# FPGA1.net
KiCad netlist of a schematic drawn in Altium Designer
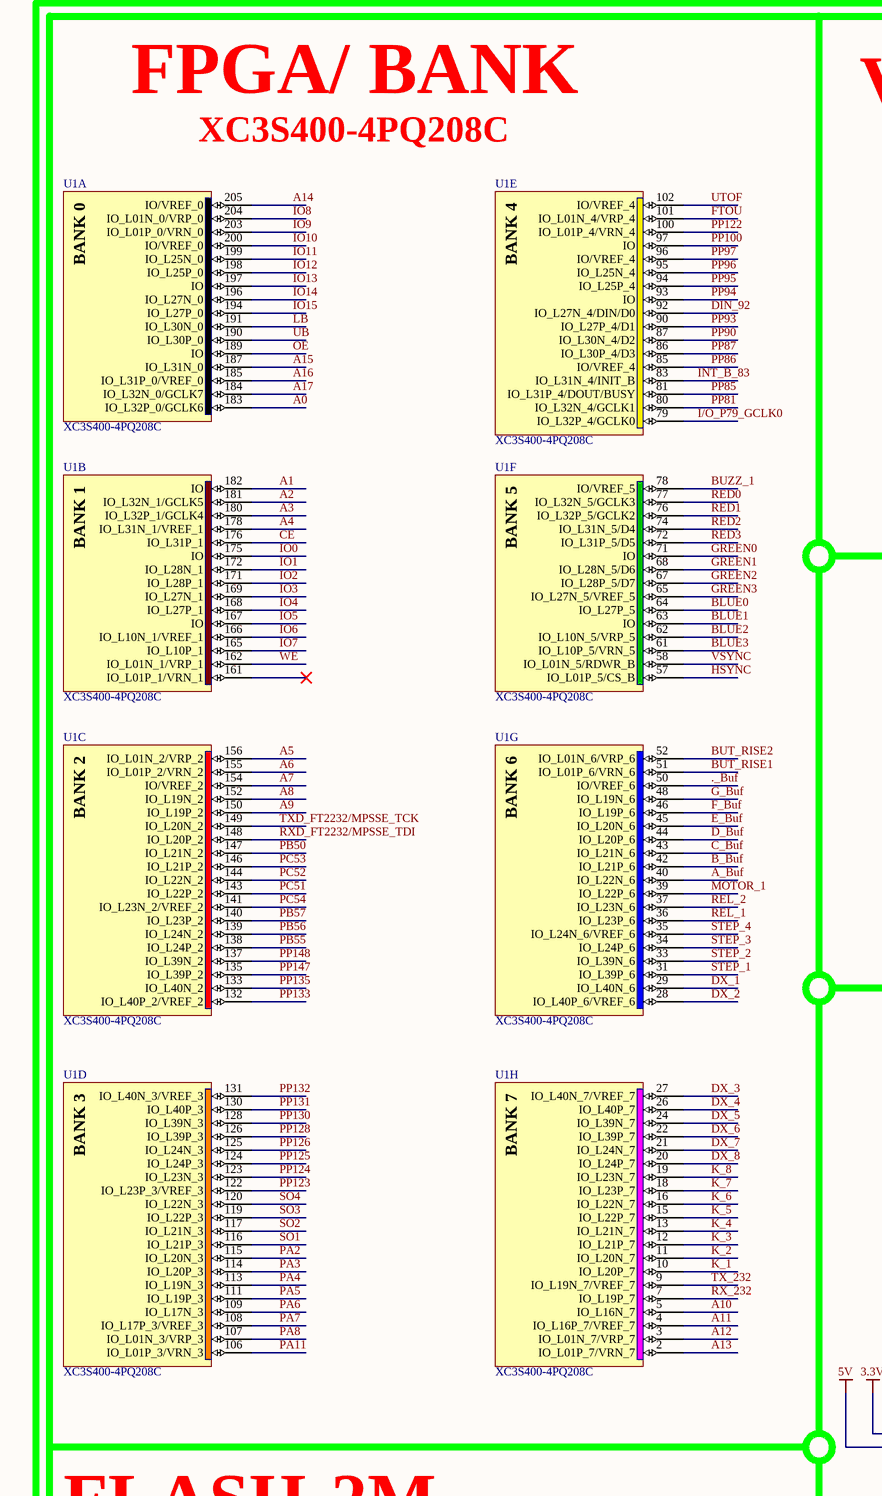
[diagram p0: FPGA1.SchDoc, top left]
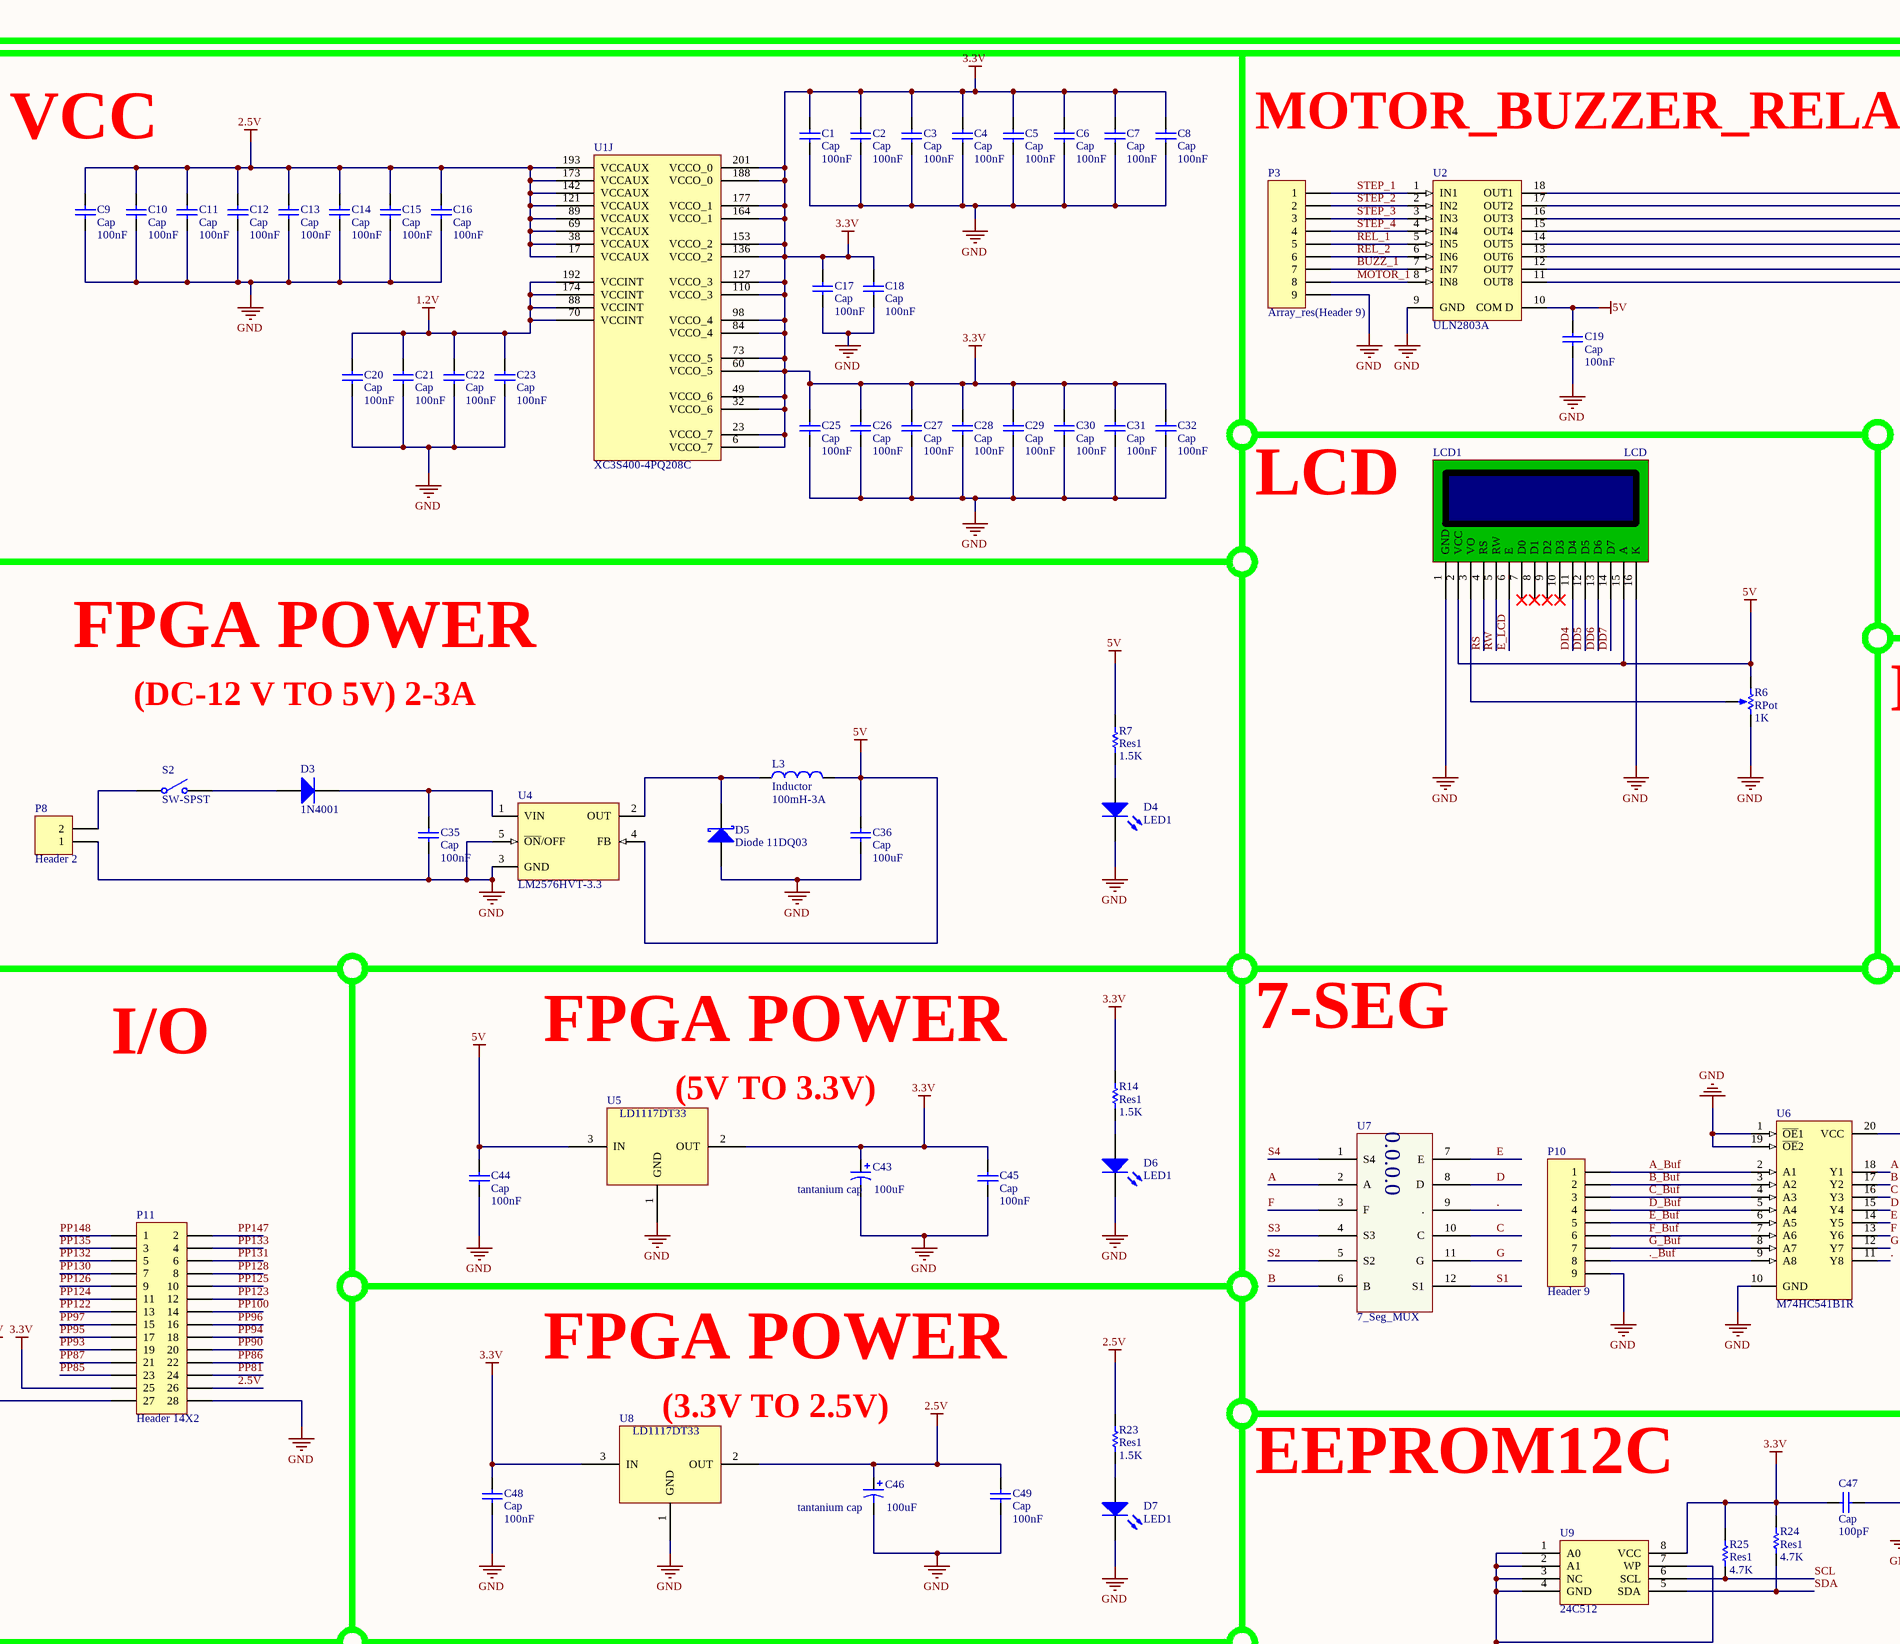
[diagram p1: FPGA1.SchDoc, top middle]
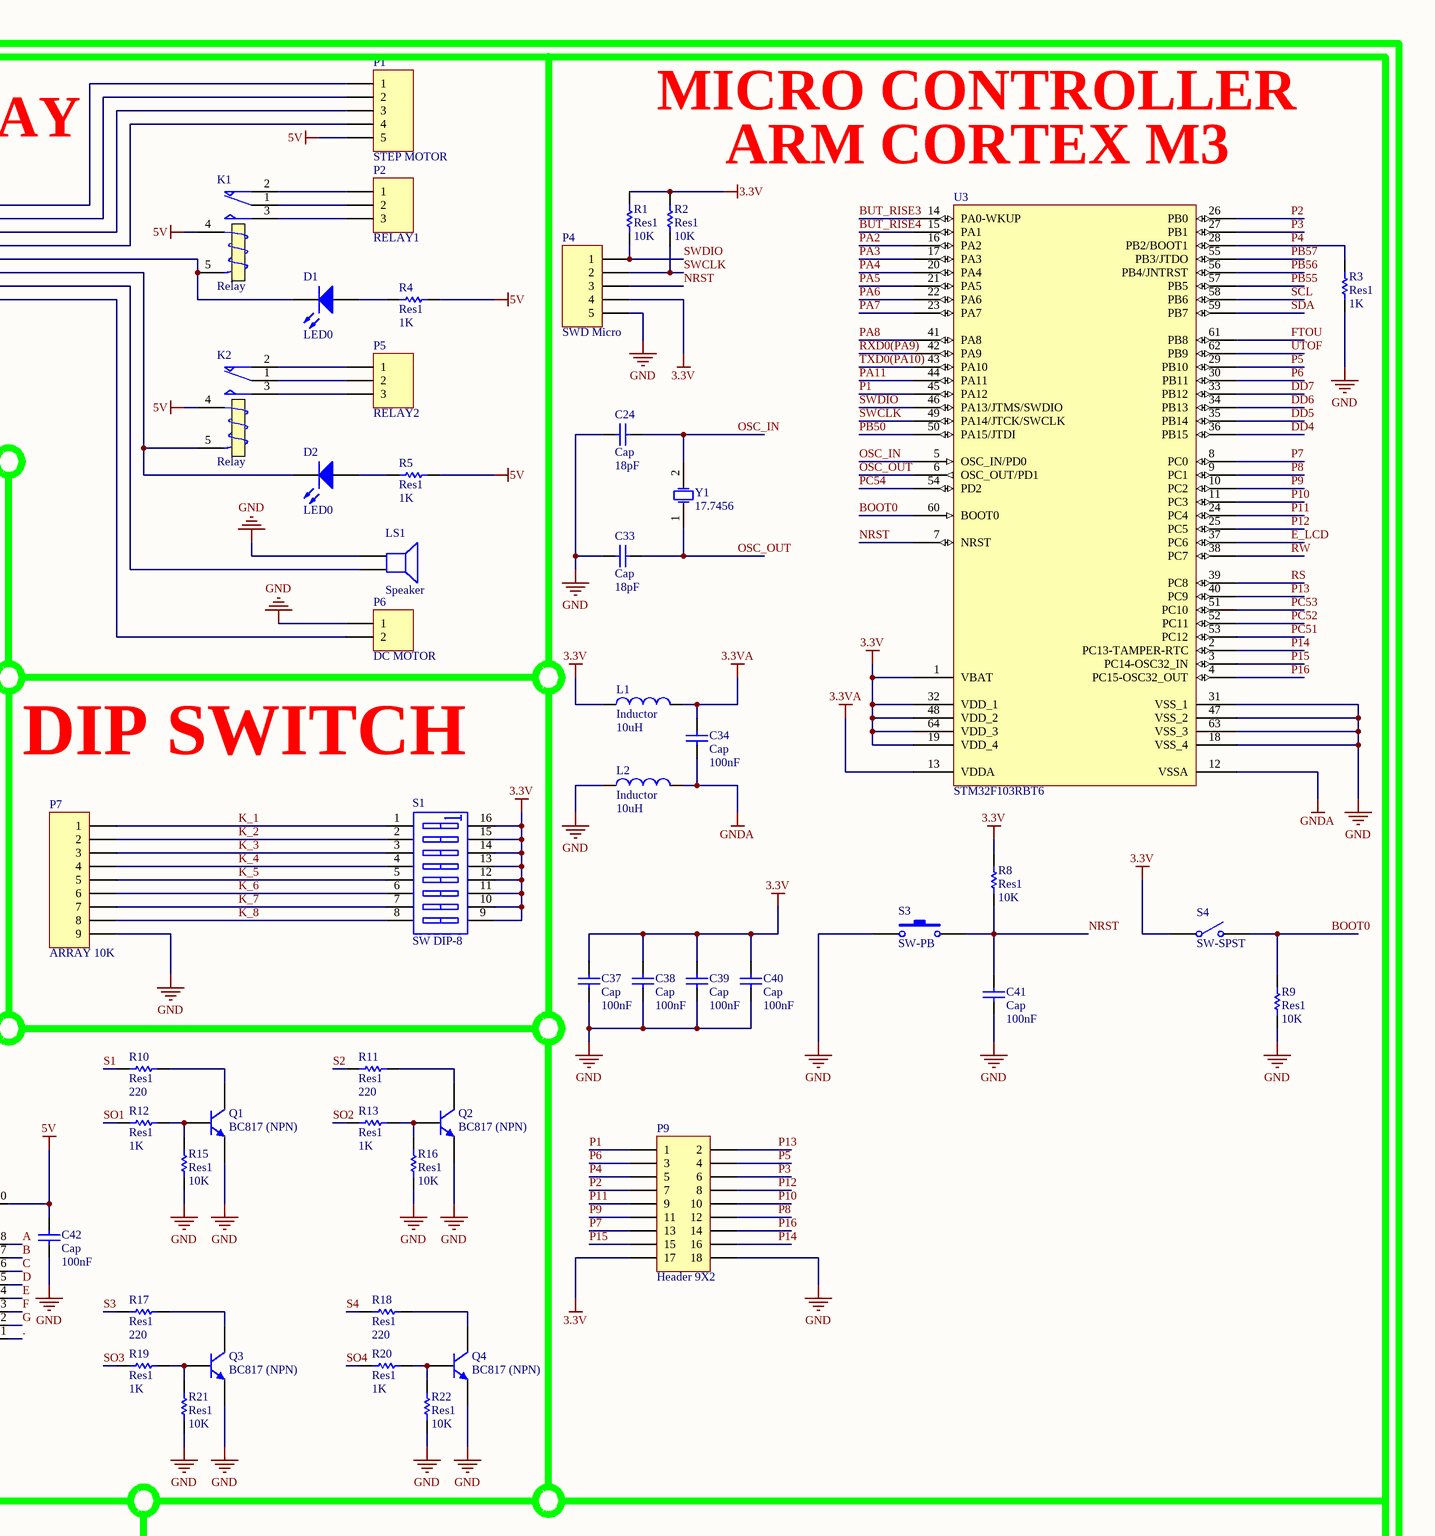
[diagram p2: FPGA1.SchDoc, top right]
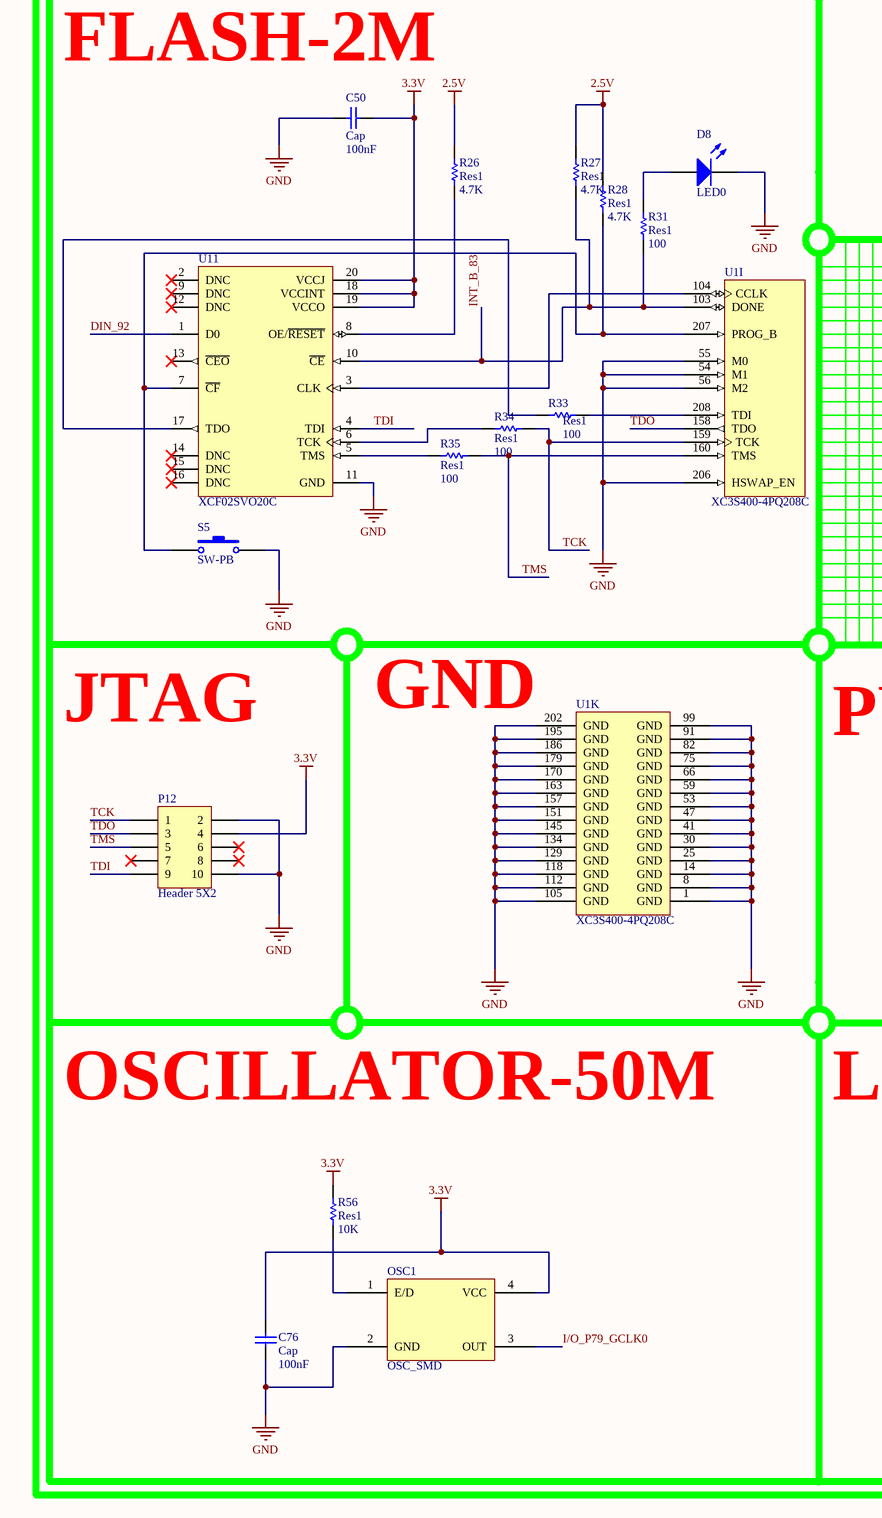
[diagram p3: FPGA1.SchDoc, bottom left]
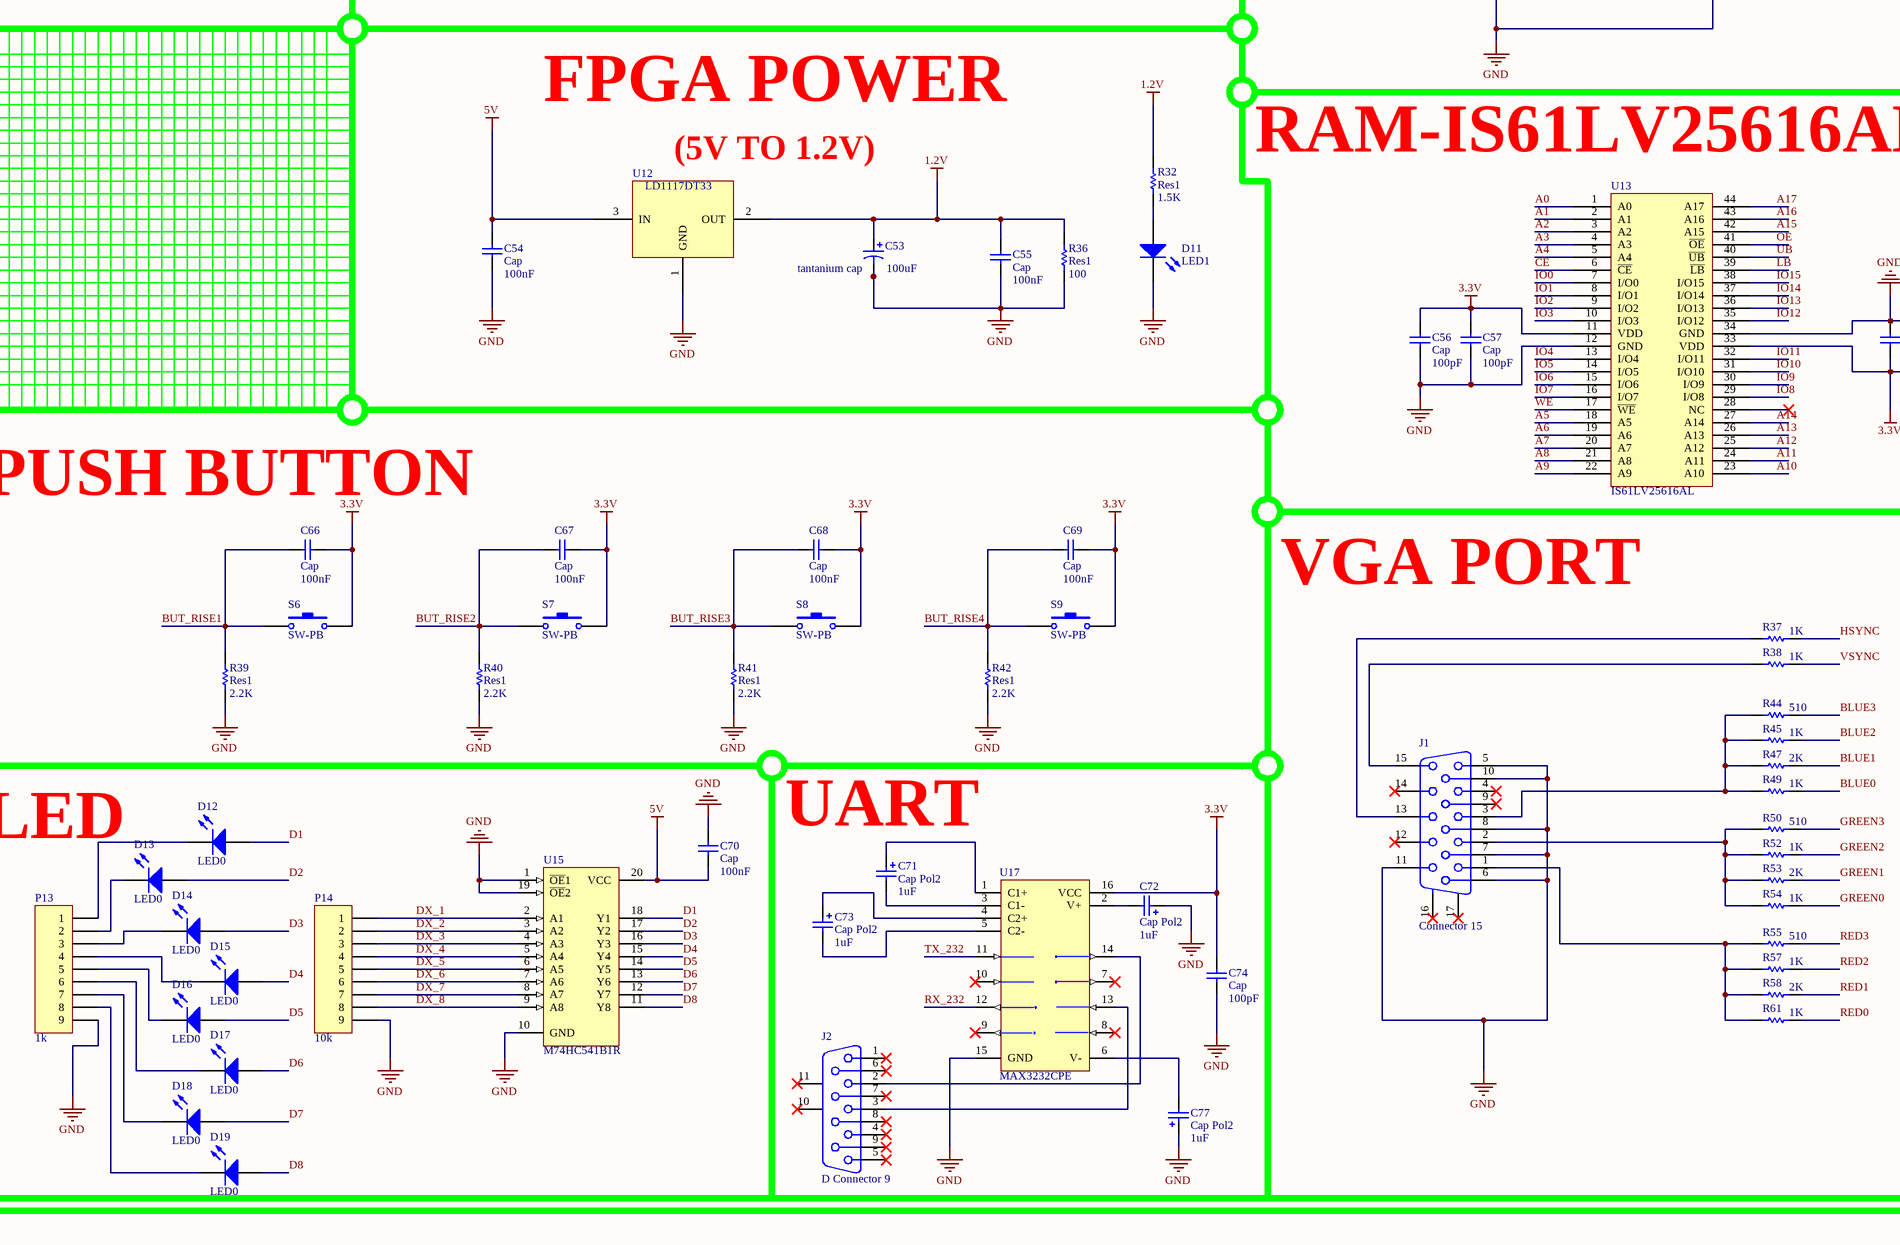
[diagram p4: FPGA1.SchDoc, bottom middle]
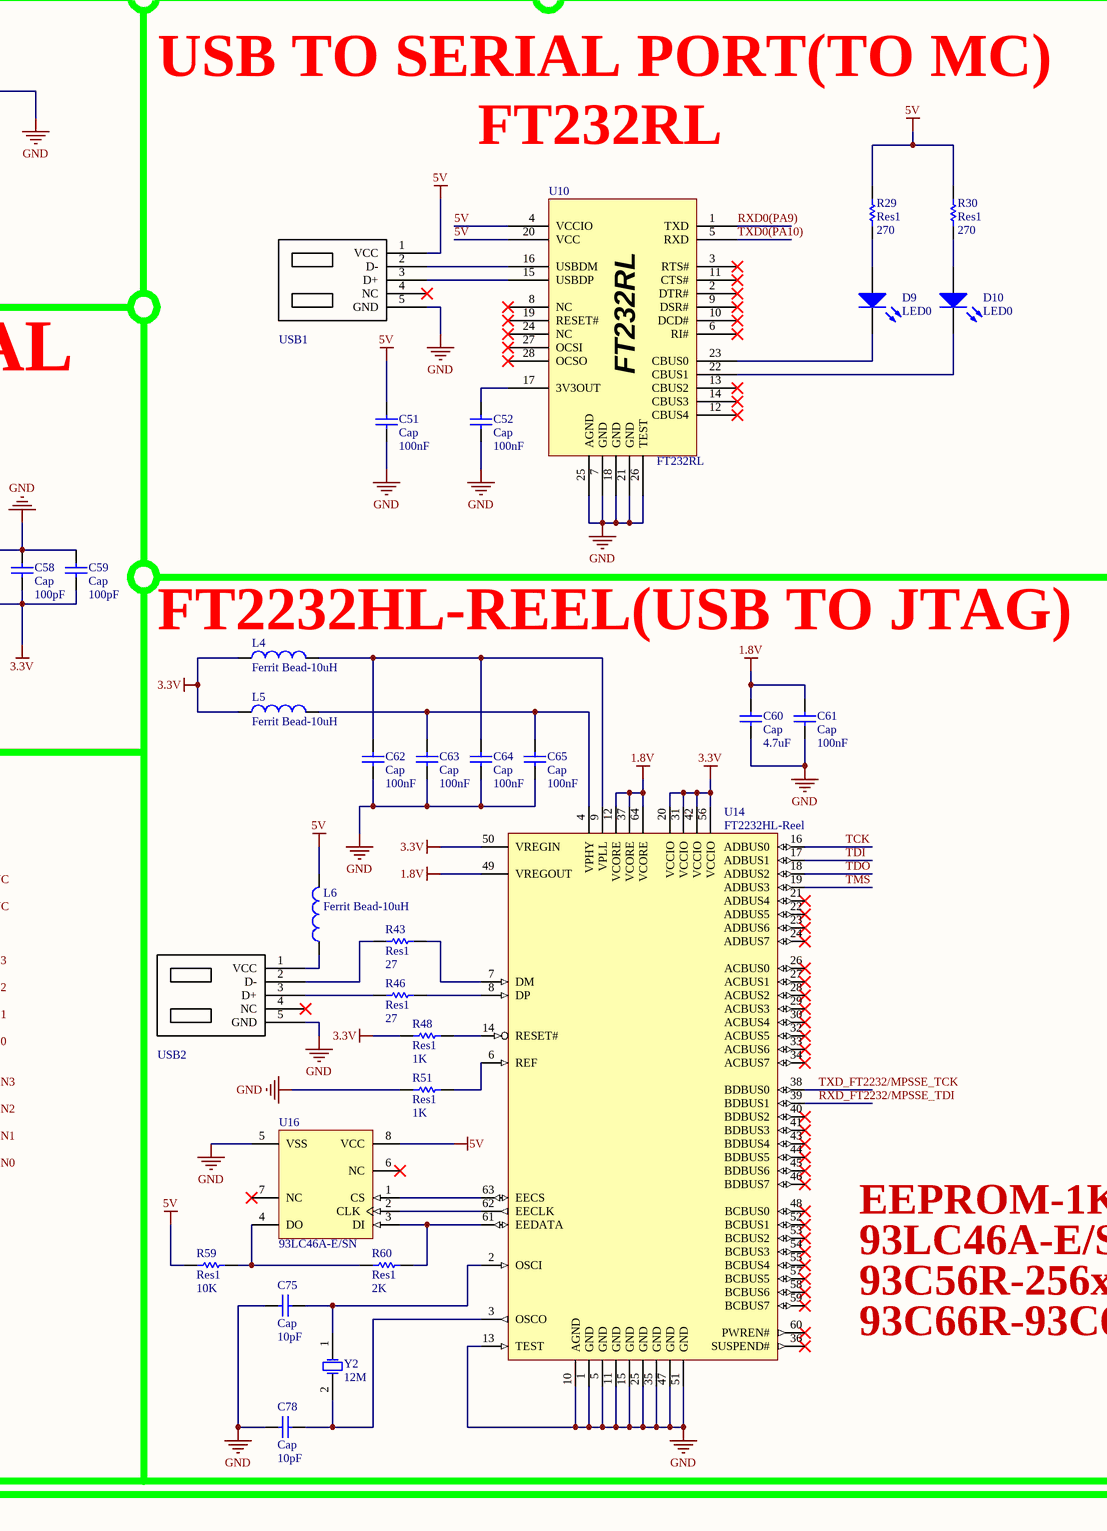
[diagram p5: FPGA1.SchDoc, bottom right]

(export (version "E")
  (design (tool "Eeschema 10.0.6"))
  (components
    (comp (ref "C1")
      (value "Cap")
      (footprint "SMD_805")
      (description "Capacitor")
      (fields (field (name "ALTIUM_VALUE") "100nF") (field (name "PUBLISHER") "Altium Limited"))
      (libsource (lib "Miscellaneous Devices") (part "Cap"))
    )
    (comp (ref "C2")
      (value "Cap")
      (footprint "SMD_805")
      (description "Capacitor")
      (fields (field (name "ALTIUM_VALUE") "100nF") (field (name "PUBLISHER") "Altium Limited"))
      (libsource (lib "Miscellaneous Devices") (part "Cap"))
    )
    (comp (ref "C3")
      (value "Cap")
      (footprint "SMD_805")
      (description "Capacitor")
      (fields (field (name "ALTIUM_VALUE") "100nF") (field (name "PUBLISHER") "Altium Limited"))
      (libsource (lib "Miscellaneous Devices") (part "Cap"))
    )
    (comp (ref "C4")
      (value "Cap")
      (footprint "SMD_805")
      (description "Capacitor")
      (fields (field (name "ALTIUM_VALUE") "100nF") (field (name "PUBLISHER") "Altium Limited"))
      (libsource (lib "Miscellaneous Devices") (part "Cap"))
    )
    (comp (ref "C5")
      (value "Cap")
      (footprint "SMD_805")
      (description "Capacitor")
      (fields (field (name "ALTIUM_VALUE") "100nF") (field (name "PUBLISHER") "Altium Limited"))
      (libsource (lib "Miscellaneous Devices") (part "Cap"))
    )
    (comp (ref "C6")
      (value "Cap")
      (footprint "SMD_805")
      (description "Capacitor")
      (fields (field (name "ALTIUM_VALUE") "100nF") (field (name "PUBLISHER") "Altium Limited"))
      (libsource (lib "Miscellaneous Devices") (part "Cap"))
    )
    (comp (ref "C7")
      (value "Cap")
      (footprint "SMD_805")
      (description "Capacitor")
      (fields (field (name "ALTIUM_VALUE") "100nF") (field (name "PUBLISHER") "Altium Limited"))
      (libsource (lib "Miscellaneous Devices") (part "Cap"))
    )
    (comp (ref "C8")
      (value "Cap")
      (footprint "SMD_805")
      (description "Capacitor")
      (fields (field (name "ALTIUM_VALUE") "100nF") (field (name "PUBLISHER") "Altium Limited"))
      (libsource (lib "Miscellaneous Devices") (part "Cap"))
    )
    (comp (ref "C9")
      (value "Cap")
      (footprint "SMD_805")
      (description "Capacitor")
      (fields (field (name "ALTIUM_VALUE") "100nF") (field (name "PUBLISHER") "Altium Limited"))
      (libsource (lib "Miscellaneous Devices") (part "Cap"))
    )
    (comp (ref "C10")
      (value "Cap")
      (footprint "SMD_805")
      (description "Capacitor")
      (fields (field (name "ALTIUM_VALUE") "100nF") (field (name "PUBLISHER") "Altium Limited"))
      (libsource (lib "Miscellaneous Devices") (part "Cap"))
    )
    (comp (ref "C11")
      (value "Cap")
      (footprint "SMD_805")
      (description "Capacitor")
      (fields (field (name "ALTIUM_VALUE") "100nF") (field (name "PUBLISHER") "Altium Limited"))
      (libsource (lib "Miscellaneous Devices") (part "Cap"))
    )
    (comp (ref "C12")
      (value "Cap")
      (footprint "SMD_805")
      (description "Capacitor")
      (fields (field (name "ALTIUM_VALUE") "100nF") (field (name "PUBLISHER") "Altium Limited"))
      (libsource (lib "Miscellaneous Devices") (part "Cap"))
    )
    (comp (ref "C13")
      (value "Cap")
      (footprint "SMD_805")
      (description "Capacitor")
      (fields (field (name "ALTIUM_VALUE") "100nF") (field (name "PUBLISHER") "Altium Limited"))
      (libsource (lib "Miscellaneous Devices") (part "Cap"))
    )
    (comp (ref "C14")
      (value "Cap")
      (footprint "SMD_805")
      (description "Capacitor")
      (fields (field (name "ALTIUM_VALUE") "100nF") (field (name "PUBLISHER") "Altium Limited"))
      (libsource (lib "Miscellaneous Devices") (part "Cap"))
    )
    (comp (ref "C15")
      (value "Cap")
      (footprint "SMD_805")
      (description "Capacitor")
      (fields (field (name "ALTIUM_VALUE") "100nF") (field (name "PUBLISHER") "Altium Limited"))
      (libsource (lib "Miscellaneous Devices") (part "Cap"))
    )
    (comp (ref "C16")
      (value "Cap")
      (footprint "SMD_805")
      (description "Capacitor")
      (fields (field (name "ALTIUM_VALUE") "100nF") (field (name "PUBLISHER") "Altium Limited"))
      (libsource (lib "Miscellaneous Devices") (part "Cap"))
    )
    (comp (ref "C17")
      (value "Cap")
      (footprint "SMD_805")
      (description "Capacitor")
      (fields (field (name "ALTIUM_VALUE") "100nF") (field (name "PUBLISHER") "Altium Limited"))
      (libsource (lib "Miscellaneous Devices") (part "Cap"))
    )
    (comp (ref "C18")
      (value "Cap")
      (footprint "SMD_805")
      (description "Capacitor")
      (fields (field (name "ALTIUM_VALUE") "100nF") (field (name "PUBLISHER") "Altium Limited"))
      (libsource (lib "Miscellaneous Devices") (part "Cap"))
    )
    (comp (ref "C19")
      (value "Cap")
      (footprint "SMD_805")
      (description "Capacitor")
      (fields (field (name "ALTIUM_VALUE") "100nF") (field (name "PUBLISHER") "Altium Limited"))
      (libsource (lib "Miscellaneous Devices") (part "Cap"))
    )
    (comp (ref "C20")
      (value "Cap")
      (footprint "SMD_805")
      (description "Capacitor")
      (fields (field (name "ALTIUM_VALUE") "100nF") (field (name "PUBLISHER") "Altium Limited"))
      (libsource (lib "Miscellaneous Devices") (part "Cap"))
    )
    (comp (ref "C21")
      (value "Cap")
      (footprint "SMD_805")
      (description "Capacitor")
      (fields (field (name "ALTIUM_VALUE") "100nF") (field (name "PUBLISHER") "Altium Limited"))
      (libsource (lib "Miscellaneous Devices") (part "Cap"))
    )
    (comp (ref "C22")
      (value "Cap")
      (footprint "SMD_805")
      (description "Capacitor")
      (fields (field (name "ALTIUM_VALUE") "100nF") (field (name "PUBLISHER") "Altium Limited"))
      (libsource (lib "Miscellaneous Devices") (part "Cap"))
    )
    (comp (ref "C23")
      (value "Cap")
      (footprint "SMD_805")
      (description "Capacitor")
      (fields (field (name "ALTIUM_VALUE") "100nF") (field (name "PUBLISHER") "Altium Limited"))
      (libsource (lib "Miscellaneous Devices") (part "Cap"))
    )
    (comp (ref "C24")
      (value "Cap")
      (footprint "SMD_805")
      (description "Capacitor")
      (fields (field (name "ALTIUM_VALUE") "18pF") (field (name "PUBLISHER") "Altium Limited"))
      (libsource (lib "Miscellaneous Devices") (part "Cap"))
    )
    (comp (ref "C25")
      (value "Cap")
      (footprint "SMD_805")
      (description "Capacitor")
      (fields (field (name "ALTIUM_VALUE") "100nF") (field (name "PUBLISHER") "Altium Limited"))
      (libsource (lib "Miscellaneous Devices") (part "Cap"))
    )
    (comp (ref "C26")
      (value "Cap")
      (footprint "SMD_805")
      (description "Capacitor")
      (fields (field (name "ALTIUM_VALUE") "100nF") (field (name "PUBLISHER") "Altium Limited"))
      (libsource (lib "Miscellaneous Devices") (part "Cap"))
    )
    (comp (ref "C27")
      (value "Cap")
      (footprint "SMD_805")
      (description "Capacitor")
      (fields (field (name "ALTIUM_VALUE") "100nF") (field (name "PUBLISHER") "Altium Limited"))
      (libsource (lib "Miscellaneous Devices") (part "Cap"))
    )
    (comp (ref "C28")
      (value "Cap")
      (footprint "SMD_805")
      (description "Capacitor")
      (fields (field (name "ALTIUM_VALUE") "100nF") (field (name "PUBLISHER") "Altium Limited"))
      (libsource (lib "Miscellaneous Devices") (part "Cap"))
    )
    (comp (ref "C29")
      (value "Cap")
      (footprint "SMD_805")
      (description "Capacitor")
      (fields (field (name "ALTIUM_VALUE") "100nF") (field (name "PUBLISHER") "Altium Limited"))
      (libsource (lib "Miscellaneous Devices") (part "Cap"))
    )
    (comp (ref "C30")
      (value "Cap")
      (footprint "SMD_805")
      (description "Capacitor")
      (fields (field (name "ALTIUM_VALUE") "100nF") (field (name "PUBLISHER") "Altium Limited"))
      (libsource (lib "Miscellaneous Devices") (part "Cap"))
    )
    (comp (ref "C31")
      (value "Cap")
      (footprint "SMD_805")
      (description "Capacitor")
      (fields (field (name "ALTIUM_VALUE") "100nF") (field (name "PUBLISHER") "Altium Limited"))
      (libsource (lib "Miscellaneous Devices") (part "Cap"))
    )
    (comp (ref "C32")
      (value "Cap")
      (footprint "SMD_805")
      (description "Capacitor")
      (fields (field (name "ALTIUM_VALUE") "100nF") (field (name "PUBLISHER") "Altium Limited"))
      (libsource (lib "Miscellaneous Devices") (part "Cap"))
    )
    (comp (ref "C33")
      (value "Cap")
      (footprint "SMD_805")
      (description "Capacitor")
      (fields (field (name "ALTIUM_VALUE") "18pF") (field (name "PUBLISHER") "Altium Limited"))
      (libsource (lib "Miscellaneous Devices") (part "Cap"))
    )
    (comp (ref "C34")
      (value "Cap")
      (footprint "SMD_805")
      (description "Capacitor")
      (fields (field (name "ALTIUM_VALUE") "100nF") (field (name "PUBLISHER") "Altium Limited"))
      (libsource (lib "Miscellaneous Devices") (part "Cap"))
    )
    (comp (ref "C35")
      (value "Cap")
      (footprint "C_CYL_SMD2")
      (description "Capacitor")
      (fields (field (name "ALTIUM_VALUE") "100nF") (field (name "PUBLISHER") "Altium Limited"))
      (libsource (lib "Miscellaneous Devices") (part "Cap"))
    )
    (comp (ref "C36")
      (value "Cap")
      (footprint "C_CYL_SMD")
      (description "Capacitor")
      (fields (field (name "ALTIUM_VALUE") "100uF") (field (name "PUBLISHER") "Altium Limited"))
      (libsource (lib "Miscellaneous Devices") (part "Cap"))
    )
    (comp (ref "C37")
      (value "Cap")
      (footprint "SMD_805")
      (description "Capacitor")
      (fields (field (name "ALTIUM_VALUE") "100nF") (field (name "PUBLISHER") "Altium Limited"))
      (libsource (lib "Miscellaneous Devices") (part "Cap"))
    )
    (comp (ref "C38")
      (value "Cap")
      (footprint "SMD_805")
      (description "Capacitor")
      (fields (field (name "ALTIUM_VALUE") "100nF") (field (name "PUBLISHER") "Altium Limited"))
      (libsource (lib "Miscellaneous Devices") (part "Cap"))
    )
    (comp (ref "C39")
      (value "Cap")
      (footprint "SMD_805")
      (description "Capacitor")
      (fields (field (name "ALTIUM_VALUE") "100nF") (field (name "PUBLISHER") "Altium Limited"))
      (libsource (lib "Miscellaneous Devices") (part "Cap"))
    )
    (comp (ref "C40")
      (value "Cap")
      (footprint "SMD_805")
      (description "Capacitor")
      (fields (field (name "ALTIUM_VALUE") "100nF") (field (name "PUBLISHER") "Altium Limited"))
      (libsource (lib "Miscellaneous Devices") (part "Cap"))
    )
    (comp (ref "C41")
      (value "Cap")
      (footprint "SMD_805")
      (description "Capacitor")
      (fields (field (name "ALTIUM_VALUE") "100nF") (field (name "PUBLISHER") "Altium Limited"))
      (libsource (lib "Miscellaneous Devices") (part "Cap"))
    )
    (comp (ref "C42")
      (value "Cap")
      (footprint "SMD_805")
      (description "Capacitor")
      (fields (field (name "ALTIUM_VALUE") "100nF") (field (name "PUBLISHER") "Altium Limited"))
      (libsource (lib "Miscellaneous Devices") (part "Cap"))
    )
    (comp (ref "C43")
      (value "tantanium cap")
      (footprint "C_B")
      (description "Polarized Capacitor (Surface Mount)")
      (fields (field (name "ALTIUM_VALUE") "100uF") (field (name "PUBLISHER") "Altium Limited"))
      (libsource (lib "Miscellaneous Devices") (part "Cap Pol3"))
    )
    (comp (ref "C44")
      (value "Cap")
      (footprint "SMD_805")
      (description "Capacitor")
      (fields (field (name "ALTIUM_VALUE") "100nF") (field (name "PUBLISHER") "Altium Limited"))
      (libsource (lib "Miscellaneous Devices") (part "Cap"))
    )
    (comp (ref "C45")
      (value "Cap")
      (footprint "SMD_805")
      (description "Capacitor")
      (fields (field (name "ALTIUM_VALUE") "100nF") (field (name "PUBLISHER") "Altium Limited"))
      (libsource (lib "Miscellaneous Devices") (part "Cap"))
    )
    (comp (ref "C46")
      (value "tantanium cap")
      (footprint "C_B")
      (description "Polarized Capacitor (Surface Mount)")
      (fields (field (name "ALTIUM_VALUE") "100uF") (field (name "PUBLISHER") "Altium Limited"))
      (libsource (lib "Miscellaneous Devices") (part "Cap Pol3"))
    )
    (comp (ref "C47")
      (value "Cap")
      (footprint "SMD_805")
      (description "Capacitor")
      (fields (field (name "ALTIUM_VALUE") "100pF") (field (name "PUBLISHER") "Altium Limited"))
      (libsource (lib "Miscellaneous Devices") (part "Cap"))
    )
    (comp (ref "C48")
      (value "Cap")
      (footprint "SMD_805")
      (description "Capacitor")
      (fields (field (name "ALTIUM_VALUE") "100nF") (field (name "PUBLISHER") "Altium Limited"))
      (libsource (lib "Miscellaneous Devices") (part "Cap"))
    )
    (comp (ref "C49")
      (value "Cap")
      (footprint "SMD_805")
      (description "Capacitor")
      (fields (field (name "ALTIUM_VALUE") "100nF") (field (name "PUBLISHER") "Altium Limited"))
      (libsource (lib "Miscellaneous Devices") (part "Cap"))
    )
    (comp (ref "C50")
      (value "Cap")
      (footprint "SMD_805")
      (description "Capacitor")
      (fields (field (name "ALTIUM_VALUE") "100nF") (field (name "PUBLISHER") "Altium Limited"))
      (libsource (lib "Miscellaneous Devices") (part "Cap"))
    )
    (comp (ref "C51")
      (value "Cap")
      (footprint "SMD_805")
      (description "Capacitor")
      (fields (field (name "ALTIUM_VALUE") "100nF") (field (name "PUBLISHER") "Altium Limited"))
      (libsource (lib "Miscellaneous Devices") (part "Cap"))
    )
    (comp (ref "C52")
      (value "Cap")
      (footprint "SMD_805")
      (description "Capacitor")
      (fields (field (name "ALTIUM_VALUE") "100nF") (field (name "PUBLISHER") "Altium Limited"))
      (libsource (lib "Miscellaneous Devices") (part "Cap"))
    )
    (comp (ref "C53")
      (value "tantanium cap")
      (footprint "C_B")
      (description "Polarized Capacitor (Surface Mount)")
      (fields (field (name "ALTIUM_VALUE") "100uF") (field (name "PUBLISHER") "Altium Limited"))
      (libsource (lib "Miscellaneous Devices") (part "Cap Pol3"))
    )
    (comp (ref "C54")
      (value "Cap")
      (footprint "SMD_805")
      (description "Capacitor")
      (fields (field (name "ALTIUM_VALUE") "100nF") (field (name "PUBLISHER") "Altium Limited"))
      (libsource (lib "Miscellaneous Devices") (part "Cap"))
    )
    (comp (ref "C55")
      (value "Cap")
      (footprint "SMD_805")
      (description "Capacitor")
      (fields (field (name "ALTIUM_VALUE") "100nF") (field (name "PUBLISHER") "Altium Limited"))
      (libsource (lib "Miscellaneous Devices") (part "Cap"))
    )
    (comp (ref "C56")
      (value "Cap")
      (footprint "SMD_805")
      (description "Capacitor")
      (fields (field (name "ALTIUM_VALUE") "100pF") (field (name "PUBLISHER") "Altium Limited"))
      (libsource (lib "Miscellaneous Devices") (part "Cap"))
    )
    (comp (ref "C57")
      (value "Cap")
      (footprint "SMD_805")
      (description "Capacitor")
      (fields (field (name "ALTIUM_VALUE") "100pF") (field (name "PUBLISHER") "Altium Limited"))
      (libsource (lib "Miscellaneous Devices") (part "Cap"))
    )
    (comp (ref "C58")
      (value "Cap")
      (footprint "SMD_805")
      (description "Capacitor")
      (fields (field (name "ALTIUM_VALUE") "100pF") (field (name "PUBLISHER") "Altium Limited"))
      (libsource (lib "Miscellaneous Devices") (part "Cap"))
    )
    (comp (ref "C59")
      (value "Cap")
      (footprint "SMD_805")
      (description "Capacitor")
      (fields (field (name "ALTIUM_VALUE") "100pF") (field (name "PUBLISHER") "Altium Limited"))
      (libsource (lib "Miscellaneous Devices") (part "Cap"))
    )
    (comp (ref "C60")
      (value "Cap")
      (footprint "SMD_805")
      (description "Capacitor")
      (fields (field (name "ALTIUM_VALUE") "4.7uF") (field (name "PUBLISHER") "Altium Limited"))
      (libsource (lib "Miscellaneous Devices") (part "Cap"))
    )
    (comp (ref "C61")
      (value "Cap")
      (footprint "SMD_805")
      (description "Capacitor")
      (fields (field (name "ALTIUM_VALUE") "100nF") (field (name "PUBLISHER") "Altium Limited"))
      (libsource (lib "Miscellaneous Devices") (part "Cap"))
    )
    (comp (ref "C62")
      (value "Cap")
      (footprint "SMD_805")
      (description "Capacitor")
      (fields (field (name "ALTIUM_VALUE") "100nF") (field (name "PUBLISHER") "Altium Limited"))
      (libsource (lib "Miscellaneous Devices") (part "Cap"))
    )
    (comp (ref "C63")
      (value "Cap")
      (footprint "SMD_805")
      (description "Capacitor")
      (fields (field (name "ALTIUM_VALUE") "100nF") (field (name "PUBLISHER") "Altium Limited"))
      (libsource (lib "Miscellaneous Devices") (part "Cap"))
    )
    (comp (ref "C64")
      (value "Cap")
      (footprint "SMD_805")
      (description "Capacitor")
      (fields (field (name "ALTIUM_VALUE") "100nF") (field (name "PUBLISHER") "Altium Limited"))
      (libsource (lib "Miscellaneous Devices") (part "Cap"))
    )
    (comp (ref "C65")
      (value "Cap")
      (footprint "SMD_805")
      (description "Capacitor")
      (fields (field (name "ALTIUM_VALUE") "100nF") (field (name "PUBLISHER") "Altium Limited"))
      (libsource (lib "Miscellaneous Devices") (part "Cap"))
    )
    (comp (ref "C66")
      (value "Cap")
      (footprint "SMD_805")
      (description "Capacitor")
      (fields (field (name "ALTIUM_VALUE") "100nF") (field (name "PUBLISHER") "Altium Limited"))
      (libsource (lib "Miscellaneous Devices") (part "Cap"))
    )
    (comp (ref "C67")
      (value "Cap")
      (footprint "SMD_805")
      (description "Capacitor")
      (fields (field (name "ALTIUM_VALUE") "100nF") (field (name "PUBLISHER") "Altium Limited"))
      (libsource (lib "Miscellaneous Devices") (part "Cap"))
    )
    (comp (ref "C68")
      (value "Cap")
      (footprint "SMD_805")
      (description "Capacitor")
      (fields (field (name "ALTIUM_VALUE") "100nF") (field (name "PUBLISHER") "Altium Limited"))
      (libsource (lib "Miscellaneous Devices") (part "Cap"))
    )
    (comp (ref "C69")
      (value "Cap")
      (footprint "SMD_805")
      (description "Capacitor")
      (fields (field (name "ALTIUM_VALUE") "100nF") (field (name "PUBLISHER") "Altium Limited"))
      (libsource (lib "Miscellaneous Devices") (part "Cap"))
    )
    (comp (ref "C70")
      (value "Cap")
      (footprint "SMD_805")
      (description "Capacitor")
      (fields (field (name "ALTIUM_VALUE") "100nF") (field (name "PUBLISHER") "Altium Limited"))
      (libsource (lib "Miscellaneous Devices") (part "Cap"))
    )
    (comp (ref "C71")
      (value "Cap Pol2")
      (footprint "C_B")
      (description "Polarized Capacitor (Axial)")
      (fields (field (name "ALTIUM_VALUE") "1uF") (field (name "PUBLISHER") "Altium Limited"))
      (libsource (lib "Miscellaneous Devices") (part "Cap Pol2"))
    )
    (comp (ref "C72")
      (value "Cap Pol2")
      (footprint "C_B")
      (description "Polarized Capacitor (Axial)")
      (fields (field (name "ALTIUM_VALUE") "1uF") (field (name "PUBLISHER") "Altium Limited"))
      (libsource (lib "Miscellaneous Devices") (part "Cap Pol2"))
    )
    (comp (ref "C73")
      (value "Cap Pol2")
      (footprint "C_B")
      (description "Polarized Capacitor (Axial)")
      (fields (field (name "ALTIUM_VALUE") "1uF") (field (name "PUBLISHER") "Altium Limited"))
      (libsource (lib "Miscellaneous Devices") (part "Cap Pol2"))
    )
    (comp (ref "C74")
      (value "Cap")
      (footprint "SMD_805")
      (description "Capacitor")
      (fields (field (name "ALTIUM_VALUE") "100pF") (field (name "PUBLISHER") "Altium Limited"))
      (libsource (lib "Miscellaneous Devices") (part "Cap"))
    )
    (comp (ref "C75")
      (value "Cap")
      (footprint "SMD_805")
      (description "Capacitor")
      (fields (field (name "ALTIUM_VALUE") "10pF") (field (name "PUBLISHER") "Altium Limited"))
      (libsource (lib "Miscellaneous Devices") (part "Cap"))
    )
    (comp (ref "C76")
      (value "Cap")
      (footprint "SMD_805")
      (description "Capacitor")
      (fields (field (name "ALTIUM_VALUE") "100nF") (field (name "PUBLISHER") "Altium Limited"))
      (libsource (lib "Miscellaneous Devices") (part "Cap"))
    )
    (comp (ref "C77")
      (value "Cap Pol2")
      (footprint "C_B")
      (description "Polarized Capacitor (Axial)")
      (fields (field (name "ALTIUM_VALUE") "1uF") (field (name "PUBLISHER") "Altium Limited"))
      (libsource (lib "Miscellaneous Devices") (part "Cap Pol2"))
    )
    (comp (ref "C78")
      (value "Cap")
      (footprint "SMD_805")
      (description "Capacitor")
      (fields (field (name "ALTIUM_VALUE") "10pF") (field (name "PUBLISHER") "Altium Limited"))
      (libsource (lib "Miscellaneous Devices") (part "Cap"))
    )
    (comp (ref "D1")
      (value "LED0")
      (footprint "LED1206GRN")
      (description "Typical INFRARED GaAs LED")
      (fields (field (name "PUBLISHER") "Altium Limited"))
      (libsource (lib "Miscellaneous Devices") (part "LED0"))
    )
    (comp (ref "D2")
      (value "LED0")
      (footprint "LED1206GRN")
      (description "Typical INFRARED GaAs LED")
      (fields (field (name "PUBLISHER") "Altium Limited"))
      (libsource (lib "Miscellaneous Devices") (part "LED0"))
    )
    (comp (ref "D3")
      (value "1N4001")
      (footprint "TVS")
      (description "1 Amp General Purpose Rectifier")
      (fields (field (name "PUBLISHER") "Altium Limited"))
      (libsource (lib "Miscellaneous Devices") (part "Diode 1N4001"))
    )
    (comp (ref "D4")
      (value "LED1")
      (footprint "Led0805")
      (description "Typical INFRARED GaAs LED")
      (fields (field (name "PUBLISHER") "Altium Limited"))
      (libsource (lib "Miscellaneous Devices") (part "LED0"))
    )
    (comp (ref "D5")
      (value "Diode 11DQ03")
      (footprint "1N5822")
      (description "Schottky Rectifier")
      (fields (field (name "PUBLISHER") "Altium Limited"))
      (libsource (lib "Miscellaneous Devices") (part "Diode 11DQ03"))
    )
    (comp (ref "D6")
      (value "LED1")
      (footprint "Led0805")
      (description "Typical INFRARED GaAs LED")
      (fields (field (name "PUBLISHER") "Altium Limited"))
      (libsource (lib "Miscellaneous Devices") (part "LED0"))
    )
    (comp (ref "D7")
      (value "LED1")
      (footprint "Led0805")
      (description "Typical INFRARED GaAs LED")
      (fields (field (name "PUBLISHER") "Altium Limited"))
      (libsource (lib "Miscellaneous Devices") (part "LED0"))
    )
    (comp (ref "D8")
      (value "LED0")
      (footprint "LED0805GRN")
      (description "Typical INFRARED GaAs LED")
      (fields (field (name "PUBLISHER") "Altium Limited"))
      (libsource (lib "Miscellaneous Devices") (part "LED0"))
    )
    (comp (ref "D9")
      (value "LED0")
      (footprint "LED0805GRN")
      (description "Typical INFRARED GaAs LED")
      (fields (field (name "PUBLISHER") "Altium Limited"))
      (libsource (lib "Miscellaneous Devices") (part "LED0"))
    )
    (comp (ref "D10")
      (value "LED0")
      (footprint "LED0805GRN")
      (description "Typical INFRARED GaAs LED")
      (fields (field (name "PUBLISHER") "Altium Limited"))
      (libsource (lib "Miscellaneous Devices") (part "LED0"))
    )
    (comp (ref "D11")
      (value "LED1")
      (footprint "Led0805")
      (description "Typical INFRARED GaAs LED")
      (fields (field (name "PUBLISHER") "Altium Limited"))
      (libsource (lib "Miscellaneous Devices") (part "LED0"))
    )
    (comp (ref "D12")
      (value "LED0")
      (footprint "LED1206RED")
      (description "Typical INFRARED GaAs LED")
      (fields (field (name "PUBLISHER") "Altium Limited"))
      (libsource (lib "Miscellaneous Devices") (part "LED0"))
    )
    (comp (ref "D13")
      (value "LED0")
      (footprint "LED1206RED")
      (description "Typical INFRARED GaAs LED")
      (fields (field (name "PUBLISHER") "Altium Limited"))
      (libsource (lib "Miscellaneous Devices") (part "LED0"))
    )
    (comp (ref "D14")
      (value "LED0")
      (footprint "LED1206RED")
      (description "Typical INFRARED GaAs LED")
      (fields (field (name "PUBLISHER") "Altium Limited"))
      (libsource (lib "Miscellaneous Devices") (part "LED0"))
    )
    (comp (ref "D15")
      (value "LED0")
      (footprint "LED1206RED")
      (description "Typical INFRARED GaAs LED")
      (fields (field (name "PUBLISHER") "Altium Limited"))
      (libsource (lib "Miscellaneous Devices") (part "LED0"))
    )
    (comp (ref "D16")
      (value "LED0")
      (footprint "LED1206RED")
      (description "Typical INFRARED GaAs LED")
      (fields (field (name "PUBLISHER") "Altium Limited"))
      (libsource (lib "Miscellaneous Devices") (part "LED0"))
    )
    (comp (ref "D17")
      (value "LED0")
      (footprint "LED1206RED")
      (description "Typical INFRARED GaAs LED")
      (fields (field (name "PUBLISHER") "Altium Limited"))
      (libsource (lib "Miscellaneous Devices") (part "LED0"))
    )
    (comp (ref "D18")
      (value "LED0")
      (footprint "LED1206RED")
      (description "Typical INFRARED GaAs LED")
      (fields (field (name "PUBLISHER") "Altium Limited"))
      (libsource (lib "Miscellaneous Devices") (part "LED0"))
    )
    (comp (ref "D19")
      (value "LED0")
      (footprint "LED1206RED")
      (description "Typical INFRARED GaAs LED")
      (fields (field (name "PUBLISHER") "Altium Limited"))
      (libsource (lib "Miscellaneous Devices") (part "LED0"))
    )
    (comp (ref "J1")
      (value "Connector 15")
      (footprint "DSUB_15RF")
      (description "Receptacle Assembly, 15-Pin, Sim Line Connector")
      (fields (field (name "PUBLISHER") "Altium Limited"))
      (libsource (lib "Miscellaneous Connectors") (part "Connector 15"))
    )
    (comp (ref "J2")
      (value "D Connector 9")
      (footprint "COM_3d")
      (description "Receptacle Assembly, 9 Position, Right Angle")
      (fields (field (name "PUBLISHER") "Altium Limited"))
      (libsource (lib "Miscellaneous Connectors") (part "D Connector 9"))
    )
    (comp (ref "K1")
      (value "Relay")
      (footprint "REL_SPDT_5_1512")
      (description "SPDT Relay")
      (fields (field (name "PUBLISHER") "Altium Limited"))
      (libsource (lib "Miscellaneous Devices") (part "Relay"))
    )
    (comp (ref "K2")
      (value "Relay")
      (footprint "REL_SPDT_5_1512")
      (description "SPDT Relay")
      (fields (field (name "PUBLISHER") "Altium Limited"))
      (libsource (lib "Miscellaneous Devices") (part "Relay"))
    )
    (comp (ref "L1")
      (value "Inductor")
      (footprint "smd_805")
      (fields (field (name "ALTIUM_VALUE") "10uH") (field (name "PUBLISHER") "Altium Limited"))
      (libsource (lib "Miscellaneous Devices") (part "Inductor"))
    )
    (comp (ref "L2")
      (value "Inductor")
      (footprint "smd_805")
      (fields (field (name "ALTIUM_VALUE") "10uH") (field (name "PUBLISHER") "Altium Limited"))
      (libsource (lib "Miscellaneous Devices") (part "Inductor"))
    )
    (comp (ref "L3")
      (value "Inductor")
      (footprint "INDUC_SMD")
      (fields (field (name "ALTIUM_VALUE") "100mH-3A") (field (name "PUBLISHER") "Altium Limited"))
      (libsource (lib "Miscellaneous Devices") (part "Inductor"))
    )
    (comp (ref "L4")
      (value "Ferrit Bead-10uH")
      (footprint "smd_805")
      (description "Inductor")
      (fields (field (name "PUBLISHER") "Altium Limited"))
      (libsource (lib "Miscellaneous Devices") (part "Inductor"))
    )
    (comp (ref "L5")
      (value "Ferrit Bead-10uH")
      (footprint "smd_805")
      (description "Inductor")
      (fields (field (name "PUBLISHER") "Altium Limited"))
      (libsource (lib "Miscellaneous Devices") (part "Inductor"))
    )
    (comp (ref "L6")
      (value "Ferrit Bead-10uH")
      (footprint "smd_805")
      (description "Inductor")
      (fields (field (name "PUBLISHER") "Altium Limited"))
      (libsource (lib "Miscellaneous Devices") (part "Inductor"))
    )
    (comp (ref "LCD1") (value "LCD") (footprint "LCD2x16_3d") (libsource (lib "LCD") (part "LCD")))
    (comp (ref "LS1")
      (value "Speaker")
      (footprint "BZ_C9")
      (description "Loudspeaker")
      (fields (field (name "PUBLISHER") "Altium Limited"))
      (libsource (lib "Miscellaneous Devices") (part "Speaker"))
    )
    (comp (ref "OSC1")
      (value "OSC_SMD")
      (footprint "OSC_SMD")
      (fields (field (name "DESIGNER:") "Mohammad Ansari"))
      (libsource (lib "OSC_SMD") (part "Component_1"))
    )
    (comp (ref "P1")
      (value "STEP MOTOR")
      (footprint "HDR_M_1X5")
      (description "Header, 5-Pin")
      (fields (field (name "PUBLISHER") "Altium Limited"))
      (libsource (lib "") (part "Header 5_1"))
    )
    (comp (ref "P2")
      (value "RELAY1")
      (footprint "HDR_M_1X3")
      (description "Header, 3-Pin")
      (fields (field (name "PUBLISHER") "Altium Limited"))
      (libsource (lib "Miscellaneous Connectors") (part "Header 3"))
    )
    (comp (ref "P3")
      (value "Array_res(Header 9)")
      (footprint "Aray 9")
      (description "Header, 9-Pin")
      (fields (field (name "PUBLISHER") "Altium Limited"))
      (libsource (lib "Miscellaneous Connectors") (part "Header 9"))
    )
    (comp (ref "P4")
      (value "SWD Micro")
      (footprint "HDR_M_1X5")
      (description "Header, 5-Pin")
      (fields (field (name "PUBLISHER") "Altium Limited"))
      (libsource (lib "Miscellaneous Connectors") (part "Header 5"))
    )
    (comp (ref "P5")
      (value "RELAY2")
      (footprint "HDR_M_1X3")
      (description "Header, 3-Pin")
      (fields (field (name "PUBLISHER") "Altium Limited"))
      (libsource (lib "Miscellaneous Connectors") (part "Header 3"))
    )
    (comp (ref "P6")
      (value "DC MOTOR")
      (footprint "HDR_F_1X2")
      (description "Header, 2-Pin")
      (fields (field (name "PUBLISHER") "Altium Limited"))
      (libsource (lib "Miscellaneous Connectors") (part "Header 2"))
    )
    (comp (ref "P7")
      (value "ARRAY 10K")
      (footprint "Aray 9")
      (description "Header, 9-Pin")
      (fields (field (name "PUBLISHER") "Altium Limited"))
      (libsource (lib "Miscellaneous Connectors") (part "Header 9"))
    )
    (comp (ref "P8")
      (value "Header 2")
      (footprint "ADAP_JACK")
      (description "Header, 2-Pin")
      (fields (field (name "PUBLISHER") "Altium Limited"))
      (libsource (lib "") (part "Header 2_1"))
    )
    (comp (ref "P9")
      (value "Header 9X2")
      (footprint "HDR_M_2X9")
      (description "Header, 9-Pin, Dual row")
      (fields (field (name "PUBLISHER") "Altium Limited"))
      (libsource (lib "Miscellaneous Connectors") (part "Header 9X2"))
    )
    (comp (ref "P10")
      (value "Header 9")
      (footprint "Aray 9")
      (description "Header, 9-Pin")
      (fields (field (name "PUBLISHER") "Altium Limited"))
      (libsource (lib "Miscellaneous Connectors") (part "Header 9"))
    )
    (comp (ref "P11")
      (value "Header 14X2")
      (footprint "HDR_M_2X14")
      (description "Header, 14-Pin, Dual row")
      (fields (field (name "PUBLISHER") "Altium Limited"))
      (libsource (lib "Miscellaneous Connectors") (part "Header 14X2"))
    )
    (comp (ref "P12")
      (value "Header 5X2")
      (footprint "BOX2x5")
      (description "Header, 5-Pin, Dual row")
      (fields (field (name "PUBLISHER") "Altium Limited"))
      (libsource (lib "Miscellaneous Connectors") (part "Header 5X2"))
    )
    (comp (ref "P13")
      (value "1k")
      (footprint "Aray 9")
      (description "Header, 9-Pin")
      (fields (field (name "PUBLISHER") "Altium Limited"))
      (libsource (lib "Miscellaneous Connectors") (part "Header 9"))
    )
    (comp (ref "P14")
      (value "10k")
      (footprint "Aray 9")
      (description "Header, 9-Pin")
      (fields (field (name "PUBLISHER") "Altium Limited"))
      (libsource (lib "Miscellaneous Connectors") (part "Header 9"))
    )
    (comp (ref "Q1")
      (value "BC817 (NPN)")
      (footprint "SOT-23")
      (description "NPN General Purpose Amplifier")
      (fields (field (name "PUBLISHER") "Altium Limited"))
      (libsource (lib "Miscellaneous Devices") (part "2N3904"))
    )
    (comp (ref "Q2")
      (value "BC817 (NPN)")
      (footprint "SOT-23")
      (description "NPN General Purpose Amplifier")
      (fields (field (name "PUBLISHER") "Altium Limited"))
      (libsource (lib "Miscellaneous Devices") (part "2N3904"))
    )
    (comp (ref "Q3")
      (value "BC817 (NPN)")
      (footprint "SOT-23")
      (description "NPN General Purpose Amplifier")
      (fields (field (name "PUBLISHER") "Altium Limited"))
      (libsource (lib "Miscellaneous Devices") (part "2N3904"))
    )
    (comp (ref "Q4")
      (value "BC817 (NPN)")
      (footprint "SOT-23")
      (description "NPN General Purpose Amplifier")
      (fields (field (name "PUBLISHER") "Altium Limited"))
      (libsource (lib "Miscellaneous Devices") (part "2N3904"))
    )
    (comp (ref "R1")
      (value "Res1")
      (footprint "SMD_805")
      (description "Resistor")
      (fields (field (name "ALTIUM_VALUE") "10K") (field (name "PUBLISHER") "Altium Limited"))
      (libsource (lib "Miscellaneous Devices") (part "Res1"))
    )
    (comp (ref "R2")
      (value "Res1")
      (footprint "SMD_805")
      (description "Resistor")
      (fields (field (name "ALTIUM_VALUE") "10K") (field (name "PUBLISHER") "Altium Limited"))
      (libsource (lib "Miscellaneous Devices") (part "Res1"))
    )
    (comp (ref "R3")
      (value "Res1")
      (footprint "SMD_805")
      (description "Resistor")
      (fields (field (name "ALTIUM_VALUE") "1K") (field (name "PUBLISHER") "Altium Limited"))
      (libsource (lib "Miscellaneous Devices") (part "Res1"))
    )
    (comp (ref "R4")
      (value "Res1")
      (footprint "SMD_805")
      (description "Resistor")
      (fields (field (name "ALTIUM_VALUE") "1K") (field (name "PUBLISHER") "Altium Limited"))
      (libsource (lib "Miscellaneous Devices") (part "Res1"))
    )
    (comp (ref "R5")
      (value "Res1")
      (footprint "SMD_805")
      (description "Resistor")
      (fields (field (name "ALTIUM_VALUE") "1K") (field (name "PUBLISHER") "Altium Limited"))
      (libsource (lib "Miscellaneous Devices") (part "Res1"))
    )
    (comp (ref "R6")
      (value "RPot")
      (footprint "POT_3296Y")
      (description "Potentiometer")
      (fields (field (name "ALTIUM_VALUE") "1K") (field (name "PUBLISHER") "Altium Limited"))
      (libsource (lib "Miscellaneous Devices") (part "RPot"))
    )
    (comp (ref "R7")
      (value "Res1")
      (footprint "SMD_805")
      (description "Resistor")
      (fields (field (name "ALTIUM_VALUE") "1.5K") (field (name "PUBLISHER") "Altium Limited"))
      (libsource (lib "Miscellaneous Devices") (part "Res1"))
    )
    (comp (ref "R8")
      (value "Res1")
      (footprint "SMD_805")
      (description "Resistor")
      (fields (field (name "ALTIUM_VALUE") "10K") (field (name "PUBLISHER") "Altium Limited"))
      (libsource (lib "Miscellaneous Devices") (part "Res1"))
    )
    (comp (ref "R9")
      (value "Res1")
      (footprint "SMD_805")
      (description "Resistor")
      (fields (field (name "ALTIUM_VALUE") "10K") (field (name "PUBLISHER") "Altium Limited"))
      (libsource (lib "Miscellaneous Devices") (part "Res1"))
    )
    (comp (ref "R10")
      (value "Res1")
      (footprint "SMD_805")
      (description "Resistor")
      (fields (field (name "ALTIUM_VALUE") "220") (field (name "PUBLISHER") "Altium Limited"))
      (libsource (lib "Miscellaneous Devices") (part "Res1"))
    )
    (comp (ref "R11")
      (value "Res1")
      (footprint "SMD_805")
      (description "Resistor")
      (fields (field (name "ALTIUM_VALUE") "220") (field (name "PUBLISHER") "Altium Limited"))
      (libsource (lib "Miscellaneous Devices") (part "Res1"))
    )
    (comp (ref "R12")
      (value "Res1")
      (footprint "SMD_805")
      (description "Resistor")
      (fields (field (name "ALTIUM_VALUE") "1K") (field (name "PUBLISHER") "Altium Limited"))
      (libsource (lib "Miscellaneous Devices") (part "Res1"))
    )
    (comp (ref "R13")
      (value "Res1")
      (footprint "SMD_805")
      (description "Resistor")
      (fields (field (name "ALTIUM_VALUE") "1K") (field (name "PUBLISHER") "Altium Limited"))
      (libsource (lib "Miscellaneous Devices") (part "Res1"))
    )
    (comp (ref "R14")
      (value "Res1")
      (footprint "SMD_805")
      (description "Resistor")
      (fields (field (name "ALTIUM_VALUE") "1.5K") (field (name "PUBLISHER") "Altium Limited"))
      (libsource (lib "Miscellaneous Devices") (part "Res1"))
    )
    (comp (ref "R15")
      (value "Res1")
      (footprint "SMD_805")
      (description "Resistor")
      (fields (field (name "ALTIUM_VALUE") "10K") (field (name "PUBLISHER") "Altium Limited"))
      (libsource (lib "Miscellaneous Devices") (part "Res1"))
    )
    (comp (ref "R16")
      (value "Res1")
      (footprint "SMD_805")
      (description "Resistor")
      (fields (field (name "ALTIUM_VALUE") "10K") (field (name "PUBLISHER") "Altium Limited"))
      (libsource (lib "Miscellaneous Devices") (part "Res1"))
    )
    (comp (ref "R17")
      (value "Res1")
      (footprint "SMD_805")
      (description "Resistor")
      (fields (field (name "ALTIUM_VALUE") "220") (field (name "PUBLISHER") "Altium Limited"))
      (libsource (lib "Miscellaneous Devices") (part "Res1"))
    )
    (comp (ref "R18")
      (value "Res1")
      (footprint "SMD_805")
      (description "Resistor")
      (fields (field (name "ALTIUM_VALUE") "220") (field (name "PUBLISHER") "Altium Limited"))
      (libsource (lib "Miscellaneous Devices") (part "Res1"))
    )
    (comp (ref "R19")
      (value "Res1")
      (footprint "SMD_805")
      (description "Resistor")
      (fields (field (name "ALTIUM_VALUE") "1K") (field (name "PUBLISHER") "Altium Limited"))
      (libsource (lib "Miscellaneous Devices") (part "Res1"))
    )
    (comp (ref "R20")
      (value "Res1")
      (footprint "SMD_805")
      (description "Resistor")
      (fields (field (name "ALTIUM_VALUE") "1K") (field (name "PUBLISHER") "Altium Limited"))
      (libsource (lib "Miscellaneous Devices") (part "Res1"))
    )
    (comp (ref "R21")
      (value "Res1")
      (footprint "SMD_805")
      (description "Resistor")
      (fields (field (name "ALTIUM_VALUE") "10K") (field (name "PUBLISHER") "Altium Limited"))
      (libsource (lib "Miscellaneous Devices") (part "Res1"))
    )
    (comp (ref "R22")
      (value "Res1")
      (footprint "SMD_805")
      (description "Resistor")
      (fields (field (name "ALTIUM_VALUE") "10K") (field (name "PUBLISHER") "Altium Limited"))
      (libsource (lib "Miscellaneous Devices") (part "Res1"))
    )
    (comp (ref "R23")
      (value "Res1")
      (footprint "SMD_805")
      (description "Resistor")
      (fields (field (name "ALTIUM_VALUE") "1.5K") (field (name "PUBLISHER") "Altium Limited"))
      (libsource (lib "Miscellaneous Devices") (part "Res1"))
    )
    (comp (ref "R24")
      (value "Res1")
      (footprint "SMD_805")
      (description "Resistor")
      (fields (field (name "ALTIUM_VALUE") "4.7K") (field (name "PUBLISHER") "Altium Limited"))
      (libsource (lib "Miscellaneous Devices") (part "Res1"))
    )
    (comp (ref "R25")
      (value "Res1")
      (footprint "SMD_805")
      (description "Resistor")
      (fields (field (name "ALTIUM_VALUE") "4.7K") (field (name "PUBLISHER") "Altium Limited"))
      (libsource (lib "Miscellaneous Devices") (part "Res1"))
    )
    (comp (ref "R26")
      (value "Res1")
      (footprint "SMD_805")
      (description "Resistor")
      (fields (field (name "ALTIUM_VALUE") "4.7K") (field (name "PUBLISHER") "Altium Limited"))
      (libsource (lib "Miscellaneous Devices") (part "Res1"))
    )
    (comp (ref "R27")
      (value "Res1")
      (footprint "SMD_805")
      (description "Resistor")
      (fields (field (name "ALTIUM_VALUE") "4.7K") (field (name "PUBLISHER") "Altium Limited"))
      (libsource (lib "Miscellaneous Devices") (part "Res1"))
    )
    (comp (ref "R28")
      (value "Res1")
      (footprint "SMD_805")
      (description "Resistor")
      (fields (field (name "ALTIUM_VALUE") "4.7K") (field (name "PUBLISHER") "Altium Limited"))
      (libsource (lib "Miscellaneous Devices") (part "Res1"))
    )
    (comp (ref "R29")
      (value "Res1")
      (footprint "SMD_805")
      (description "Resistor")
      (fields (field (name "ALTIUM_VALUE") "270") (field (name "PUBLISHER") "Altium Limited"))
      (libsource (lib "Miscellaneous Devices") (part "Res1"))
    )
    (comp (ref "R30")
      (value "Res1")
      (footprint "SMD_805")
      (description "Resistor")
      (fields (field (name "ALTIUM_VALUE") "270") (field (name "PUBLISHER") "Altium Limited"))
      (libsource (lib "Miscellaneous Devices") (part "Res1"))
    )
    (comp (ref "R31")
      (value "Res1")
      (footprint "SMD_805")
      (description "Resistor")
      (fields (field (name "ALTIUM_VALUE") "100") (field (name "PUBLISHER") "Altium Limited"))
      (libsource (lib "Miscellaneous Devices") (part "Res1"))
    )
    (comp (ref "R32")
      (value "Res1")
      (footprint "SMD_805")
      (description "Resistor")
      (fields (field (name "ALTIUM_VALUE") "1.5K") (field (name "PUBLISHER") "Altium Limited"))
      (libsource (lib "Miscellaneous Devices") (part "Res1"))
    )
    (comp (ref "R33")
      (value "Res1")
      (footprint "SMD_805")
      (description "Resistor")
      (fields (field (name "ALTIUM_VALUE") "100") (field (name "PUBLISHER") "Altium Limited"))
      (libsource (lib "Miscellaneous Devices") (part "Res1"))
    )
    (comp (ref "R34")
      (value "Res1")
      (footprint "SMD_805")
      (description "Resistor")
      (fields (field (name "ALTIUM_VALUE") "100") (field (name "PUBLISHER") "Altium Limited"))
      (libsource (lib "Miscellaneous Devices") (part "Res1"))
    )
    (comp (ref "R35")
      (value "Res1")
      (footprint "SMD_805")
      (description "Resistor")
      (fields (field (name "ALTIUM_VALUE") "100") (field (name "PUBLISHER") "Altium Limited"))
      (libsource (lib "Miscellaneous Devices") (part "Res1"))
    )
    (comp (ref "R36")
      (value "Res1")
      (footprint "SMD_805")
      (description "Resistor")
      (fields (field (name "ALTIUM_VALUE") "100") (field (name "PUBLISHER") "Altium Limited"))
      (libsource (lib "Miscellaneous Devices") (part "Res1"))
    )
    (comp (ref "R37")
      (value "1K")
      (footprint "SMD_805")
      (description "Resistor")
      (fields (field (name "PUBLISHER") "Altium Limited"))
      (libsource (lib "Miscellaneous Devices") (part "Res1"))
    )
    (comp (ref "R38")
      (value "1K")
      (footprint "SMD_805")
      (description "Resistor")
      (fields (field (name "PUBLISHER") "Altium Limited"))
      (libsource (lib "Miscellaneous Devices") (part "Res1"))
    )
    (comp (ref "R39")
      (value "Res1")
      (footprint "SMD_805")
      (description "Resistor")
      (fields (field (name "ALTIUM_VALUE") "2.2K") (field (name "PUBLISHER") "Altium Limited"))
      (libsource (lib "Miscellaneous Devices") (part "Res1"))
    )
    (comp (ref "R40")
      (value "Res1")
      (footprint "SMD_805")
      (description "Resistor")
      (fields (field (name "ALTIUM_VALUE") "2.2K") (field (name "PUBLISHER") "Altium Limited"))
      (libsource (lib "Miscellaneous Devices") (part "Res1"))
    )
    (comp (ref "R41")
      (value "Res1")
      (footprint "SMD_805")
      (description "Resistor")
      (fields (field (name "ALTIUM_VALUE") "2.2K") (field (name "PUBLISHER") "Altium Limited"))
      (libsource (lib "Miscellaneous Devices") (part "Res1"))
    )
    (comp (ref "R42")
      (value "Res1")
      (footprint "SMD_805")
      (description "Resistor")
      (fields (field (name "ALTIUM_VALUE") "2.2K") (field (name "PUBLISHER") "Altium Limited"))
      (libsource (lib "Miscellaneous Devices") (part "Res1"))
    )
    (comp (ref "R43")
      (value "Res1")
      (footprint "SMD_805")
      (description "Resistor")
      (fields (field (name "ALTIUM_VALUE") "27") (field (name "PUBLISHER") "Altium Limited"))
      (libsource (lib "Miscellaneous Devices") (part "Res1"))
    )
    (comp (ref "R44")
      (value "510")
      (footprint "SMD_805")
      (description "Resistor")
      (fields (field (name "PUBLISHER") "Altium Limited"))
      (libsource (lib "Miscellaneous Devices") (part "Res1"))
    )
    (comp (ref "R45")
      (value "1K")
      (footprint "SMD_805")
      (description "Resistor")
      (fields (field (name "PUBLISHER") "Altium Limited"))
      (libsource (lib "Miscellaneous Devices") (part "Res1"))
    )
    (comp (ref "R46")
      (value "Res1")
      (footprint "SMD_805")
      (description "Resistor")
      (fields (field (name "ALTIUM_VALUE") "27") (field (name "PUBLISHER") "Altium Limited"))
      (libsource (lib "Miscellaneous Devices") (part "Res1"))
    )
    (comp (ref "R47")
      (value "2K")
      (footprint "SMD_805")
      (description "Resistor")
      (fields (field (name "PUBLISHER") "Altium Limited"))
      (libsource (lib "Miscellaneous Devices") (part "Res1"))
    )
    (comp (ref "R48")
      (value "Res1")
      (footprint "SMD_805")
      (description "Resistor")
      (fields (field (name "ALTIUM_VALUE") "1K") (field (name "PUBLISHER") "Altium Limited"))
      (libsource (lib "Miscellaneous Devices") (part "Res1"))
    )
    (comp (ref "R49")
      (value "1K")
      (footprint "SMD_805")
      (description "Resistor")
      (fields (field (name "PUBLISHER") "Altium Limited"))
      (libsource (lib "Miscellaneous Devices") (part "Res1"))
    )
    (comp (ref "R50")
      (value "510")
      (footprint "SMD_805")
      (description "Resistor")
      (fields (field (name "PUBLISHER") "Altium Limited"))
      (libsource (lib "Miscellaneous Devices") (part "Res1"))
    )
    (comp (ref "R51")
      (value "Res1")
      (footprint "SMD_805")
      (description "Resistor")
      (fields (field (name "ALTIUM_VALUE") "1K") (field (name "PUBLISHER") "Altium Limited"))
      (libsource (lib "Miscellaneous Devices") (part "Res1"))
    )
    (comp (ref "R52")
      (value "1K")
      (footprint "SMD_805")
      (description "Resistor")
      (fields (field (name "PUBLISHER") "Altium Limited"))
      (libsource (lib "Miscellaneous Devices") (part "Res1"))
    )
    (comp (ref "R53")
      (value "2K")
      (footprint "SMD_805")
      (description "Resistor")
      (fields (field (name "PUBLISHER") "Altium Limited"))
      (libsource (lib "Miscellaneous Devices") (part "Res1"))
    )
    (comp (ref "R54")
      (value "1K")
      (footprint "SMD_805")
      (description "Resistor")
      (fields (field (name "PUBLISHER") "Altium Limited"))
      (libsource (lib "Miscellaneous Devices") (part "Res1"))
    )
    (comp (ref "R55")
      (value "510")
      (footprint "SMD_805")
      (description "Resistor")
      (fields (field (name "PUBLISHER") "Altium Limited"))
      (libsource (lib "Miscellaneous Devices") (part "Res1"))
    )
    (comp (ref "R56")
      (value "Res1")
      (footprint "SMD_805")
      (description "Resistor")
      (fields (field (name "ALTIUM_VALUE") "10K") (field (name "PUBLISHER") "Altium Limited"))
      (libsource (lib "Miscellaneous Devices") (part "Res1"))
    )
    (comp (ref "R57")
      (value "1K")
      (footprint "SMD_805")
      (description "Resistor")
      (fields (field (name "PUBLISHER") "Altium Limited"))
      (libsource (lib "Miscellaneous Devices") (part "Res1"))
    )
    (comp (ref "R58")
      (value "2K")
      (footprint "SMD_805")
      (description "Resistor")
      (fields (field (name "PUBLISHER") "Altium Limited"))
      (libsource (lib "Miscellaneous Devices") (part "Res1"))
    )
    (comp (ref "R59")
      (value "Res1")
      (footprint "SMD_805")
      (description "Resistor")
      (fields (field (name "ALTIUM_VALUE") "10K") (field (name "PUBLISHER") "Altium Limited"))
      (libsource (lib "Miscellaneous Devices") (part "Res1"))
    )
    (comp (ref "R60")
      (value "Res1")
      (footprint "SMD_805")
      (description "Resistor")
      (fields (field (name "ALTIUM_VALUE") "2K") (field (name "PUBLISHER") "Altium Limited"))
      (libsource (lib "Miscellaneous Devices") (part "Res1"))
    )
    (comp (ref "R61")
      (value "1K")
      (footprint "SMD_805")
      (description "Resistor")
      (fields (field (name "PUBLISHER") "Altium Limited"))
      (libsource (lib "Miscellaneous Devices") (part "Res1"))
    )
    (comp (ref "S1")
      (value "SW DIP-8")
      (footprint "DIPSW254_8")
      (description "DIP Switch, 8 Position, SPST")
      (fields (field (name "PUBLISHER") "Altium Limited"))
      (libsource (lib "Miscellaneous Devices") (part "SW DIP-8"))
    )
    (comp (ref "S2")
      (value "SW-SPST")
      (footprint "SWTOG_SPDT_R_7101MD9")
      (description "Single-Pole, Single-Throw Switch")
      (fields (field (name "PUBLISHER") "Altium Limited"))
      (libsource (lib "Miscellaneous Devices") (part "SW-SPST"))
    )
    (comp (ref "S3")
      (value "SW-PB")
      (footprint "SWPBS_SPST_6X3X2")
      (description "Switch")
      (fields (field (name "PUBLISHER") "Altium Limited"))
      (libsource (lib "Miscellaneous Devices") (part "SW-PB"))
    )
    (comp (ref "S4")
      (value "SW-SPST")
      (footprint "KEY1")
      (description "Single-Pole, Single-Throw Switch")
      (fields (field (name "PUBLISHER") "Altium Limited"))
      (libsource (lib "Miscellaneous Devices") (part "SW-SPST"))
    )
    (comp (ref "S5")
      (value "SW-PB")
      (footprint "SWPBS_SPST_6X3X2")
      (description "Switch")
      (fields (field (name "PUBLISHER") "Altium Limited"))
      (libsource (lib "Miscellaneous Devices") (part "SW-PB"))
    )
    (comp (ref "S6")
      (value "SW-PB")
      (footprint "SWPBT_SPST_6X6X5")
      (description "Switch")
      (fields (field (name "PUBLISHER") "Altium Limited"))
      (libsource (lib "Miscellaneous Devices") (part "SW-PB"))
    )
    (comp (ref "S7")
      (value "SW-PB")
      (footprint "SWPBT_SPST_6X6X5")
      (description "Switch")
      (fields (field (name "PUBLISHER") "Altium Limited"))
      (libsource (lib "Miscellaneous Devices") (part "SW-PB"))
    )
    (comp (ref "S8")
      (value "SW-PB")
      (footprint "SWPBT_SPST_6X6X5")
      (description "Switch")
      (fields (field (name "PUBLISHER") "Altium Limited"))
      (libsource (lib "Miscellaneous Devices") (part "SW-PB"))
    )
    (comp (ref "S9")
      (value "SW-PB")
      (footprint "SWPBT_SPST_6X6X5")
      (description "Switch")
      (fields (field (name "PUBLISHER") "Altium Limited"))
      (libsource (lib "Miscellaneous Devices") (part "SW-PB"))
    )
    (comp (ref "U1")
      (value "XC3S400-4PQ208C")
      (footprint "XC3S400_PQ208")
      (description "Spartan-3 1.2V FPGA, 141 User I/Os, 208-Pin PQFP, Standard Performance, Commercial Grade")
      (fields (field (name "PUBLISHER") "Altium Limited"))
      (libsource (lib "Xilinx Spartan-3") (part "XC3S400-4PQ208C"))
    )
    (comp (ref "U2")
      (value "ULN2803A")
      (footprint "SOL18")
      (description "High-Voltage, High-Current Darlington Array")
      (fields (field (name "PUBLISHER") "Altium Limited"))
      (libsource (lib "Allegro Interface Darlington Driver") (part "ULN2803A"))
    )
    (comp (ref "U3")
      (value "STM32F103RBT6")
      (footprint "LQFP64_L")
      (description "STM32 ARM-based 32-bit MCU with 128 Kbytes Flash, 64-pin LQFP, Industrial Temperature")
      (fields (field (name "PUBLISHER") "Altium Limited"))
      (libsource (lib "ST Microcontroller 32-Bit STM32") (part "STM32F103RBT6"))
    )
    (comp (ref "U4")
      (value "LM2576HVT-3.3")
      (footprint "LM2576_SMD")
      (description "SIMPLE SWITCHER; 3A Step-Down Voltage Regulator")
      (fields
        (field (name "MANUFACTURER") "National Semiconductor")
        (field (name "DIGIKEYPARTNUMBER") "LM2576HVT-3.3-ND")
        (field (name "PUBLISHER") "Altium Limited")
      )
      (libsource (lib "NSC Switcher") (part "LM2576HVT-3.3"))
    )
    (comp (ref "U5")
      (value "LD1117DT33")
      (footprint "SOT223")
      (libsource (lib "LD1117DT33") (part "Component_1"))
    )
    (comp (ref "U6")
      (value "M74HC541B1R")
      (footprint "SO_20_W")
      (description "Octal Bus Buffer with 3 State Outputs (Non Inverted)")
      (fields (field (name "PUBLISHER") "Altium Limited"))
      (libsource (lib "ST Logic Buffer Line Driver") (part "M74HC541B1R"))
    )
    (comp (ref "U7")
      (value "7_Seg_MUX")
      (footprint "S7_MUX")
      (libsource (lib "7_Seg_MUX") (part "Component_1"))
    )
    (comp (ref "U8")
      (value "LD1117DT33")
      (footprint "SOT223")
      (libsource (lib "LD1117DT33") (part "Component_1"))
    )
    (comp (ref "U9") (value "24C512") (footprint "SO_8") (libsource (lib "EE_24C512") (part "24C512")))
    (comp (ref "U10") (value "FT232RL") (footprint "SO_28_W") (libsource (lib "FT232RL") (part "FT232RL")))
    (comp (ref "U11")
      (value "XCF02SVO20C")
      (footprint "XCF02S")
      (fields (field (name "PUBLISHER") "Altium Limited"))
      (libsource (lib "Xilinx XCF") (part "XCF02SVO20C"))
    )
    (comp (ref "U12")
      (value "LD1117DT33")
      (footprint "SOT223")
      (libsource (lib "LD1117DT33") (part "Component_1"))
    )
    (comp (ref "U13")
      (value "IS61LV25616AL")
      (footprint "SOG80_44")
      (libsource (lib "IS61LV25616AL") (part "IS61LV25616AL"))
    )
    (comp (ref "U14")
      (value "FT2232HL-Reel")
      (footprint "LQFP-64_N")
      (description "Dual High Speed USB To Multipurpose UART/FIFO IC, LQFP-64, Tape and Reel")
      (fields (field (name "PUBLISHER") "Altium Limited"))
      (libsource (lib "FTDI Communication UART") (part "FT2232HL-Reel"))
    )
    (comp (ref "U15")
      (value "M74HC541B1R")
      (footprint "DIP_20")
      (description "Octal Bus Buffer with 3 State Outputs (Non Inverted)")
      (fields (field (name "PUBLISHER") "Altium Limited"))
      (libsource (lib "ST Logic Buffer Line Driver") (part "M74HC541B1R"))
    )
    (comp (ref "U16")
      (value "93LC46A-E/SN")
      (footprint "SO_8")
      (description "1K, 128x8-bit, 2.5V Microwire Serial EEPROM, 8-Pin SOIC 150mil, Extended Temperature")
      (fields (field (name "PUBLISHER") "Altium Limited"))
      (libsource (lib "Microchip Memory Microwire Serial EEPROM") (part "93LC46A-E/SN"))
    )
    (comp (ref "U17")
      (value "MAX3232CPE")
      (footprint "SO_16")
      (description "3.0V TO 5.5V, Low-Power, up to 1Mbps, True RS-232 Transceiver Using Four 0.1µF External Capacitor")
      (fields (field (name "PUBLISHER") "Altium Limited"))
      (libsource (lib "Maxim Communication Transceiver") (part "MAX3232CPE"))
    )
    (comp (ref "USB1")
      (value "MICRO_USB")
      (footprint "MINI_USB_NEW")
      (libsource (lib "MICRO_USB") (part "MICRO_USB"))
    )
    (comp (ref "USB2")
      (value "MICRO_USB")
      (footprint "MINI_USB_NEW")
      (libsource (lib "MICRO_USB") (part "MICRO_USB"))
    )
    (comp (ref "Y1")
      (value "17.7456")
      (footprint "XTLT_RTC_ST")
      (description "Crystal Oscillator")
      (fields (field (name "PUBLISHER") "Altium Limited"))
      (libsource (lib "Miscellaneous Devices") (part "XTAL"))
    )
    (comp (ref "Y2")
      (value "12M")
      (footprint "XTAL_SMD")
      (description "Crystal Oscillator")
      (fields (field (name "PUBLISHER") "Altium Limited"))
      (libsource (lib "Miscellaneous Devices") (part "XTAL"))
    )
  )
  (nets
    (net (code "1") (name "/.") (class "Default")
      (node (ref "U6") (pin "11") (pinfunction "Y8_11") (pintype "tri_state"))
      (node (ref "U7") (pin "9") (pinfunction "._9") (pintype "passive"))
    )
    (net (code "2") (name "/._Buf") (class "Default")
      (node (ref "P10") (pin "8") (pinfunction "8_8") (pintype "passive"))
      (node (ref "U1") (pin "50") (pinfunction "IO/VREF_6_50") (pintype "bidirectional"))
      (node (ref "U6") (pin "9") (pinfunction "A8_9") (pintype "input"))
    )
    (net (code "3") (name "/A") (class "Default")
      (node (ref "U6") (pin "18") (pinfunction "Y1_18") (pintype "tri_state"))
      (node (ref "U7") (pin "2") (pinfunction "A_2") (pintype "passive"))
    )
    (net (code "4") (name "/A0") (class "Default")
      (node (ref "U1") (pin "183") (pinfunction "IO_L32P_0/GCLK6_183") (pintype "bidirectional"))
      (node (ref "U13") (pin "1") (pinfunction "A0_1") (pintype "passive"))
    )
    (net (code "5") (name "/A1") (class "Default")
      (node (ref "U1") (pin "182") (pinfunction "IO_182") (pintype "bidirectional"))
      (node (ref "U13") (pin "2") (pinfunction "A1_2") (pintype "passive"))
    )
    (net (code "6") (name "/A2") (class "Default")
      (node (ref "U1") (pin "181") (pinfunction "IO_L32N_1/GCLK5_181") (pintype "bidirectional"))
      (node (ref "U13") (pin "3") (pinfunction "A2_3") (pintype "passive"))
    )
    (net (code "7") (name "/A3") (class "Default")
      (node (ref "U1") (pin "180") (pinfunction "IO_L32P_1/GCLK4_180") (pintype "bidirectional"))
      (node (ref "U13") (pin "4") (pinfunction "A3_4") (pintype "passive"))
    )
    (net (code "8") (name "/A4") (class "Default")
      (node (ref "U1") (pin "178") (pinfunction "IO_L31N_1/VREF_1_178") (pintype "bidirectional"))
      (node (ref "U13") (pin "5") (pinfunction "A4_5") (pintype "passive"))
    )
    (net (code "9") (name "/A5") (class "Default")
      (node (ref "U1") (pin "156") (pinfunction "IO_L01N_2/VRP_2_156") (pintype "bidirectional"))
      (node (ref "U13") (pin "18") (pinfunction "A5_18") (pintype "passive"))
    )
    (net (code "10") (name "/A6") (class "Default")
      (node (ref "U1") (pin "155") (pinfunction "IO_L01P_2/VRN_2_155") (pintype "bidirectional"))
      (node (ref "U13") (pin "19") (pinfunction "A6_19") (pintype "passive"))
    )
    (net (code "11") (name "/A7") (class "Default")
      (node (ref "U1") (pin "154") (pinfunction "IO/VREF_2_154") (pintype "bidirectional"))
      (node (ref "U13") (pin "20") (pinfunction "A7_20") (pintype "passive"))
    )
    (net (code "12") (name "/A8") (class "Default")
      (node (ref "U1") (pin "152") (pinfunction "IO_L19N_2_152") (pintype "bidirectional"))
      (node (ref "U13") (pin "21") (pinfunction "A8_21") (pintype "passive"))
    )
    (net (code "13") (name "/A9") (class "Default")
      (node (ref "U1") (pin "150") (pinfunction "IO_L19P_2_150") (pintype "bidirectional"))
      (node (ref "U13") (pin "22") (pinfunction "A9_22") (pintype "passive"))
    )
    (net (code "14") (name "/A10") (class "Default")
      (node (ref "U1") (pin "5") (pinfunction "IO_L16N_7_5") (pintype "bidirectional"))
      (node (ref "U13") (pin "23") (pinfunction "A10_23") (pintype "passive"))
    )
    (net (code "15") (name "/A11") (class "Default")
      (node (ref "U1") (pin "4") (pinfunction "IO_L16P_7/VREF_7_4") (pintype "bidirectional"))
      (node (ref "U13") (pin "24") (pinfunction "A11_24") (pintype "passive"))
    )
    (net (code "16") (name "/A12") (class "Default")
      (node (ref "U1") (pin "3") (pinfunction "IO_L01N_7/VRP_7_3") (pintype "bidirectional"))
      (node (ref "U13") (pin "25") (pinfunction "A12_25") (pintype "passive"))
    )
    (net (code "17") (name "/A13") (class "Default")
      (node (ref "U1") (pin "2") (pinfunction "IO_L01P_7/VRN_7_2") (pintype "bidirectional"))
      (node (ref "U13") (pin "26") (pinfunction "A13_26") (pintype "passive"))
    )
    (net (code "18") (name "/A14") (class "Default")
      (node (ref "U1") (pin "205") (pinfunction "IO/VREF_0_205") (pintype "bidirectional"))
      (node (ref "U13") (pin "27") (pinfunction "A14_27") (pintype "passive"))
    )
    (net (code "19") (name "/A15") (class "Default")
      (node (ref "U1") (pin "187") (pinfunction "IO_L31N_0_187") (pintype "bidirectional"))
      (node (ref "U13") (pin "42") (pinfunction "A15_42") (pintype "passive"))
    )
    (net (code "20") (name "/A16") (class "Default")
      (node (ref "U1") (pin "185") (pinfunction "IO_L31P_0/VREF_0_185") (pintype "bidirectional"))
      (node (ref "U13") (pin "43") (pinfunction "A16_43") (pintype "passive"))
    )
    (net (code "21") (name "/A17") (class "Default")
      (node (ref "U1") (pin "184") (pinfunction "IO_L32N_0/GCLK7_184") (pintype "bidirectional"))
      (node (ref "U13") (pin "44") (pinfunction "A17_44") (pintype "passive"))
    )
    (net (code "22") (name "/A_Buf") (class "Default")
      (node (ref "P10") (pin "1") (pinfunction "1_1") (pintype "passive"))
      (node (ref "U1") (pin "40") (pinfunction "IO_L22N_6_40") (pintype "bidirectional"))
      (node (ref "U6") (pin "2") (pinfunction "A1_2") (pintype "input"))
    )
    (net (code "23") (name "/B") (class "Default")
      (node (ref "U6") (pin "17") (pinfunction "Y2_17") (pintype "tri_state"))
      (node (ref "U7") (pin "6") (pinfunction "B_6") (pintype "passive"))
    )
    (net (code "24") (name "/BLUE0") (class "Default")
      (node (ref "R49") (pin "2") (pinfunction "2_2") (pintype "passive"))
      (node (ref "U1") (pin "64") (pinfunction "IO_L27P_5_64") (pintype "bidirectional"))
    )
    (net (code "25") (name "/BLUE1") (class "Default")
      (node (ref "R47") (pin "2") (pinfunction "2_2") (pintype "passive"))
      (node (ref "U1") (pin "63") (pinfunction "IO_63") (pintype "bidirectional"))
    )
    (net (code "26") (name "/BLUE2") (class "Default")
      (node (ref "R45") (pin "2") (pinfunction "2_2") (pintype "passive"))
      (node (ref "U1") (pin "62") (pinfunction "IO_L10N_5/VRP_5_62") (pintype "bidirectional"))
    )
    (net (code "27") (name "/BLUE3") (class "Default")
      (node (ref "R44") (pin "2") (pinfunction "2_2") (pintype "passive"))
      (node (ref "U1") (pin "61") (pinfunction "IO_L10P_5/VRN_5_61") (pintype "bidirectional"))
    )
    (net (code "28") (name "/BOOT0") (class "Default")
      (node (ref "R9") (pin "2") (pinfunction "2_2") (pintype "passive"))
      (node (ref "S4") (pin "2") (pinfunction "NO_2") (pintype "passive"))
      (node (ref "U3") (pin "60") (pinfunction "BOOT0_60") (pintype "input"))
    )
    (net (code "29") (name "/BUT_RISE1") (class "Default")
      (node (ref "C66") (pin "2") (pinfunction "2_2") (pintype "passive"))
      (node (ref "R39") (pin "2") (pinfunction "2_2") (pintype "passive"))
      (node (ref "S6") (pin "1") (pinfunction "1_1") (pintype "passive"))
      (node (ref "U1") (pin "51") (pinfunction "IO_L01P_6/VRN_6_51") (pintype "bidirectional"))
    )
    (net (code "30") (name "/BUT_RISE2") (class "Default")
      (node (ref "C67") (pin "2") (pinfunction "2_2") (pintype "passive"))
      (node (ref "R40") (pin "2") (pinfunction "2_2") (pintype "passive"))
      (node (ref "S7") (pin "1") (pinfunction "1_1") (pintype "passive"))
      (node (ref "U1") (pin "52") (pinfunction "IO_L01N_6/VRP_6_52") (pintype "bidirectional"))
    )
    (net (code "31") (name "/BUT_RISE3") (class "Default")
      (node (ref "C68") (pin "2") (pinfunction "2_2") (pintype "passive"))
      (node (ref "R41") (pin "2") (pinfunction "2_2") (pintype "passive"))
      (node (ref "S8") (pin "1") (pinfunction "1_1") (pintype "passive"))
      (node (ref "U3") (pin "14") (pinfunction "PA0-WKUP_14") (pintype "bidirectional"))
    )
    (net (code "32") (name "/BUT_RISE4") (class "Default")
      (node (ref "C69") (pin "2") (pinfunction "2_2") (pintype "passive"))
      (node (ref "R42") (pin "2") (pinfunction "2_2") (pintype "passive"))
      (node (ref "S9") (pin "1") (pinfunction "1_1") (pintype "passive"))
      (node (ref "U3") (pin "15") (pinfunction "PA1_15") (pintype "bidirectional"))
    )
    (net (code "33") (name "/BUZZ_1") (class "Default")
      (node (ref "P3") (pin "7") (pinfunction "7_7") (pintype "passive"))
      (node (ref "U1") (pin "78") (pinfunction "IO/VREF_5_78") (pintype "bidirectional"))
      (node (ref "U2") (pin "7") (pinfunction "IN7_7") (pintype "input"))
    )
    (net (code "34") (name "/B_Buf") (class "Default")
      (node (ref "P10") (pin "2") (pinfunction "2_2") (pintype "passive"))
      (node (ref "U1") (pin "42") (pinfunction "IO_L21P_6_42") (pintype "bidirectional"))
      (node (ref "U6") (pin "3") (pinfunction "A2_3") (pintype "input"))
    )
    (net (code "35") (name "/C") (class "Default")
      (node (ref "U6") (pin "16") (pinfunction "Y3_16") (pintype "tri_state"))
      (node (ref "U7") (pin "10") (pinfunction "C_10") (pintype "passive"))
    )
    (net (code "36") (name "/CE") (class "Default")
      (node (ref "U1") (pin "176") (pinfunction "IO_L31P_1_176") (pintype "bidirectional"))
      (node (ref "U13") (pin "6") (pinfunction "~{CE}_6") (pintype "passive"))
    )
    (net (code "37") (name "/C_Buf") (class "Default")
      (node (ref "P10") (pin "3") (pinfunction "3_3") (pintype "passive"))
      (node (ref "U1") (pin "43") (pinfunction "IO_L21N_6_43") (pintype "bidirectional"))
      (node (ref "U6") (pin "4") (pinfunction "A3_4") (pintype "input"))
    )
    (net (code "38") (name "/D") (class "Default")
      (node (ref "U6") (pin "15") (pinfunction "Y4_15") (pintype "tri_state"))
      (node (ref "U7") (pin "8") (pinfunction "D_8") (pintype "passive"))
    )
    (net (code "39") (name "/D1") (class "Default")
      (node (ref "D12") (pin "1") (pinfunction "A_1") (pintype "passive"))
      (node (ref "U15") (pin "18") (pinfunction "Y1_18") (pintype "tri_state"))
    )
    (net (code "40") (name "/D2") (class "Default")
      (node (ref "D13") (pin "1") (pinfunction "A_1") (pintype "passive"))
      (node (ref "U15") (pin "17") (pinfunction "Y2_17") (pintype "tri_state"))
    )
    (net (code "41") (name "/D3") (class "Default")
      (node (ref "D14") (pin "1") (pinfunction "A_1") (pintype "passive"))
      (node (ref "U15") (pin "16") (pinfunction "Y3_16") (pintype "tri_state"))
    )
    (net (code "42") (name "/D4") (class "Default")
      (node (ref "D15") (pin "1") (pinfunction "A_1") (pintype "passive"))
      (node (ref "U15") (pin "15") (pinfunction "Y4_15") (pintype "tri_state"))
    )
    (net (code "43") (name "/D5") (class "Default")
      (node (ref "D16") (pin "1") (pinfunction "A_1") (pintype "passive"))
      (node (ref "U15") (pin "14") (pinfunction "Y5_14") (pintype "tri_state"))
    )
    (net (code "44") (name "/D6") (class "Default")
      (node (ref "D17") (pin "1") (pinfunction "A_1") (pintype "passive"))
      (node (ref "U15") (pin "13") (pinfunction "Y6_13") (pintype "tri_state"))
    )
    (net (code "45") (name "/D7") (class "Default")
      (node (ref "D18") (pin "1") (pinfunction "A_1") (pintype "passive"))
      (node (ref "U15") (pin "12") (pinfunction "Y7_12") (pintype "tri_state"))
    )
    (net (code "46") (name "/D8") (class "Default")
      (node (ref "D19") (pin "1") (pinfunction "A_1") (pintype "passive"))
      (node (ref "U15") (pin "11") (pinfunction "Y8_11") (pintype "tri_state"))
    )
    (net (code "47") (name "/DD4") (class "Default")
      (node (ref "LCD1") (pin "11") (pinfunction "D4_11") (pintype "passive"))
      (node (ref "U3") (pin "36") (pinfunction "PB15_36") (pintype "bidirectional"))
    )
    (net (code "48") (name "/DD5") (class "Default")
      (node (ref "LCD1") (pin "12") (pinfunction "D5_12") (pintype "passive"))
      (node (ref "U3") (pin "35") (pinfunction "PB14_35") (pintype "bidirectional"))
    )
    (net (code "49") (name "/DD6") (class "Default")
      (node (ref "LCD1") (pin "13") (pinfunction "D6_13") (pintype "passive"))
      (node (ref "U3") (pin "34") (pinfunction "PB13_34") (pintype "bidirectional"))
    )
    (net (code "50") (name "/DD7") (class "Default")
      (node (ref "LCD1") (pin "14") (pinfunction "D7_14") (pintype "passive"))
      (node (ref "U3") (pin "33") (pinfunction "PB12_33") (pintype "bidirectional"))
    )
    (net (code "51") (name "/DIN_92") (class "Default")
      (node (ref "U1") (pin "92") (pinfunction "IO_L27N_4/DIN/D0_92") (pintype "bidirectional"))
      (node (ref "U11") (pin "1") (pinfunction "D0_1") (pintype "tri_state"))
    )
    (net (code "52") (name "/DX_1") (class "Default")
      (node (ref "P14") (pin "1") (pinfunction "1_1") (pintype "passive"))
      (node (ref "U1") (pin "29") (pinfunction "IO_L40N_6_29") (pintype "bidirectional"))
      (node (ref "U15") (pin "2") (pinfunction "A1_2") (pintype "input"))
    )
    (net (code "53") (name "/DX_2") (class "Default")
      (node (ref "P14") (pin "2") (pinfunction "2_2") (pintype "passive"))
      (node (ref "U1") (pin "28") (pinfunction "IO_L40P_6/VREF_6_28") (pintype "bidirectional"))
      (node (ref "U15") (pin "3") (pinfunction "A2_3") (pintype "input"))
    )
    (net (code "54") (name "/DX_3") (class "Default")
      (node (ref "P14") (pin "3") (pinfunction "3_3") (pintype "passive"))
      (node (ref "U1") (pin "27") (pinfunction "IO_L40N_7/VREF_7_27") (pintype "bidirectional"))
      (node (ref "U15") (pin "4") (pinfunction "A3_4") (pintype "input"))
    )
    (net (code "55") (name "/DX_4") (class "Default")
      (node (ref "P14") (pin "4") (pinfunction "4_4") (pintype "passive"))
      (node (ref "U1") (pin "26") (pinfunction "IO_L40P_7_26") (pintype "bidirectional"))
      (node (ref "U15") (pin "5") (pinfunction "A4_5") (pintype "input"))
    )
    (net (code "56") (name "/DX_5") (class "Default")
      (node (ref "P14") (pin "5") (pinfunction "5_5") (pintype "passive"))
      (node (ref "U1") (pin "24") (pinfunction "IO_L39N_7_24") (pintype "bidirectional"))
      (node (ref "U15") (pin "6") (pinfunction "A5_6") (pintype "input"))
    )
    (net (code "57") (name "/DX_6") (class "Default")
      (node (ref "P14") (pin "6") (pinfunction "6_6") (pintype "passive"))
      (node (ref "U1") (pin "22") (pinfunction "IO_L39P_7_22") (pintype "bidirectional"))
      (node (ref "U15") (pin "7") (pinfunction "A6_7") (pintype "input"))
    )
    (net (code "58") (name "/DX_7") (class "Default")
      (node (ref "P14") (pin "7") (pinfunction "7_7") (pintype "passive"))
      (node (ref "U1") (pin "21") (pinfunction "IO_L24N_7_21") (pintype "bidirectional"))
      (node (ref "U15") (pin "8") (pinfunction "A7_8") (pintype "input"))
    )
    (net (code "59") (name "/DX_8") (class "Default")
      (node (ref "P14") (pin "8") (pinfunction "8_8") (pintype "passive"))
      (node (ref "U1") (pin "20") (pinfunction "IO_L24P_7_20") (pintype "bidirectional"))
      (node (ref "U15") (pin "9") (pinfunction "A8_9") (pintype "input"))
    )
    (net (code "60") (name "/D_Buf") (class "Default")
      (node (ref "P10") (pin "4") (pinfunction "4_4") (pintype "passive"))
      (node (ref "U1") (pin "44") (pinfunction "IO_L20P_6_44") (pintype "bidirectional"))
      (node (ref "U6") (pin "5") (pinfunction "A4_5") (pintype "input"))
    )
    (net (code "61") (name "/E") (class "Default")
      (node (ref "U6") (pin "14") (pinfunction "Y5_14") (pintype "tri_state"))
      (node (ref "U7") (pin "7") (pinfunction "E_7") (pintype "passive"))
    )
    (net (code "62") (name "/E_Buf") (class "Default")
      (node (ref "P10") (pin "5") (pinfunction "5_5") (pintype "passive"))
      (node (ref "U1") (pin "45") (pinfunction "IO_L20N_6_45") (pintype "bidirectional"))
      (node (ref "U6") (pin "6") (pinfunction "A5_6") (pintype "input"))
    )
    (net (code "63") (name "/E_LCD") (class "Default")
      (node (ref "LCD1") (pin "6") (pinfunction "E_6") (pintype "passive"))
      (node (ref "U3") (pin "37") (pinfunction "PC6_37") (pintype "bidirectional"))
    )
    (net (code "64") (name "/F") (class "Default")
      (node (ref "U6") (pin "13") (pinfunction "Y6_13") (pintype "tri_state"))
      (node (ref "U7") (pin "3") (pinfunction "F_3") (pintype "passive"))
    )
    (net (code "65") (name "/FTOU") (class "Default")
      (node (ref "U1") (pin "101") (pinfunction "IO_L01N_4/VRP_4_101") (pintype "bidirectional"))
      (node (ref "U3") (pin "61") (pinfunction "PB8_61") (pintype "bidirectional"))
    )
    (net (code "66") (name "/F_Buf") (class "Default")
      (node (ref "P10") (pin "6") (pinfunction "6_6") (pintype "passive"))
      (node (ref "U1") (pin "46") (pinfunction "IO_L19P_6_46") (pintype "bidirectional"))
      (node (ref "U6") (pin "7") (pinfunction "A6_7") (pintype "input"))
    )
    (net (code "67") (name "/G") (class "Default")
      (node (ref "U6") (pin "12") (pinfunction "Y7_12") (pintype "tri_state"))
      (node (ref "U7") (pin "11") (pinfunction "G_11") (pintype "passive"))
    )
    (net (code "68") (name "/GREEN0") (class "Default")
      (node (ref "R54") (pin "2") (pinfunction "2_2") (pintype "passive"))
      (node (ref "U1") (pin "71") (pinfunction "IO_71") (pintype "bidirectional"))
    )
    (net (code "69") (name "/GREEN1") (class "Default")
      (node (ref "R53") (pin "2") (pinfunction "2_2") (pintype "passive"))
      (node (ref "U1") (pin "68") (pinfunction "IO_L28N_5/D6_68") (pintype "bidirectional"))
    )
    (net (code "70") (name "/GREEN2") (class "Default")
      (node (ref "R52") (pin "2") (pinfunction "2_2") (pintype "passive"))
      (node (ref "U1") (pin "67") (pinfunction "IO_L28P_5/D7_67") (pintype "bidirectional"))
    )
    (net (code "71") (name "/GREEN3") (class "Default")
      (node (ref "R50") (pin "2") (pinfunction "2_2") (pintype "passive"))
      (node (ref "U1") (pin "65") (pinfunction "IO_L27N_5/VREF_5_65") (pintype "bidirectional"))
    )
    (net (code "72") (name "/G_Buf") (class "Default")
      (node (ref "P10") (pin "7") (pinfunction "7_7") (pintype "passive"))
      (node (ref "U1") (pin "48") (pinfunction "IO_L19N_6_48") (pintype "bidirectional"))
      (node (ref "U6") (pin "8") (pinfunction "A7_8") (pintype "input"))
    )
    (net (code "73") (name "/HSYNC") (class "Default")
      (node (ref "R37") (pin "2") (pinfunction "2_2") (pintype "passive"))
      (node (ref "U1") (pin "57") (pinfunction "IO_L01P_5/CS_B_57") (pintype "bidirectional"))
    )
    (net (code "74") (name "/INT_B_83") (class "Default")
      (node (ref "R27") (pin "1") (pinfunction "1_1") (pintype "passive"))
      (node (ref "R31") (pin "1") (pinfunction "1_1") (pintype "passive"))
      (node (ref "U1") (pin "103") (pinfunction "DONE_103") (pintype "bidirectional"))
      (node (ref "U1") (pin "83") (pinfunction "IO_L31N_4/INIT_B_83") (pintype "bidirectional"))
      (node (ref "U11") (pin "10") (pinfunction "~{CE}_10") (pintype "input"))
    )
    (net (code "75") (name "/IO0") (class "Default")
      (node (ref "U1") (pin "175") (pinfunction "IO_175") (pintype "bidirectional"))
      (node (ref "U13") (pin "7") (pinfunction "I/O0_7") (pintype "passive"))
    )
    (net (code "76") (name "/IO1") (class "Default")
      (node (ref "U1") (pin "172") (pinfunction "IO_L28N_1_172") (pintype "bidirectional"))
      (node (ref "U13") (pin "8") (pinfunction "I/O1_8") (pintype "passive"))
    )
    (net (code "77") (name "/IO2") (class "Default")
      (node (ref "U1") (pin "171") (pinfunction "IO_L28P_1_171") (pintype "bidirectional"))
      (node (ref "U13") (pin "9") (pinfunction "I/O2_9") (pintype "passive"))
    )
    (net (code "78") (name "/IO3") (class "Default")
      (node (ref "U1") (pin "169") (pinfunction "IO_L27N_1_169") (pintype "bidirectional"))
      (node (ref "U13") (pin "10") (pinfunction "I/O3_10") (pintype "passive"))
    )
    (net (code "79") (name "/IO4") (class "Default")
      (node (ref "U1") (pin "168") (pinfunction "IO_L27P_1_168") (pintype "bidirectional"))
      (node (ref "U13") (pin "13") (pinfunction "I/O4_13") (pintype "passive"))
    )
    (net (code "80") (name "/IO5") (class "Default")
      (node (ref "U1") (pin "167") (pinfunction "IO_167") (pintype "bidirectional"))
      (node (ref "U13") (pin "14") (pinfunction "I/O5_14") (pintype "passive"))
    )
    (net (code "81") (name "/IO6") (class "Default")
      (node (ref "U1") (pin "166") (pinfunction "IO_L10N_1/VREF_1_166") (pintype "bidirectional"))
      (node (ref "U13") (pin "15") (pinfunction "I/O6_15") (pintype "passive"))
    )
    (net (code "82") (name "/IO7") (class "Default")
      (node (ref "U1") (pin "165") (pinfunction "IO_L10P_1_165") (pintype "bidirectional"))
      (node (ref "U13") (pin "16") (pinfunction "I/O7_16") (pintype "passive"))
    )
    (net (code "83") (name "/IO8") (class "Default")
      (node (ref "U1") (pin "204") (pinfunction "IO_L01N_0/VRP_0_204") (pintype "bidirectional"))
      (node (ref "U13") (pin "29") (pinfunction "I/O8_29") (pintype "passive"))
    )
    (net (code "84") (name "/IO9") (class "Default")
      (node (ref "U1") (pin "203") (pinfunction "IO_L01P_0/VRN_0_203") (pintype "bidirectional"))
      (node (ref "U13") (pin "30") (pinfunction "I/O9_30") (pintype "passive"))
    )
    (net (code "85") (name "/IO10") (class "Default")
      (node (ref "U1") (pin "200") (pinfunction "IO/VREF_0_200") (pintype "bidirectional"))
      (node (ref "U13") (pin "31") (pinfunction "I/O10_31") (pintype "passive"))
    )
    (net (code "86") (name "/IO11") (class "Default")
      (node (ref "U1") (pin "199") (pinfunction "IO_L25N_0_199") (pintype "bidirectional"))
      (node (ref "U13") (pin "32") (pinfunction "I/O11_32") (pintype "passive"))
    )
    (net (code "87") (name "/IO12") (class "Default")
      (node (ref "U1") (pin "198") (pinfunction "IO_L25P_0_198") (pintype "bidirectional"))
      (node (ref "U13") (pin "35") (pinfunction "I/O12_35") (pintype "passive"))
    )
    (net (code "88") (name "/IO13") (class "Default")
      (node (ref "U1") (pin "197") (pinfunction "IO_197") (pintype "bidirectional"))
      (node (ref "U13") (pin "36") (pinfunction "I/O13_36") (pintype "passive"))
    )
    (net (code "89") (name "/IO14") (class "Default")
      (node (ref "U1") (pin "196") (pinfunction "IO_L27N_0_196") (pintype "bidirectional"))
      (node (ref "U13") (pin "37") (pinfunction "I/O14_37") (pintype "passive"))
    )
    (net (code "90") (name "/IO15") (class "Default")
      (node (ref "U1") (pin "194") (pinfunction "IO_L27P_0_194") (pintype "bidirectional"))
      (node (ref "U13") (pin "38") (pinfunction "I/O15_38") (pintype "passive"))
    )
    (net (code "91") (name "/I{slash}O_P79_GCLK0") (class "Default")
      (node (ref "OSC1") (pin "3") (pinfunction "OUT_3") (pintype "passive"))
      (node (ref "U1") (pin "79") (pinfunction "IO_L32P_4/GCLK0_79") (pintype "bidirectional"))
    )
    (net (code "92") (name "/K_1") (class "Default")
      (node (ref "P7") (pin "1") (pinfunction "1_1") (pintype "passive"))
      (node (ref "S1") (pin "1") (pinfunction "A1_1") (pintype "passive"))
      (node (ref "U1") (pin "10") (pinfunction "IO_L20P_7_10") (pintype "bidirectional"))
    )
    (net (code "93") (name "/K_2") (class "Default")
      (node (ref "P7") (pin "2") (pinfunction "2_2") (pintype "passive"))
      (node (ref "S1") (pin "2") (pinfunction "A2_2") (pintype "passive"))
      (node (ref "U1") (pin "11") (pinfunction "IO_L20N_7_11") (pintype "bidirectional"))
    )
    (net (code "94") (name "/K_3") (class "Default")
      (node (ref "P7") (pin "3") (pinfunction "3_3") (pintype "passive"))
      (node (ref "S1") (pin "3") (pinfunction "A3_3") (pintype "passive"))
      (node (ref "U1") (pin "12") (pinfunction "IO_L21P_7_12") (pintype "bidirectional"))
    )
    (net (code "95") (name "/K_4") (class "Default")
      (node (ref "P7") (pin "4") (pinfunction "4_4") (pintype "passive"))
      (node (ref "S1") (pin "4") (pinfunction "A4_4") (pintype "passive"))
      (node (ref "U1") (pin "13") (pinfunction "IO_L21N_7_13") (pintype "bidirectional"))
    )
    (net (code "96") (name "/K_5") (class "Default")
      (node (ref "P7") (pin "5") (pinfunction "5_5") (pintype "passive"))
      (node (ref "S1") (pin "5") (pinfunction "A5_5") (pintype "passive"))
      (node (ref "U1") (pin "15") (pinfunction "IO_L22P_7_15") (pintype "bidirectional"))
    )
    (net (code "97") (name "/K_6") (class "Default")
      (node (ref "P7") (pin "6") (pinfunction "6_6") (pintype "passive"))
      (node (ref "S1") (pin "6") (pinfunction "A6_6") (pintype "passive"))
      (node (ref "U1") (pin "16") (pinfunction "IO_L22N_7_16") (pintype "bidirectional"))
    )
    (net (code "98") (name "/K_7") (class "Default")
      (node (ref "P7") (pin "7") (pinfunction "7_7") (pintype "passive"))
      (node (ref "S1") (pin "7") (pinfunction "A7_7") (pintype "passive"))
      (node (ref "U1") (pin "18") (pinfunction "IO_L23P_7_18") (pintype "bidirectional"))
    )
    (net (code "99") (name "/K_8") (class "Default")
      (node (ref "P7") (pin "8") (pinfunction "8_8") (pintype "passive"))
      (node (ref "S1") (pin "8") (pinfunction "A8_8") (pintype "passive"))
      (node (ref "U1") (pin "19") (pinfunction "IO_L23N_7_19") (pintype "bidirectional"))
    )
    (net (code "100") (name "/LB") (class "Default")
      (node (ref "U1") (pin "191") (pinfunction "IO_L30N_0_191") (pintype "bidirectional"))
      (node (ref "U13") (pin "39") (pinfunction "~{LB}_39") (pintype "passive"))
    )
    (net (code "101") (name "/MOTOR_1") (class "Default")
      (node (ref "P3") (pin "8") (pinfunction "8_8") (pintype "passive"))
      (node (ref "U1") (pin "39") (pinfunction "IO_L22P_6_39") (pintype "bidirectional"))
      (node (ref "U2") (pin "8") (pinfunction "IN8_8") (pintype "input"))
    )
    (net (code "102") (name "/NRST") (class "Default")
      (node (ref "C41") (pin "2") (pinfunction "2_2") (pintype "passive"))
      (node (ref "P4") (pin "3") (pinfunction "3_3") (pintype "passive"))
      (node (ref "R8") (pin "1") (pinfunction "1_1") (pintype "passive"))
      (node (ref "S3") (pin "2") (pinfunction "2_2") (pintype "passive"))
      (node (ref "U3") (pin "7") (pinfunction "NRST_7") (pintype "bidirectional"))
    )
    (net (code "103") (name "/OE") (class "Default")
      (node (ref "U1") (pin "189") (pinfunction "IO_189") (pintype "bidirectional"))
      (node (ref "U13") (pin "41") (pinfunction "~{OE}_41") (pintype "passive"))
    )
    (net (code "104") (name "/OSC_IN") (class "Default")
      (node (ref "C24") (pin "2") (pinfunction "2_2") (pintype "passive"))
      (node (ref "U3") (pin "5") (pinfunction "OSC_IN/PD0_5") (pintype "input"))
      (node (ref "Y1") (pin "2") (pinfunction "OSC2_2") (pintype "passive"))
    )
    (net (code "105") (name "/OSC_OUT") (class "Default")
      (node (ref "C33") (pin "2") (pinfunction "2_2") (pintype "passive"))
      (node (ref "U3") (pin "6") (pinfunction "OSC_OUT/PD1_6") (pintype "output"))
      (node (ref "Y1") (pin "1") (pinfunction "OSC1_1") (pintype "passive"))
    )
    (net (code "106") (name "/P1") (class "Default")
      (node (ref "P9") (pin "1") (pinfunction "1_1") (pintype "passive"))
      (node (ref "U3") (pin "45") (pinfunction "PA12_45") (pintype "bidirectional"))
    )
    (net (code "107") (name "/P2") (class "Default")
      (node (ref "P9") (pin "7") (pinfunction "7_7") (pintype "passive"))
      (node (ref "U3") (pin "26") (pinfunction "PB0_26") (pintype "bidirectional"))
    )
    (net (code "108") (name "/P3") (class "Default")
      (node (ref "P9") (pin "6") (pinfunction "6_6") (pintype "passive"))
      (node (ref "U3") (pin "27") (pinfunction "PB1_27") (pintype "bidirectional"))
    )
    (net (code "109") (name "/P4") (class "Default")
      (node (ref "P9") (pin "5") (pinfunction "5_5") (pintype "passive"))
      (node (ref "R3") (pin "2") (pinfunction "2_2") (pintype "passive"))
      (node (ref "U3") (pin "28") (pinfunction "PB2/BOOT1_28") (pintype "bidirectional"))
    )
    (net (code "110") (name "/P5") (class "Default")
      (node (ref "P9") (pin "4") (pinfunction "4_4") (pintype "passive"))
      (node (ref "U3") (pin "29") (pinfunction "PB10_29") (pintype "bidirectional"))
    )
    (net (code "111") (name "/P6") (class "Default")
      (node (ref "P9") (pin "3") (pinfunction "3_3") (pintype "passive"))
      (node (ref "U3") (pin "30") (pinfunction "PB11_30") (pintype "bidirectional"))
    )
    (net (code "112") (name "/P7") (class "Default")
      (node (ref "P9") (pin "13") (pinfunction "13_13") (pintype "passive"))
      (node (ref "U3") (pin "8") (pinfunction "PC0_8") (pintype "bidirectional"))
    )
    (net (code "113") (name "/P8") (class "Default")
      (node (ref "P9") (pin "12") (pinfunction "12_12") (pintype "passive"))
      (node (ref "U3") (pin "9") (pinfunction "PC1_9") (pintype "bidirectional"))
    )
    (net (code "114") (name "/P9") (class "Default")
      (node (ref "P9") (pin "11") (pinfunction "11_11") (pintype "passive"))
      (node (ref "U3") (pin "10") (pinfunction "PC2_10") (pintype "bidirectional"))
    )
    (net (code "115") (name "/P10") (class "Default")
      (node (ref "P9") (pin "10") (pinfunction "10_10") (pintype "passive"))
      (node (ref "U3") (pin "11") (pinfunction "PC3_11") (pintype "bidirectional"))
    )
    (net (code "116") (name "/P11") (class "Default")
      (node (ref "P9") (pin "9") (pinfunction "9_9") (pintype "passive"))
      (node (ref "U3") (pin "24") (pinfunction "PC4_24") (pintype "bidirectional"))
    )
    (net (code "117") (name "/P12") (class "Default")
      (node (ref "P9") (pin "8") (pinfunction "8_8") (pintype "passive"))
      (node (ref "U3") (pin "25") (pinfunction "PC5_25") (pintype "bidirectional"))
    )
    (net (code "118") (name "/P13") (class "Default")
      (node (ref "P9") (pin "2") (pinfunction "2_2") (pintype "passive"))
      (node (ref "U3") (pin "40") (pinfunction "PC9_40") (pintype "bidirectional"))
    )
    (net (code "119") (name "/P14") (class "Default")
      (node (ref "P9") (pin "16") (pinfunction "16_16") (pintype "passive"))
      (node (ref "U3") (pin "2") (pinfunction "PC13-TAMPER-RTC_2") (pintype "bidirectional"))
    )
    (net (code "120") (name "/P15") (class "Default")
      (node (ref "P9") (pin "15") (pinfunction "15_15") (pintype "passive"))
      (node (ref "U3") (pin "3") (pinfunction "PC14-OSC32_IN_3") (pintype "bidirectional"))
    )
    (net (code "121") (name "/P16") (class "Default")
      (node (ref "P9") (pin "14") (pinfunction "14_14") (pintype "passive"))
      (node (ref "U3") (pin "4") (pinfunction "PC15-OSC32_OUT_4") (pintype "bidirectional"))
    )
    (net (code "122") (name "/PA2") (class "Default")
      (node (ref "U1") (pin "115") (pinfunction "IO_L20N_3_115") (pintype "bidirectional"))
      (node (ref "U3") (pin "16") (pinfunction "PA2_16") (pintype "bidirectional"))
    )
    (net (code "123") (name "/PA3") (class "Default")
      (node (ref "U1") (pin "114") (pinfunction "IO_L20P_3_114") (pintype "bidirectional"))
      (node (ref "U3") (pin "17") (pinfunction "PA3_17") (pintype "bidirectional"))
    )
    (net (code "124") (name "/PA4") (class "Default")
      (node (ref "U1") (pin "113") (pinfunction "IO_L19N_3_113") (pintype "bidirectional"))
      (node (ref "U3") (pin "20") (pinfunction "PA4_20") (pintype "bidirectional"))
    )
    (net (code "125") (name "/PA5") (class "Default")
      (node (ref "U1") (pin "111") (pinfunction "IO_L19P_3_111") (pintype "bidirectional"))
      (node (ref "U3") (pin "21") (pinfunction "PA5_21") (pintype "bidirectional"))
    )
    (net (code "126") (name "/PA6") (class "Default")
      (node (ref "U1") (pin "109") (pinfunction "IO_L17N_3_109") (pintype "bidirectional"))
      (node (ref "U3") (pin "22") (pinfunction "PA6_22") (pintype "bidirectional"))
    )
    (net (code "127") (name "/PA7") (class "Default")
      (node (ref "U1") (pin "108") (pinfunction "IO_L17P_3/VREF_3_108") (pintype "bidirectional"))
      (node (ref "U3") (pin "23") (pinfunction "PA7_23") (pintype "bidirectional"))
    )
    (net (code "128") (name "/PA8") (class "Default")
      (node (ref "U1") (pin "107") (pinfunction "IO_L01N_3/VRP_3_107") (pintype "bidirectional"))
      (node (ref "U3") (pin "41") (pinfunction "PA8_41") (pintype "bidirectional"))
    )
    (net (code "129") (name "/PA11") (class "Default")
      (node (ref "U1") (pin "106") (pinfunction "IO_L01P_3/VRN_3_106") (pintype "bidirectional"))
      (node (ref "U3") (pin "44") (pinfunction "PA11_44") (pintype "bidirectional"))
    )
    (net (code "130") (name "/PB50") (class "Default")
      (node (ref "U1") (pin "147") (pinfunction "IO_L21N_2_147") (pintype "bidirectional"))
      (node (ref "U3") (pin "50") (pinfunction "PA15/JTDI_50") (pintype "bidirectional"))
    )
    (net (code "131") (name "/PB55") (class "Default")
      (node (ref "U1") (pin "138") (pinfunction "IO_L24P_2_138") (pintype "bidirectional"))
      (node (ref "U3") (pin "57") (pinfunction "PB5_57") (pintype "bidirectional"))
    )
    (net (code "132") (name "/PB56") (class "Default")
      (node (ref "U1") (pin "139") (pinfunction "IO_L24N_2_139") (pintype "bidirectional"))
      (node (ref "U3") (pin "56") (pinfunction "PB4/JNTRST_56") (pintype "bidirectional"))
    )
    (net (code "133") (name "/PB57") (class "Default")
      (node (ref "U1") (pin "140") (pinfunction "IO_L23P_2_140") (pintype "bidirectional"))
      (node (ref "U3") (pin "55") (pinfunction "PB3/JTDO_55") (pintype "bidirectional"))
    )
    (net (code "134") (name "/PC51") (class "Default")
      (node (ref "U1") (pin "143") (pinfunction "IO_L22P_2_143") (pintype "bidirectional"))
      (node (ref "U3") (pin "53") (pinfunction "PC12_53") (pintype "bidirectional"))
    )
    (net (code "135") (name "/PC52") (class "Default")
      (node (ref "U1") (pin "144") (pinfunction "IO_L22N_2_144") (pintype "bidirectional"))
      (node (ref "U3") (pin "52") (pinfunction "PC11_52") (pintype "bidirectional"))
    )
    (net (code "136") (name "/PC53") (class "Default")
      (node (ref "U1") (pin "146") (pinfunction "IO_L21P_2_146") (pintype "bidirectional"))
      (node (ref "U3") (pin "51") (pinfunction "PC10_51") (pintype "bidirectional"))
    )
    (net (code "137") (name "/PC54") (class "Default")
      (node (ref "U1") (pin "141") (pinfunction "IO_L23N_2/VREF_2_141") (pintype "bidirectional"))
      (node (ref "U3") (pin "54") (pinfunction "PD2_54") (pintype "bidirectional"))
    )
    (net (code "138") (name "/PP81") (class "Default")
      (node (ref "P11") (pin "24") (pinfunction "24_24") (pintype "passive"))
      (node (ref "U1") (pin "80") (pinfunction "IO_L32N_4/GCLK1_80") (pintype "bidirectional"))
    )
    (net (code "139") (name "/PP85") (class "Default")
      (node (ref "P11") (pin "23") (pinfunction "23_23") (pintype "passive"))
      (node (ref "U1") (pin "81") (pinfunction "IO_L31P_4/DOUT/BUSY_81") (pintype "bidirectional"))
    )
    (net (code "140") (name "/PP86") (class "Default")
      (node (ref "P11") (pin "22") (pinfunction "22_22") (pintype "passive"))
      (node (ref "U1") (pin "85") (pinfunction "IO/VREF_4_85") (pintype "bidirectional"))
    )
    (net (code "141") (name "/PP87") (class "Default")
      (node (ref "P11") (pin "21") (pinfunction "21_21") (pintype "passive"))
      (node (ref "U1") (pin "86") (pinfunction "IO_L30P_4/D3_86") (pintype "bidirectional"))
    )
    (net (code "142") (name "/PP90") (class "Default")
      (node (ref "P11") (pin "20") (pinfunction "20_20") (pintype "passive"))
      (node (ref "U1") (pin "87") (pinfunction "IO_L30N_4/D2_87") (pintype "bidirectional"))
    )
    (net (code "143") (name "/PP93") (class "Default")
      (node (ref "P11") (pin "19") (pinfunction "19_19") (pintype "passive"))
      (node (ref "U1") (pin "90") (pinfunction "IO_L27P_4/D1_90") (pintype "bidirectional"))
    )
    (net (code "144") (name "/PP94") (class "Default")
      (node (ref "P11") (pin "18") (pinfunction "18_18") (pintype "passive"))
      (node (ref "U1") (pin "93") (pinfunction "IO_93") (pintype "bidirectional"))
    )
    (net (code "145") (name "/PP95") (class "Default")
      (node (ref "P11") (pin "17") (pinfunction "17_17") (pintype "passive"))
      (node (ref "U1") (pin "94") (pinfunction "IO_L25P_4_94") (pintype "bidirectional"))
    )
    (net (code "146") (name "/PP96") (class "Default")
      (node (ref "P11") (pin "16") (pinfunction "16_16") (pintype "passive"))
      (node (ref "U1") (pin "95") (pinfunction "IO_L25N_4_95") (pintype "bidirectional"))
    )
    (net (code "147") (name "/PP97") (class "Default")
      (node (ref "P11") (pin "15") (pinfunction "15_15") (pintype "passive"))
      (node (ref "U1") (pin "96") (pinfunction "IO/VREF_4_96") (pintype "bidirectional"))
    )
    (net (code "148") (name "/PP100") (class "Default")
      (node (ref "P11") (pin "14") (pinfunction "14_14") (pintype "passive"))
      (node (ref "U1") (pin "97") (pinfunction "IO_97") (pintype "bidirectional"))
    )
    (net (code "149") (name "/PP122") (class "Default")
      (node (ref "P11") (pin "13") (pinfunction "13_13") (pintype "passive"))
      (node (ref "U1") (pin "100") (pinfunction "IO_L01P_4/VRN_4_100") (pintype "bidirectional"))
    )
    (net (code "150") (name "/PP123") (class "Default")
      (node (ref "P11") (pin "12") (pinfunction "12_12") (pintype "passive"))
      (node (ref "U1") (pin "122") (pinfunction "IO_L23P_3/VREF_3_122") (pintype "bidirectional"))
    )
    (net (code "151") (name "/PP124") (class "Default")
      (node (ref "P11") (pin "11") (pinfunction "11_11") (pintype "passive"))
      (node (ref "U1") (pin "123") (pinfunction "IO_L23N_3_123") (pintype "bidirectional"))
    )
    (net (code "152") (name "/PP125") (class "Default")
      (node (ref "P11") (pin "10") (pinfunction "10_10") (pintype "passive"))
      (node (ref "U1") (pin "124") (pinfunction "IO_L24P_3_124") (pintype "bidirectional"))
    )
    (net (code "153") (name "/PP126") (class "Default")
      (node (ref "P11") (pin "9") (pinfunction "9_9") (pintype "passive"))
      (node (ref "U1") (pin "125") (pinfunction "IO_L24N_3_125") (pintype "bidirectional"))
    )
    (net (code "154") (name "/PP128") (class "Default")
      (node (ref "P11") (pin "8") (pinfunction "8_8") (pintype "passive"))
      (node (ref "U1") (pin "126") (pinfunction "IO_L39P_3_126") (pintype "bidirectional"))
    )
    (net (code "155") (name "/PP130") (class "Default")
      (node (ref "P11") (pin "7") (pinfunction "7_7") (pintype "passive"))
      (node (ref "U1") (pin "128") (pinfunction "IO_L39N_3_128") (pintype "bidirectional"))
    )
    (net (code "156") (name "/PP131") (class "Default")
      (node (ref "P11") (pin "6") (pinfunction "6_6") (pintype "passive"))
      (node (ref "U1") (pin "130") (pinfunction "IO_L40P_3_130") (pintype "bidirectional"))
    )
    (net (code "157") (name "/PP132") (class "Default")
      (node (ref "P11") (pin "5") (pinfunction "5_5") (pintype "passive"))
      (node (ref "U1") (pin "131") (pinfunction "IO_L40N_3/VREF_3_131") (pintype "bidirectional"))
    )
    (net (code "158") (name "/PP133") (class "Default")
      (node (ref "P11") (pin "4") (pinfunction "4_4") (pintype "passive"))
      (node (ref "U1") (pin "132") (pinfunction "IO_L40P_2/VREF_2_132") (pintype "bidirectional"))
    )
    (net (code "159") (name "/PP135") (class "Default")
      (node (ref "P11") (pin "3") (pinfunction "3_3") (pintype "passive"))
      (node (ref "U1") (pin "133") (pinfunction "IO_L40N_2_133") (pintype "bidirectional"))
    )
    (net (code "160") (name "/PP147") (class "Default")
      (node (ref "P11") (pin "2") (pinfunction "2_2") (pintype "passive"))
      (node (ref "U1") (pin "135") (pinfunction "IO_L39P_2_135") (pintype "bidirectional"))
    )
    (net (code "161") (name "/PP148") (class "Default")
      (node (ref "P11") (pin "1") (pinfunction "1_1") (pintype "passive"))
      (node (ref "U1") (pin "137") (pinfunction "IO_L39N_2_137") (pintype "bidirectional"))
    )
    (net (code "162") (name "/RED0") (class "Default")
      (node (ref "R61") (pin "2") (pinfunction "2_2") (pintype "passive"))
      (node (ref "U1") (pin "77") (pinfunction "IO_L32N_5/GCLK3_77") (pintype "bidirectional"))
    )
    (net (code "163") (name "/RED1") (class "Default")
      (node (ref "R58") (pin "2") (pinfunction "2_2") (pintype "passive"))
      (node (ref "U1") (pin "76") (pinfunction "IO_L32P_5/GCLK2_76") (pintype "bidirectional"))
    )
    (net (code "164") (name "/RED2") (class "Default")
      (node (ref "R57") (pin "2") (pinfunction "2_2") (pintype "passive"))
      (node (ref "U1") (pin "74") (pinfunction "IO_L31N_5/D4_74") (pintype "bidirectional"))
    )
    (net (code "165") (name "/RED3") (class "Default")
      (node (ref "R55") (pin "2") (pinfunction "2_2") (pintype "passive"))
      (node (ref "U1") (pin "72") (pinfunction "IO_L31P_5/D5_72") (pintype "bidirectional"))
    )
    (net (code "166") (name "/REL_1") (class "Default")
      (node (ref "P3") (pin "5") (pinfunction "5_5") (pintype "passive"))
      (node (ref "U1") (pin "36") (pinfunction "IO_L23P_6_36") (pintype "bidirectional"))
      (node (ref "U2") (pin "5") (pinfunction "IN5_5") (pintype "input"))
    )
    (net (code "167") (name "/REL_2") (class "Default")
      (node (ref "P3") (pin "6") (pinfunction "6_6") (pintype "passive"))
      (node (ref "U1") (pin "37") (pinfunction "IO_L23N_6_37") (pintype "bidirectional"))
      (node (ref "U2") (pin "6") (pinfunction "IN6_6") (pintype "input"))
    )
    (net (code "168") (name "/RS") (class "Default")
      (node (ref "LCD1") (pin "4") (pinfunction "RS_4") (pintype "passive"))
      (node (ref "U3") (pin "39") (pinfunction "PC8_39") (pintype "bidirectional"))
    )
    (net (code "169") (name "/RW") (class "Default")
      (node (ref "LCD1") (pin "5") (pinfunction "RW_5") (pintype "passive"))
      (node (ref "U3") (pin "38") (pinfunction "PC7_38") (pintype "bidirectional"))
    )
    (net (code "170") (name "/RXD0(PA9)") (class "Default")
      (node (ref "U10") (pin "1") (pinfunction "TXD_1") (pintype "passive"))
      (node (ref "U3") (pin "42") (pinfunction "PA9_42") (pintype "bidirectional"))
    )
    (net (code "171") (name "/RXD_FT2232{slash}MPSSE_TDI") (class "Default")
      (node (ref "U1") (pin "148") (pinfunction "IO_L20P_2_148") (pintype "bidirectional"))
      (node (ref "U14") (pin "39") (pinfunction "BDBUS1_39") (pintype "bidirectional"))
    )
    (net (code "172") (name "/RX_232") (class "Default")
      (node (ref "U1") (pin "7") (pinfunction "IO_L19P_7_7") (pintype "bidirectional"))
      (node (ref "U17") (pin "12") (pinfunction "R1OUT_12") (pintype "output"))
    )
    (net (code "173") (name "/S1") (class "Default")
      (node (ref "R10") (pin "1") (pinfunction "1_1") (pintype "passive"))
      (node (ref "U7") (pin "12") (pinfunction "S1_12") (pintype "passive"))
    )
    (net (code "174") (name "/S2") (class "Default")
      (node (ref "R11") (pin "1") (pinfunction "1_1") (pintype "passive"))
      (node (ref "U7") (pin "5") (pinfunction "S2_5") (pintype "passive"))
    )
    (net (code "175") (name "/S3") (class "Default")
      (node (ref "R17") (pin "1") (pinfunction "1_1") (pintype "passive"))
      (node (ref "U7") (pin "4") (pinfunction "S3_4") (pintype "passive"))
    )
    (net (code "176") (name "/S4") (class "Default")
      (node (ref "R18") (pin "1") (pinfunction "1_1") (pintype "passive"))
      (node (ref "U7") (pin "1") (pinfunction "S4_1") (pintype "passive"))
    )
    (net (code "177") (name "/SCL") (class "Default")
      (node (ref "R25") (pin "2") (pinfunction "2_2") (pintype "passive"))
      (node (ref "U3") (pin "58") (pinfunction "PB6_58") (pintype "bidirectional"))
      (node (ref "U9") (pin "6") (pinfunction "SCL_6") (pintype "passive"))
    )
    (net (code "178") (name "/SDA") (class "Default")
      (node (ref "R24") (pin "2") (pinfunction "2_2") (pintype "passive"))
      (node (ref "U3") (pin "59") (pinfunction "PB7_59") (pintype "bidirectional"))
      (node (ref "U9") (pin "5") (pinfunction "SDA_5") (pintype "passive"))
    )
    (net (code "179") (name "/SO1") (class "Default")
      (node (ref "R12") (pin "1") (pinfunction "1_1") (pintype "passive"))
      (node (ref "U1") (pin "116") (pinfunction "IO_L21P_3_116") (pintype "bidirectional"))
    )
    (net (code "180") (name "/SO2") (class "Default")
      (node (ref "R13") (pin "1") (pinfunction "1_1") (pintype "passive"))
      (node (ref "U1") (pin "117") (pinfunction "IO_L21N_3_117") (pintype "bidirectional"))
    )
    (net (code "181") (name "/SO3") (class "Default")
      (node (ref "R19") (pin "1") (pinfunction "1_1") (pintype "passive"))
      (node (ref "U1") (pin "119") (pinfunction "IO_L22P_3_119") (pintype "bidirectional"))
    )
    (net (code "182") (name "/SO4") (class "Default")
      (node (ref "R20") (pin "1") (pinfunction "1_1") (pintype "passive"))
      (node (ref "U1") (pin "120") (pinfunction "IO_L22N_3_120") (pintype "bidirectional"))
    )
    (net (code "183") (name "/STEP_1") (class "Default")
      (node (ref "P3") (pin "1") (pinfunction "1_1") (pintype "passive"))
      (node (ref "U1") (pin "31") (pinfunction "IO_L39P_6_31") (pintype "bidirectional"))
      (node (ref "U2") (pin "1") (pinfunction "IN1_1") (pintype "input"))
    )
    (net (code "184") (name "/STEP_2") (class "Default")
      (node (ref "P3") (pin "2") (pinfunction "2_2") (pintype "passive"))
      (node (ref "U1") (pin "33") (pinfunction "IO_L39N_6_33") (pintype "bidirectional"))
      (node (ref "U2") (pin "2") (pinfunction "IN2_2") (pintype "input"))
    )
    (net (code "185") (name "/STEP_3") (class "Default")
      (node (ref "P3") (pin "3") (pinfunction "3_3") (pintype "passive"))
      (node (ref "U1") (pin "34") (pinfunction "IO_L24P_6_34") (pintype "bidirectional"))
      (node (ref "U2") (pin "3") (pinfunction "IN3_3") (pintype "input"))
    )
    (net (code "186") (name "/STEP_4") (class "Default")
      (node (ref "P3") (pin "4") (pinfunction "4_4") (pintype "passive"))
      (node (ref "U1") (pin "35") (pinfunction "IO_L24N_6/VREF_6_35") (pintype "bidirectional"))
      (node (ref "U2") (pin "4") (pinfunction "IN4_4") (pintype "input"))
    )
    (net (code "187") (name "/SWCLK") (class "Default")
      (node (ref "P4") (pin "2") (pinfunction "2_2") (pintype "passive"))
      (node (ref "R2") (pin "1") (pinfunction "1_1") (pintype "passive"))
      (node (ref "U3") (pin "49") (pinfunction "PA14/JTCK/SWCLK_49") (pintype "bidirectional"))
    )
    (net (code "188") (name "/SWDIO") (class "Default")
      (node (ref "P4") (pin "1") (pinfunction "1_1") (pintype "passive"))
      (node (ref "R1") (pin "1") (pinfunction "1_1") (pintype "passive"))
      (node (ref "U3") (pin "46") (pinfunction "PA13/JTMS/SWDIO_46") (pintype "bidirectional"))
    )
    (net (code "189") (name "/TCK") (class "Default")
      (node (ref "P12") (pin "1") (pinfunction "1_1") (pintype "passive"))
      (node (ref "R34") (pin "2") (pinfunction "2_2") (pintype "passive"))
      (node (ref "U1") (pin "159") (pinfunction "TCK_159") (pintype "input"))
      (node (ref "U14") (pin "16") (pinfunction "ADBUS0_16") (pintype "bidirectional"))
    )
    (net (code "190") (name "/TDI") (class "Default")
      (node (ref "P12") (pin "9") (pinfunction "9_9") (pintype "passive"))
      (node (ref "U11") (pin "4") (pinfunction "TDI_4") (pintype "input"))
      (node (ref "U14") (pin "17") (pinfunction "ADBUS1_17") (pintype "bidirectional"))
    )
    (net (code "191") (name "/TDO") (class "Default")
      (node (ref "P12") (pin "3") (pinfunction "3_3") (pintype "passive"))
      (node (ref "U1") (pin "158") (pinfunction "TDO_158") (pintype "output"))
      (node (ref "U14") (pin "18") (pinfunction "ADBUS2_18") (pintype "bidirectional"))
    )
    (net (code "192") (name "/TMS") (class "Default")
      (node (ref "P12") (pin "5") (pinfunction "5_5") (pintype "passive"))
      (node (ref "R35") (pin "2") (pinfunction "2_2") (pintype "passive"))
      (node (ref "U1") (pin "160") (pinfunction "TMS_160") (pintype "input"))
      (node (ref "U14") (pin "19") (pinfunction "ADBUS3_19") (pintype "bidirectional"))
    )
    (net (code "193") (name "/TXD0(PA10)") (class "Default")
      (node (ref "U10") (pin "5") (pinfunction "RXD_5") (pintype "passive"))
      (node (ref "U3") (pin "43") (pinfunction "PA10_43") (pintype "bidirectional"))
    )
    (net (code "194") (name "/TXD_FT2232{slash}MPSSE_TCK") (class "Default")
      (node (ref "U1") (pin "149") (pinfunction "IO_L20N_2_149") (pintype "bidirectional"))
      (node (ref "U14") (pin "38") (pinfunction "BDBUS0_38") (pintype "bidirectional"))
    )
    (net (code "195") (name "/TX_232") (class "Default")
      (node (ref "U1") (pin "9") (pinfunction "IO_L19N_7/VREF_7_9") (pintype "bidirectional"))
      (node (ref "U17") (pin "11") (pinfunction "T1IN_11") (pintype "input"))
    )
    (net (code "196") (name "/UB") (class "Default")
      (node (ref "U1") (pin "190") (pinfunction "IO_L30P_0_190") (pintype "bidirectional"))
      (node (ref "U13") (pin "40") (pinfunction "~{UB}_40") (pintype "passive"))
    )
    (net (code "197") (name "/UTOF") (class "Default")
      (node (ref "U1") (pin "102") (pinfunction "IO/VREF_4_102") (pintype "bidirectional"))
      (node (ref "U3") (pin "62") (pinfunction "PB9_62") (pintype "bidirectional"))
    )
    (net (code "198") (name "/VSYNC") (class "Default")
      (node (ref "R38") (pin "2") (pinfunction "2_2") (pintype "passive"))
      (node (ref "U1") (pin "58") (pinfunction "IO_L01N_5/RDWR_B_58") (pintype "bidirectional"))
    )
    (net (code "199") (name "/WE") (class "Default")
      (node (ref "U1") (pin "162") (pinfunction "IO_L01N_1/VRP_1_162") (pintype "bidirectional"))
      (node (ref "U13") (pin "17") (pinfunction "~{WE}_17") (pintype "passive"))
    )
    (net (code "200") (name "1.2V") (class "Default")
      (node (ref "C20") (pin "2") (pinfunction "2_2") (pintype "passive"))
      (node (ref "C21") (pin "2") (pinfunction "2_2") (pintype "passive"))
      (node (ref "C22") (pin "2") (pinfunction "2_2") (pintype "passive"))
      (node (ref "C23") (pin "2") (pinfunction "2_2") (pintype "passive"))
      (node (ref "C53") (pin "1") (pinfunction "1_1") (pintype "passive"))
      (node (ref "C55") (pin "2") (pinfunction "2_2") (pintype "passive"))
      (node (ref "R32") (pin "2") (pinfunction "2_2") (pintype "passive"))
      (node (ref "R36") (pin "2") (pinfunction "2_2") (pintype "passive"))
      (node (ref "U1") (pin "174") (pinfunction "VCCINT_174") (pintype "power_in"))
      (node (ref "U1") (pin "192") (pinfunction "VCCINT_192") (pintype "power_in"))
      (node (ref "U1") (pin "70") (pinfunction "VCCINT_70") (pintype "power_in"))
      (node (ref "U1") (pin "88") (pinfunction "VCCINT_88") (pintype "power_in"))
      (node (ref "U12") (pin "2") (pinfunction "OUT_2") (pintype "passive"))
    )
    (net (code "201") (name "1.8V") (class "Default")
      (node (ref "C60") (pin "2") (pinfunction "2_2") (pintype "passive"))
      (node (ref "C61") (pin "2") (pinfunction "2_2") (pintype "passive"))
      (node (ref "U14") (pin "12") (pinfunction "VCORE_12") (pintype "power_in"))
      (node (ref "U14") (pin "37") (pinfunction "VCORE_37") (pintype "power_in"))
      (node (ref "U14") (pin "49") (pinfunction "VREGOUT_49") (pintype "power_in"))
      (node (ref "U14") (pin "64") (pinfunction "VCORE_64") (pintype "power_in"))
    )
    (net (code "202") (name "2.5V") (class "Default")
      (node (ref "C10") (pin "2") (pinfunction "2_2") (pintype "passive"))
      (node (ref "C11") (pin "2") (pinfunction "2_2") (pintype "passive"))
      (node (ref "C12") (pin "2") (pinfunction "2_2") (pintype "passive"))
      (node (ref "C13") (pin "2") (pinfunction "2_2") (pintype "passive"))
      (node (ref "C14") (pin "2") (pinfunction "2_2") (pintype "passive"))
      (node (ref "C15") (pin "2") (pinfunction "2_2") (pintype "passive"))
      (node (ref "C16") (pin "2") (pinfunction "2_2") (pintype "passive"))
      (node (ref "C46") (pin "1") (pinfunction "1_1") (pintype "passive"))
      (node (ref "C49") (pin "2") (pinfunction "2_2") (pintype "passive"))
      (node (ref "C9") (pin "2") (pinfunction "2_2") (pintype "passive"))
      (node (ref "P11") (pin "26") (pinfunction "26_26") (pintype "passive"))
      (node (ref "R23") (pin "2") (pinfunction "2_2") (pintype "passive"))
      (node (ref "R26") (pin "2") (pinfunction "2_2") (pintype "passive"))
      (node (ref "R27") (pin "2") (pinfunction "2_2") (pintype "passive"))
      (node (ref "R28") (pin "2") (pinfunction "2_2") (pintype "passive"))
      (node (ref "U1") (pin "121") (pinfunction "VCCAUX_121") (pintype "power_in"))
      (node (ref "U1") (pin "142") (pinfunction "VCCAUX_142") (pintype "power_in"))
      (node (ref "U1") (pin "17") (pinfunction "VCCAUX_17") (pintype "power_in"))
      (node (ref "U1") (pin "173") (pinfunction "VCCAUX_173") (pintype "power_in"))
      (node (ref "U1") (pin "193") (pinfunction "VCCAUX_193") (pintype "power_in"))
      (node (ref "U1") (pin "38") (pinfunction "VCCAUX_38") (pintype "power_in"))
      (node (ref "U1") (pin "69") (pinfunction "VCCAUX_69") (pintype "power_in"))
      (node (ref "U1") (pin "89") (pinfunction "VCCAUX_89") (pintype "power_in"))
      (node (ref "U8") (pin "2") (pinfunction "OUT_2") (pintype "passive"))
    )
    (net (code "203") (name "3.3V") (class "Default")
      (node (ref "C1") (pin "2") (pinfunction "2_2") (pintype "passive"))
      (node (ref "C17") (pin "2") (pinfunction "2_2") (pintype "passive"))
      (node (ref "C18") (pin "2") (pinfunction "2_2") (pintype "passive"))
      (node (ref "C2") (pin "2") (pinfunction "2_2") (pintype "passive"))
      (node (ref "C25") (pin "2") (pinfunction "2_2") (pintype "passive"))
      (node (ref "C26") (pin "2") (pinfunction "2_2") (pintype "passive"))
      (node (ref "C27") (pin "2") (pinfunction "2_2") (pintype "passive"))
      (node (ref "C28") (pin "2") (pinfunction "2_2") (pintype "passive"))
      (node (ref "C29") (pin "2") (pinfunction "2_2") (pintype "passive"))
      (node (ref "C3") (pin "2") (pinfunction "2_2") (pintype "passive"))
      (node (ref "C30") (pin "2") (pinfunction "2_2") (pintype "passive"))
      (node (ref "C31") (pin "2") (pinfunction "2_2") (pintype "passive"))
      (node (ref "C32") (pin "2") (pinfunction "2_2") (pintype "passive"))
      (node (ref "C37") (pin "2") (pinfunction "2_2") (pintype "passive"))
      (node (ref "C38") (pin "2") (pinfunction "2_2") (pintype "passive"))
      (node (ref "C39") (pin "2") (pinfunction "2_2") (pintype "passive"))
      (node (ref "C4") (pin "2") (pinfunction "2_2") (pintype "passive"))
      (node (ref "C40") (pin "2") (pinfunction "2_2") (pintype "passive"))
      (node (ref "C43") (pin "1") (pinfunction "1_1") (pintype "passive"))
      (node (ref "C45") (pin "2") (pinfunction "2_2") (pintype "passive"))
      (node (ref "C47") (pin "2") (pinfunction "2_2") (pintype "passive"))
      (node (ref "C48") (pin "2") (pinfunction "2_2") (pintype "passive"))
      (node (ref "C5") (pin "2") (pinfunction "2_2") (pintype "passive"))
      (node (ref "C50") (pin "2") (pinfunction "2_2") (pintype "passive"))
      (node (ref "C56") (pin "2") (pinfunction "2_2") (pintype "passive"))
      (node (ref "C57") (pin "2") (pinfunction "2_2") (pintype "passive"))
      (node (ref "C58") (pin "1") (pinfunction "1_1") (pintype "passive"))
      (node (ref "C59") (pin "1") (pinfunction "1_1") (pintype "passive"))
      (node (ref "C6") (pin "2") (pinfunction "2_2") (pintype "passive"))
      (node (ref "C66") (pin "1") (pinfunction "1_1") (pintype "passive"))
      (node (ref "C67") (pin "1") (pinfunction "1_1") (pintype "passive"))
      (node (ref "C68") (pin "1") (pinfunction "1_1") (pintype "passive"))
      (node (ref "C69") (pin "1") (pinfunction "1_1") (pintype "passive"))
      (node (ref "C7") (pin "2") (pinfunction "2_2") (pintype "passive"))
      (node (ref "C74") (pin "2") (pinfunction "2_2") (pintype "passive"))
      (node (ref "C76") (pin "2") (pinfunction "2_2") (pintype "passive"))
      (node (ref "C8") (pin "2") (pinfunction "2_2") (pintype "passive"))
      (node (ref "L1") (pin "1") (pinfunction "1_1") (pintype "passive"))
      (node (ref "L4") (pin "1") (pinfunction "1_1") (pintype "passive"))
      (node (ref "L5") (pin "1") (pinfunction "1_1") (pintype "passive"))
      (node (ref "OSC1") (pin "4") (pinfunction "VCC_4") (pintype "passive"))
      (node (ref "P11") (pin "25") (pinfunction "25_25") (pintype "passive"))
      (node (ref "P12") (pin "4") (pinfunction "4_4") (pintype "passive"))
      (node (ref "P4") (pin "4") (pinfunction "4_4") (pintype "passive"))
      (node (ref "P9") (pin "17") (pinfunction "17_17") (pintype "passive"))
      (node (ref "R1") (pin "2") (pinfunction "2_2") (pintype "passive"))
      (node (ref "R14") (pin "2") (pinfunction "2_2") (pintype "passive"))
      (node (ref "R2") (pin "2") (pinfunction "2_2") (pintype "passive"))
      (node (ref "R24") (pin "1") (pinfunction "1_1") (pintype "passive"))
      (node (ref "R25") (pin "1") (pinfunction "1_1") (pintype "passive"))
      (node (ref "R48") (pin "1") (pinfunction "1_1") (pintype "passive"))
      (node (ref "R56") (pin "2") (pinfunction "2_2") (pintype "passive"))
      (node (ref "R8") (pin "2") (pinfunction "2_2") (pintype "passive"))
      (node (ref "S1") (pin "10") (pinfunction "B7_10") (pintype "passive"))
      (node (ref "S1") (pin "11") (pinfunction "B6_11") (pintype "passive"))
      (node (ref "S1") (pin "12") (pinfunction "B5_12") (pintype "passive"))
      (node (ref "S1") (pin "13") (pinfunction "B4_13") (pintype "passive"))
      (node (ref "S1") (pin "14") (pinfunction "B3_14") (pintype "passive"))
      (node (ref "S1") (pin "15") (pinfunction "B2_15") (pintype "passive"))
      (node (ref "S1") (pin "16") (pinfunction "B1_16") (pintype "passive"))
      (node (ref "S1") (pin "9") (pinfunction "B8_9") (pintype "passive"))
      (node (ref "S4") (pin "1") (pinfunction "COMMON_1") (pintype "passive"))
      (node (ref "S6") (pin "2") (pinfunction "2_2") (pintype "passive"))
      (node (ref "S7") (pin "2") (pinfunction "2_2") (pintype "passive"))
      (node (ref "S8") (pin "2") (pinfunction "2_2") (pintype "passive"))
      (node (ref "S9") (pin "2") (pinfunction "2_2") (pintype "passive"))
      (node (ref "U1") (pin "110") (pinfunction "VCCO_3_110") (pintype "power_in"))
      (node (ref "U1") (pin "127") (pinfunction "VCCO_3_127") (pintype "power_in"))
      (node (ref "U1") (pin "136") (pinfunction "VCCO_2_136") (pintype "power_in"))
      (node (ref "U1") (pin "153") (pinfunction "VCCO_2_153") (pintype "power_in"))
      (node (ref "U1") (pin "164") (pinfunction "VCCO_1_164") (pintype "power_in"))
      (node (ref "U1") (pin "177") (pinfunction "VCCO_1_177") (pintype "power_in"))
      (node (ref "U1") (pin "188") (pinfunction "VCCO_0_188") (pintype "power_in"))
      (node (ref "U1") (pin "201") (pinfunction "VCCO_0_201") (pintype "power_in"))
      (node (ref "U1") (pin "23") (pinfunction "VCCO_7_23") (pintype "power_in"))
      (node (ref "U1") (pin "32") (pinfunction "VCCO_6_32") (pintype "power_in"))
      (node (ref "U1") (pin "49") (pinfunction "VCCO_6_49") (pintype "power_in"))
      (node (ref "U1") (pin "6") (pinfunction "VCCO_7_6") (pintype "power_in"))
      (node (ref "U1") (pin "60") (pinfunction "VCCO_5_60") (pintype "power_in"))
      (node (ref "U1") (pin "73") (pinfunction "VCCO_5_73") (pintype "power_in"))
      (node (ref "U1") (pin "84") (pinfunction "VCCO_4_84") (pintype "power_in"))
      (node (ref "U1") (pin "98") (pinfunction "VCCO_4_98") (pintype "power_in"))
      (node (ref "U11") (pin "18") (pinfunction "VCCINT_18") (pintype "power_in"))
      (node (ref "U11") (pin "19") (pinfunction "VCCO_19") (pintype "power_in"))
      (node (ref "U11") (pin "20") (pinfunction "VCCJ_20") (pintype "power_in"))
      (node (ref "U13") (pin "11") (pinfunction "VDD_11") (pintype "passive"))
      (node (ref "U13") (pin "33") (pinfunction "VDD_33") (pintype "passive"))
      (node (ref "U14") (pin "20") (pinfunction "VCCIO_20") (pintype "power_in"))
      (node (ref "U14") (pin "31") (pinfunction "VCCIO_31") (pintype "power_in"))
      (node (ref "U14") (pin "42") (pinfunction "VCCIO_42") (pintype "power_in"))
      (node (ref "U14") (pin "50") (pinfunction "VREGIN_50") (pintype "power_in"))
      (node (ref "U14") (pin "56") (pinfunction "VCCIO_56") (pintype "power_in"))
      (node (ref "U17") (pin "16") (pinfunction "VCC_16") (pintype "power_in"))
      (node (ref "U3") (pin "1") (pinfunction "VBAT_1") (pintype "power_in"))
      (node (ref "U3") (pin "19") (pinfunction "VDD_4_19") (pintype "power_in"))
      (node (ref "U3") (pin "32") (pinfunction "VDD_1_32") (pintype "power_in"))
      (node (ref "U3") (pin "48") (pinfunction "VDD_2_48") (pintype "power_in"))
      (node (ref "U3") (pin "64") (pinfunction "VDD_3_64") (pintype "power_in"))
      (node (ref "U5") (pin "2") (pinfunction "OUT_2") (pintype "passive"))
      (node (ref "U8") (pin "3") (pinfunction "IN_3") (pintype "passive"))
      (node (ref "U9") (pin "8") (pinfunction "VCC_8") (pintype "passive"))
    )
    (net (code "204") (name "3.3VA") (class "Default")
      (node (ref "C34") (pin "2") (pinfunction "2_2") (pintype "passive"))
      (node (ref "L1") (pin "2") (pinfunction "2_2") (pintype "passive"))
      (node (ref "U3") (pin "13") (pinfunction "VDDA_13") (pintype "power_in"))
    )
    (net (code "205") (name "5V") (class "Default")
      (node (ref "C19") (pin "2") (pinfunction "2_2") (pintype "passive"))
      (node (ref "C36") (pin "2") (pinfunction "2_2") (pintype "passive"))
      (node (ref "C42") (pin "2") (pinfunction "2_2") (pintype "passive"))
      (node (ref "C44") (pin "2") (pinfunction "2_2") (pintype "passive"))
      (node (ref "C51") (pin "2") (pinfunction "2_2") (pintype "passive"))
      (node (ref "C54") (pin "2") (pinfunction "2_2") (pintype "passive"))
      (node (ref "C70") (pin "1") (pinfunction "1_1") (pintype "passive"))
      (node (ref "K1") (pin "4") (pinfunction "T1_4") (pintype "passive"))
      (node (ref "K2") (pin "4") (pinfunction "T1_4") (pintype "passive"))
      (node (ref "L3") (pin "2") (pinfunction "2_2") (pintype "passive"))
      (node (ref "L6") (pin "2") (pinfunction "2_2") (pintype "passive"))
      (node (ref "LCD1") (pin "15") (pinfunction "A_15") (pintype "passive"))
      (node (ref "LCD1") (pin "2") (pinfunction "VCC_2") (pintype "passive"))
      (node (ref "P1") (pin "5") (pinfunction "5_5") (pintype "passive"))
      (node (ref "P11") (pin "27") (pinfunction "27_27") (pintype "passive"))
      (node (ref "R29") (pin "2") (pinfunction "2_2") (pintype "passive"))
      (node (ref "R30") (pin "2") (pinfunction "2_2") (pintype "passive"))
      (node (ref "R4") (pin "2") (pinfunction "2_2") (pintype "passive"))
      (node (ref "R5") (pin "2") (pinfunction "2_2") (pintype "passive"))
      (node (ref "R59") (pin "1") (pinfunction "1_1") (pintype "passive"))
      (node (ref "R6") (pin "1") (pinfunction "TOP_1") (pintype "passive"))
      (node (ref "R7") (pin "2") (pinfunction "2_2") (pintype "passive"))
      (node (ref "U10") (pin "20") (pinfunction "VCC_20") (pintype "passive"))
      (node (ref "U10") (pin "4") (pinfunction "VCCIO_4") (pintype "passive"))
      (node (ref "U12") (pin "3") (pinfunction "IN_3") (pintype "passive"))
      (node (ref "U15") (pin "20") (pinfunction "VCC_20") (pintype "power_in"))
      (node (ref "U16") (pin "8") (pinfunction "VCC_8") (pintype "power_in"))
      (node (ref "U2") (pin "10") (pinfunction "COM_D_10") (pintype "passive"))
      (node (ref "U4") (pin "4") (pinfunction "FB_4") (pintype "input"))
      (node (ref "U5") (pin "3") (pinfunction "IN_3") (pintype "passive"))
      (node (ref "U6") (pin "20") (pinfunction "VCC_20") (pintype "power_in"))
      (node (ref "USB1") (pin "1") (pinfunction "VCC_1") (pintype "passive"))
    )
    (net (code "206") (name "GND") (class "Default")
      (node (ref "C1") (pin "1") (pinfunction "1_1") (pintype "passive"))
      (node (ref "C10") (pin "1") (pinfunction "1_1") (pintype "passive"))
      (node (ref "C11") (pin "1") (pinfunction "1_1") (pintype "passive"))
      (node (ref "C12") (pin "1") (pinfunction "1_1") (pintype "passive"))
      (node (ref "C13") (pin "1") (pinfunction "1_1") (pintype "passive"))
      (node (ref "C14") (pin "1") (pinfunction "1_1") (pintype "passive"))
      (node (ref "C15") (pin "1") (pinfunction "1_1") (pintype "passive"))
      (node (ref "C16") (pin "1") (pinfunction "1_1") (pintype "passive"))
      (node (ref "C17") (pin "1") (pinfunction "1_1") (pintype "passive"))
      (node (ref "C18") (pin "1") (pinfunction "1_1") (pintype "passive"))
      (node (ref "C19") (pin "1") (pinfunction "1_1") (pintype "passive"))
      (node (ref "C2") (pin "1") (pinfunction "1_1") (pintype "passive"))
      (node (ref "C20") (pin "1") (pinfunction "1_1") (pintype "passive"))
      (node (ref "C21") (pin "1") (pinfunction "1_1") (pintype "passive"))
      (node (ref "C22") (pin "1") (pinfunction "1_1") (pintype "passive"))
      (node (ref "C23") (pin "1") (pinfunction "1_1") (pintype "passive"))
      (node (ref "C24") (pin "1") (pinfunction "1_1") (pintype "passive"))
      (node (ref "C25") (pin "1") (pinfunction "1_1") (pintype "passive"))
      (node (ref "C26") (pin "1") (pinfunction "1_1") (pintype "passive"))
      (node (ref "C27") (pin "1") (pinfunction "1_1") (pintype "passive"))
      (node (ref "C28") (pin "1") (pinfunction "1_1") (pintype "passive"))
      (node (ref "C29") (pin "1") (pinfunction "1_1") (pintype "passive"))
      (node (ref "C3") (pin "1") (pinfunction "1_1") (pintype "passive"))
      (node (ref "C30") (pin "1") (pinfunction "1_1") (pintype "passive"))
      (node (ref "C31") (pin "1") (pinfunction "1_1") (pintype "passive"))
      (node (ref "C32") (pin "1") (pinfunction "1_1") (pintype "passive"))
      (node (ref "C33") (pin "1") (pinfunction "1_1") (pintype "passive"))
      (node (ref "C35") (pin "1") (pinfunction "1_1") (pintype "passive"))
      (node (ref "C36") (pin "1") (pinfunction "1_1") (pintype "passive"))
      (node (ref "C37") (pin "1") (pinfunction "1_1") (pintype "passive"))
      (node (ref "C38") (pin "1") (pinfunction "1_1") (pintype "passive"))
      (node (ref "C39") (pin "1") (pinfunction "1_1") (pintype "passive"))
      (node (ref "C4") (pin "1") (pinfunction "1_1") (pintype "passive"))
      (node (ref "C40") (pin "1") (pinfunction "1_1") (pintype "passive"))
      (node (ref "C41") (pin "1") (pinfunction "1_1") (pintype "passive"))
      (node (ref "C42") (pin "1") (pinfunction "1_1") (pintype "passive"))
      (node (ref "C43") (pin "2") (pinfunction "2_2") (pintype "passive"))
      (node (ref "C44") (pin "1") (pinfunction "1_1") (pintype "passive"))
      (node (ref "C45") (pin "1") (pinfunction "1_1") (pintype "passive"))
      (node (ref "C46") (pin "2") (pinfunction "2_2") (pintype "passive"))
      (node (ref "C47") (pin "1") (pinfunction "1_1") (pintype "passive"))
      (node (ref "C48") (pin "1") (pinfunction "1_1") (pintype "passive"))
      (node (ref "C49") (pin "1") (pinfunction "1_1") (pintype "passive"))
      (node (ref "C5") (pin "1") (pinfunction "1_1") (pintype "passive"))
      (node (ref "C50") (pin "1") (pinfunction "1_1") (pintype "passive"))
      (node (ref "C51") (pin "1") (pinfunction "1_1") (pintype "passive"))
      (node (ref "C52") (pin "1") (pinfunction "1_1") (pintype "passive"))
      (node (ref "C53") (pin "2") (pinfunction "2_2") (pintype "passive"))
      (node (ref "C54") (pin "1") (pinfunction "1_1") (pintype "passive"))
      (node (ref "C55") (pin "1") (pinfunction "1_1") (pintype "passive"))
      (node (ref "C56") (pin "1") (pinfunction "1_1") (pintype "passive"))
      (node (ref "C57") (pin "1") (pinfunction "1_1") (pintype "passive"))
      (node (ref "C58") (pin "2") (pinfunction "2_2") (pintype "passive"))
      (node (ref "C59") (pin "2") (pinfunction "2_2") (pintype "passive"))
      (node (ref "C6") (pin "1") (pinfunction "1_1") (pintype "passive"))
      (node (ref "C60") (pin "1") (pinfunction "1_1") (pintype "passive"))
      (node (ref "C61") (pin "1") (pinfunction "1_1") (pintype "passive"))
      (node (ref "C62") (pin "1") (pinfunction "1_1") (pintype "passive"))
      (node (ref "C63") (pin "1") (pinfunction "1_1") (pintype "passive"))
      (node (ref "C64") (pin "1") (pinfunction "1_1") (pintype "passive"))
      (node (ref "C65") (pin "1") (pinfunction "1_1") (pintype "passive"))
      (node (ref "C7") (pin "1") (pinfunction "1_1") (pintype "passive"))
      (node (ref "C70") (pin "2") (pinfunction "2_2") (pintype "passive"))
      (node (ref "C72") (pin "1") (pinfunction "1_1") (pintype "passive"))
      (node (ref "C74") (pin "1") (pinfunction "1_1") (pintype "passive"))
      (node (ref "C75") (pin "1") (pinfunction "1_1") (pintype "passive"))
      (node (ref "C76") (pin "1") (pinfunction "1_1") (pintype "passive"))
      (node (ref "C77") (pin "1") (pinfunction "1_1") (pintype "passive"))
      (node (ref "C78") (pin "1") (pinfunction "1_1") (pintype "passive"))
      (node (ref "C8") (pin "1") (pinfunction "1_1") (pintype "passive"))
      (node (ref "C9") (pin "1") (pinfunction "1_1") (pintype "passive"))
      (node (ref "D11") (pin "2") (pinfunction "K_2") (pintype "passive"))
      (node (ref "D4") (pin "2") (pinfunction "K_2") (pintype "passive"))
      (node (ref "D5") (pin "1") (pinfunction "A_1") (pintype "passive"))
      (node (ref "D6") (pin "2") (pinfunction "K_2") (pintype "passive"))
      (node (ref "D7") (pin "2") (pinfunction "K_2") (pintype "passive"))
      (node (ref "D8") (pin "2") (pinfunction "K_2") (pintype "passive"))
      (node (ref "J1") (pin "10") (pinfunction "10_10") (pintype "passive"))
      (node (ref "J1") (pin "11") (pinfunction "11_11") (pintype "passive"))
      (node (ref "J1") (pin "5") (pinfunction "5_5") (pintype "passive"))
      (node (ref "J1") (pin "6") (pinfunction "6_6") (pintype "passive"))
      (node (ref "J1") (pin "7") (pinfunction "7_7") (pintype "passive"))
      (node (ref "J1") (pin "8") (pinfunction "8_8") (pintype "passive"))
      (node (ref "L2") (pin "1") (pinfunction "1_1") (pintype "passive"))
      (node (ref "LCD1") (pin "1") (pinfunction "GND_1") (pintype "passive"))
      (node (ref "LCD1") (pin "16") (pinfunction "K_16") (pintype "passive"))
      (node (ref "LS1") (pin "1") (pinfunction "1_1") (pintype "passive"))
      (node (ref "OSC1") (pin "2") (pinfunction "GND_2") (pintype "passive"))
      (node (ref "P10") (pin "9") (pinfunction "9_9") (pintype "passive"))
      (node (ref "P11") (pin "28") (pinfunction "28_28") (pintype "passive"))
      (node (ref "P12") (pin "10") (pinfunction "10_10") (pintype "passive"))
      (node (ref "P12") (pin "2") (pinfunction "2_2") (pintype "passive"))
      (node (ref "P13") (pin "9") (pinfunction "9_9") (pintype "passive"))
      (node (ref "P14") (pin "9") (pinfunction "9_9") (pintype "passive"))
      (node (ref "P3") (pin "9") (pinfunction "9_9") (pintype "passive"))
      (node (ref "P4") (pin "5") (pinfunction "5_5") (pintype "passive"))
      (node (ref "P6") (pin "1") (pinfunction "1_1") (pintype "passive"))
      (node (ref "P7") (pin "9") (pinfunction "9_9") (pintype "passive"))
      (node (ref "P8") (pin "1") (pinfunction "1_1") (pintype "passive"))
      (node (ref "P9") (pin "18") (pinfunction "18_18") (pintype "passive"))
      (node (ref "Q1") (pin "1") (pinfunction "B_1") (pintype "passive"))
      (node (ref "Q2") (pin "1") (pinfunction "B_1") (pintype "passive"))
      (node (ref "Q3") (pin "1") (pinfunction "B_1") (pintype "passive"))
      (node (ref "Q4") (pin "1") (pinfunction "B_1") (pintype "passive"))
      (node (ref "R15") (pin "2") (pinfunction "2_2") (pintype "passive"))
      (node (ref "R16") (pin "2") (pinfunction "2_2") (pintype "passive"))
      (node (ref "R21") (pin "2") (pinfunction "2_2") (pintype "passive"))
      (node (ref "R22") (pin "2") (pinfunction "2_2") (pintype "passive"))
      (node (ref "R3") (pin "1") (pinfunction "1_1") (pintype "passive"))
      (node (ref "R36") (pin "1") (pinfunction "1_1") (pintype "passive"))
      (node (ref "R39") (pin "1") (pinfunction "1_1") (pintype "passive"))
      (node (ref "R40") (pin "1") (pinfunction "1_1") (pintype "passive"))
      (node (ref "R41") (pin "1") (pinfunction "1_1") (pintype "passive"))
      (node (ref "R42") (pin "1") (pinfunction "1_1") (pintype "passive"))
      (node (ref "R51") (pin "1") (pinfunction "1_1") (pintype "passive"))
      (node (ref "R6") (pin "2") (pinfunction "BOT_2") (pintype "passive"))
      (node (ref "R9") (pin "1") (pinfunction "1_1") (pintype "passive"))
      (node (ref "S3") (pin "1") (pinfunction "1_1") (pintype "passive"))
      (node (ref "S5") (pin "2") (pinfunction "2_2") (pintype "passive"))
      (node (ref "U1") (pin "1") (pinfunction "GND_1") (pintype "power_in"))
      (node (ref "U1") (pin "105") (pinfunction "GND_105") (pintype "power_in"))
      (node (ref "U1") (pin "112") (pinfunction "GND_112") (pintype "power_in"))
      (node (ref "U1") (pin "118") (pinfunction "GND_118") (pintype "power_in"))
      (node (ref "U1") (pin "129") (pinfunction "GND_129") (pintype "power_in"))
      (node (ref "U1") (pin "134") (pinfunction "GND_134") (pintype "power_in"))
      (node (ref "U1") (pin "14") (pinfunction "GND_14") (pintype "power_in"))
      (node (ref "U1") (pin "145") (pinfunction "GND_145") (pintype "power_in"))
      (node (ref "U1") (pin "151") (pinfunction "GND_151") (pintype "power_in"))
      (node (ref "U1") (pin "157") (pinfunction "GND_157") (pintype "power_in"))
      (node (ref "U1") (pin "163") (pinfunction "GND_163") (pintype "power_in"))
      (node (ref "U1") (pin "170") (pinfunction "GND_170") (pintype "power_in"))
      (node (ref "U1") (pin "179") (pinfunction "GND_179") (pintype "power_in"))
      (node (ref "U1") (pin "186") (pinfunction "GND_186") (pintype "power_in"))
      (node (ref "U1") (pin "195") (pinfunction "GND_195") (pintype "power_in"))
      (node (ref "U1") (pin "202") (pinfunction "GND_202") (pintype "power_in"))
      (node (ref "U1") (pin "206") (pinfunction "HSWAP_EN_206") (pintype "input"))
      (node (ref "U1") (pin "25") (pinfunction "GND_25") (pintype "power_in"))
      (node (ref "U1") (pin "30") (pinfunction "GND_30") (pintype "power_in"))
      (node (ref "U1") (pin "41") (pinfunction "GND_41") (pintype "power_in"))
      (node (ref "U1") (pin "47") (pinfunction "GND_47") (pintype "power_in"))
      (node (ref "U1") (pin "53") (pinfunction "GND_53") (pintype "power_in"))
      (node (ref "U1") (pin "54") (pinfunction "M1_54") (pintype "input"))
      (node (ref "U1") (pin "55") (pinfunction "M0_55") (pintype "input"))
      (node (ref "U1") (pin "56") (pinfunction "M2_56") (pintype "input"))
      (node (ref "U1") (pin "59") (pinfunction "GND_59") (pintype "power_in"))
      (node (ref "U1") (pin "66") (pinfunction "GND_66") (pintype "power_in"))
      (node (ref "U1") (pin "75") (pinfunction "GND_75") (pintype "power_in"))
      (node (ref "U1") (pin "8") (pinfunction "GND_8") (pintype "power_in"))
      (node (ref "U1") (pin "82") (pinfunction "GND_82") (pintype "power_in"))
      (node (ref "U1") (pin "91") (pinfunction "GND_91") (pintype "power_in"))
      (node (ref "U1") (pin "99") (pinfunction "GND_99") (pintype "power_in"))
      (node (ref "U10") (pin "18") (pinfunction "GND_18") (pintype "passive"))
      (node (ref "U10") (pin "21") (pinfunction "GND_21") (pintype "passive"))
      (node (ref "U10") (pin "25") (pinfunction "AGND_25") (pintype "passive"))
      (node (ref "U10") (pin "26") (pinfunction "TEST_26") (pintype "passive"))
      (node (ref "U10") (pin "7") (pinfunction "GND_7") (pintype "passive"))
      (node (ref "U11") (pin "11") (pinfunction "GND_11") (pintype "power_in"))
      (node (ref "U12") (pin "1") (pinfunction "GND_1") (pintype "passive"))
      (node (ref "U13") (pin "12") (pinfunction "GND_12") (pintype "passive"))
      (node (ref "U13") (pin "34") (pinfunction "GND_34") (pintype "passive"))
      (node (ref "U14") (pin "1") (pinfunction "GND_1") (pintype "power_in"))
      (node (ref "U14") (pin "10") (pinfunction "AGND_10") (pintype "power_in"))
      (node (ref "U14") (pin "11") (pinfunction "GND_11") (pintype "power_in"))
      (node (ref "U14") (pin "13") (pinfunction "TEST_13") (pintype "input"))
      (node (ref "U14") (pin "15") (pinfunction "GND_15") (pintype "power_in"))
      (node (ref "U14") (pin "25") (pinfunction "GND_25") (pintype "power_in"))
      (node (ref "U14") (pin "35") (pinfunction "GND_35") (pintype "power_in"))
      (node (ref "U14") (pin "47") (pinfunction "GND_47") (pintype "power_in"))
      (node (ref "U14") (pin "5") (pinfunction "GND_5") (pintype "power_in"))
      (node (ref "U14") (pin "51") (pinfunction "GND_51") (pintype "power_in"))
      (node (ref "U15") (pin "1") (pinfunction "~{OE}1_1") (pintype "input"))
      (node (ref "U15") (pin "10") (pinfunction "GND_10") (pintype "power_in"))
      (node (ref "U15") (pin "19") (pinfunction "~{OE}2_19") (pintype "input"))
      (node (ref "U16") (pin "5") (pinfunction "VSS_5") (pintype "power_in"))
      (node (ref "U17") (pin "15") (pinfunction "GND_15") (pintype "power_in"))
      (node (ref "U2") (pin "9") (pinfunction "GND_9") (pintype "power_in"))
      (node (ref "U3") (pin "18") (pinfunction "VSS_4_18") (pintype "power_in"))
      (node (ref "U3") (pin "31") (pinfunction "VSS_1_31") (pintype "power_in"))
      (node (ref "U3") (pin "47") (pinfunction "VSS_2_47") (pintype "power_in"))
      (node (ref "U3") (pin "63") (pinfunction "VSS_3_63") (pintype "power_in"))
      (node (ref "U4") (pin "3") (pinfunction "GND_3") (pintype "power_in"))
      (node (ref "U4") (pin "5") (pinfunction "~{ON}/OFF_5") (pintype "input"))
      (node (ref "U5") (pin "1") (pinfunction "GND_1") (pintype "passive"))
      (node (ref "U6") (pin "1") (pinfunction "~{OE}1_1") (pintype "input"))
      (node (ref "U6") (pin "10") (pinfunction "GND_10") (pintype "power_in"))
      (node (ref "U6") (pin "19") (pinfunction "~{OE}2_19") (pintype "input"))
      (node (ref "U8") (pin "1") (pinfunction "GND_1") (pintype "passive"))
      (node (ref "U9") (pin "1") (pinfunction "A0_1") (pintype "passive"))
      (node (ref "U9") (pin "2") (pinfunction "A1_2") (pintype "passive"))
      (node (ref "U9") (pin "3") (pinfunction "NC_3") (pintype "passive"))
      (node (ref "U9") (pin "4") (pinfunction "GND_4") (pintype "passive"))
      (node (ref "U9") (pin "7") (pinfunction "WP_7") (pintype "passive"))
      (node (ref "USB1") (pin "5") (pinfunction "GND_5") (pintype "passive"))
      (node (ref "USB2") (pin "5") (pinfunction "GND_5") (pintype "passive"))
    )
    (net (code "207") (name "GNDA") (class "Default")
      (node (ref "C34") (pin "1") (pinfunction "1_1") (pintype "passive"))
      (node (ref "L2") (pin "2") (pinfunction "2_2") (pintype "passive"))
      (node (ref "U3") (pin "12") (pinfunction "VSSA_12") (pintype "power_in"))
    )
    (net (code "208") (name "Net-(D1-A)") (class "Default")
      (node (ref "D1") (pin "1") (pinfunction "A_1") (pintype "passive"))
      (node (ref "R4") (pin "1") (pinfunction "1_1") (pintype "passive"))
    )
    (net (code "209") (name "Net-(D1-K)") (class "Default")
      (node (ref "D1") (pin "2") (pinfunction "K_2") (pintype "passive"))
      (node (ref "K1") (pin "5") (pinfunction "T2_5") (pintype "passive"))
      (node (ref "U2") (pin "14") (pinfunction "OUT5_14") (pintype "open_collector"))
    )
    (net (code "210") (name "Net-(D2-A)") (class "Default")
      (node (ref "D2") (pin "1") (pinfunction "A_1") (pintype "passive"))
      (node (ref "R5") (pin "1") (pinfunction "1_1") (pintype "passive"))
    )
    (net (code "211") (name "Net-(D2-K)") (class "Default")
      (node (ref "D2") (pin "2") (pinfunction "K_2") (pintype "passive"))
      (node (ref "K2") (pin "5") (pinfunction "T2_5") (pintype "passive"))
      (node (ref "U2") (pin "13") (pinfunction "OUT6_13") (pintype "open_collector"))
    )
    (net (code "212") (name "Net-(D3-A)") (class "Default")
      (node (ref "D3") (pin "1") (pinfunction "A_1") (pintype "passive"))
      (node (ref "S2") (pin "2") (pinfunction "NO_2") (pintype "passive"))
    )
    (net (code "213") (name "Net-(D3-K)") (class "Default")
      (node (ref "C35") (pin "2") (pinfunction "2_2") (pintype "passive"))
      (node (ref "D3") (pin "2") (pinfunction "K_2") (pintype "passive"))
      (node (ref "U4") (pin "1") (pinfunction "VIN_1") (pintype "power_in"))
    )
    (net (code "214") (name "Net-(D4-A)") (class "Default")
      (node (ref "D4") (pin "1") (pinfunction "A_1") (pintype "passive"))
      (node (ref "R7") (pin "1") (pinfunction "1_1") (pintype "passive"))
    )
    (net (code "215") (name "Net-(D5-K)") (class "Default")
      (node (ref "D5") (pin "2") (pinfunction "K_2") (pintype "passive"))
      (node (ref "L3") (pin "1") (pinfunction "1_1") (pintype "passive"))
      (node (ref "U4") (pin "2") (pinfunction "OUT_2") (pintype "power_in"))
    )
    (net (code "216") (name "Net-(D6-A)") (class "Default")
      (node (ref "D6") (pin "1") (pinfunction "A_1") (pintype "passive"))
      (node (ref "R14") (pin "1") (pinfunction "1_1") (pintype "passive"))
    )
    (net (code "217") (name "Net-(D7-A)") (class "Default")
      (node (ref "D7") (pin "1") (pinfunction "A_1") (pintype "passive"))
      (node (ref "R23") (pin "1") (pinfunction "1_1") (pintype "passive"))
    )
    (net (code "218") (name "Net-(D8-A)") (class "Default")
      (node (ref "D8") (pin "1") (pinfunction "A_1") (pintype "passive"))
      (node (ref "R31") (pin "2") (pinfunction "2_2") (pintype "passive"))
    )
    (net (code "219") (name "Net-(D9-A)") (class "Default")
      (node (ref "D9") (pin "1") (pinfunction "A_1") (pintype "passive"))
      (node (ref "R29") (pin "1") (pinfunction "1_1") (pintype "passive"))
    )
    (net (code "220") (name "Net-(D9-K)") (class "Default")
      (node (ref "D9") (pin "2") (pinfunction "K_2") (pintype "passive"))
      (node (ref "U10") (pin "23") (pinfunction "CBUS0_23") (pintype "passive"))
    )
    (net (code "221") (name "Net-(D10-A)") (class "Default")
      (node (ref "D10") (pin "1") (pinfunction "A_1") (pintype "passive"))
      (node (ref "R30") (pin "1") (pinfunction "1_1") (pintype "passive"))
    )
    (net (code "222") (name "Net-(D10-K)") (class "Default")
      (node (ref "D10") (pin "2") (pinfunction "K_2") (pintype "passive"))
      (node (ref "U10") (pin "22") (pinfunction "CBUS1_22") (pintype "passive"))
    )
    (net (code "223") (name "Net-(D11-A)") (class "Default")
      (node (ref "D11") (pin "1") (pinfunction "A_1") (pintype "passive"))
      (node (ref "R32") (pin "1") (pinfunction "1_1") (pintype "passive"))
    )
    (net (code "224") (name "Net-(D12-K)") (class "Default")
      (node (ref "D12") (pin "2") (pinfunction "K_2") (pintype "passive"))
      (node (ref "P13") (pin "1") (pinfunction "1_1") (pintype "passive"))
    )
    (net (code "225") (name "Net-(D13-K)") (class "Default")
      (node (ref "D13") (pin "2") (pinfunction "K_2") (pintype "passive"))
      (node (ref "P13") (pin "2") (pinfunction "2_2") (pintype "passive"))
    )
    (net (code "226") (name "Net-(D14-K)") (class "Default")
      (node (ref "D14") (pin "2") (pinfunction "K_2") (pintype "passive"))
      (node (ref "P13") (pin "3") (pinfunction "3_3") (pintype "passive"))
    )
    (net (code "227") (name "Net-(D15-K)") (class "Default")
      (node (ref "D15") (pin "2") (pinfunction "K_2") (pintype "passive"))
      (node (ref "P13") (pin "4") (pinfunction "4_4") (pintype "passive"))
    )
    (net (code "228") (name "Net-(D16-K)") (class "Default")
      (node (ref "D16") (pin "2") (pinfunction "K_2") (pintype "passive"))
      (node (ref "P13") (pin "5") (pinfunction "5_5") (pintype "passive"))
    )
    (net (code "229") (name "Net-(D17-K)") (class "Default")
      (node (ref "D17") (pin "2") (pinfunction "K_2") (pintype "passive"))
      (node (ref "P13") (pin "6") (pinfunction "6_6") (pintype "passive"))
    )
    (net (code "230") (name "Net-(D18-K)") (class "Default")
      (node (ref "D18") (pin "2") (pinfunction "K_2") (pintype "passive"))
      (node (ref "P13") (pin "7") (pinfunction "7_7") (pintype "passive"))
    )
    (net (code "231") (name "Net-(D19-K)") (class "Default")
      (node (ref "D19") (pin "2") (pinfunction "K_2") (pintype "passive"))
      (node (ref "P13") (pin "8") (pinfunction "8_8") (pintype "passive"))
    )
    (net (code "232") (name "Net-(J1-Pad1)") (class "Default")
      (node (ref "J1") (pin "1") (pinfunction "1_1") (pintype "passive"))
      (node (ref "R55") (pin "1") (pinfunction "1_1") (pintype "passive"))
      (node (ref "R57") (pin "1") (pinfunction "1_1") (pintype "passive"))
      (node (ref "R58") (pin "1") (pinfunction "1_1") (pintype "passive"))
      (node (ref "R61") (pin "1") (pinfunction "1_1") (pintype "passive"))
    )
    (net (code "233") (name "Net-(J1-Pad2)") (class "Default")
      (node (ref "J1") (pin "2") (pinfunction "2_2") (pintype "passive"))
      (node (ref "R50") (pin "1") (pinfunction "1_1") (pintype "passive"))
      (node (ref "R52") (pin "1") (pinfunction "1_1") (pintype "passive"))
      (node (ref "R53") (pin "1") (pinfunction "1_1") (pintype "passive"))
      (node (ref "R54") (pin "1") (pinfunction "1_1") (pintype "passive"))
    )
    (net (code "234") (name "Net-(J1-Pad3)") (class "Default")
      (node (ref "J1") (pin "3") (pinfunction "3_3") (pintype "passive"))
      (node (ref "R44") (pin "1") (pinfunction "1_1") (pintype "passive"))
      (node (ref "R45") (pin "1") (pinfunction "1_1") (pintype "passive"))
      (node (ref "R47") (pin "1") (pinfunction "1_1") (pintype "passive"))
      (node (ref "R49") (pin "1") (pinfunction "1_1") (pintype "passive"))
    )
    (net (code "235") (name "Net-(J1-Pad13)") (class "Default")
      (node (ref "J1") (pin "13") (pinfunction "13_13") (pintype "passive"))
      (node (ref "R37") (pin "1") (pinfunction "1_1") (pintype "passive"))
    )
    (net (code "236") (name "Net-(J1-Pad15)") (class "Default")
      (node (ref "J1") (pin "15") (pinfunction "15_15") (pintype "passive"))
      (node (ref "R38") (pin "1") (pinfunction "1_1") (pintype "passive"))
    )
    (net (code "237") (name "Net-(K1-COM)") (class "Default")
      (node (ref "K1") (pin "1") (pinfunction "COM_1") (pintype "passive"))
      (node (ref "P2") (pin "2") (pinfunction "2_2") (pintype "passive"))
    )
    (net (code "238") (name "Net-(K1-NC)") (class "Default")
      (node (ref "K1") (pin "2") (pinfunction "NC_2") (pintype "passive"))
      (node (ref "P2") (pin "1") (pinfunction "1_1") (pintype "passive"))
    )
    (net (code "239") (name "Net-(K1-NO)") (class "Default")
      (node (ref "K1") (pin "3") (pinfunction "NO_3") (pintype "passive"))
      (node (ref "P2") (pin "3") (pinfunction "3_3") (pintype "passive"))
    )
    (net (code "240") (name "Net-(K2-COM)") (class "Default")
      (node (ref "K2") (pin "1") (pinfunction "COM_1") (pintype "passive"))
      (node (ref "P5") (pin "2") (pinfunction "2_2") (pintype "passive"))
    )
    (net (code "241") (name "Net-(K2-NC)") (class "Default")
      (node (ref "K2") (pin "2") (pinfunction "NC_2") (pintype "passive"))
      (node (ref "P5") (pin "1") (pinfunction "1_1") (pintype "passive"))
    )
    (net (code "242") (name "Net-(K2-NO)") (class "Default")
      (node (ref "K2") (pin "3") (pinfunction "NO_3") (pintype "passive"))
      (node (ref "P5") (pin "3") (pinfunction "3_3") (pintype "passive"))
    )
    (net (code "243") (name "Net-(LCD1-VO)") (class "Default")
      (node (ref "LCD1") (pin "3") (pinfunction "VO_3") (pintype "passive"))
      (node (ref "R6") (pin "3") (pinfunction "TAP_3") (pintype "passive"))
    )
    (net (code "244") (name "Net-(OSC1-E{slash}D)") (class "Default")
      (node (ref "OSC1") (pin "1") (pinfunction "E/D_1") (pintype "passive"))
      (node (ref "R56") (pin "1") (pinfunction "1_1") (pintype "passive"))
    )
    (net (code "245") (name "Net-(Q1-C)") (class "Default")
      (node (ref "Q1") (pin "3") (pinfunction "C_3") (pintype "passive"))
      (node (ref "R10") (pin "2") (pinfunction "2_2") (pintype "passive"))
    )
    (net (code "246") (name "Net-(Q1-E)") (class "Default")
      (node (ref "Q1") (pin "2") (pinfunction "E_2") (pintype "passive"))
      (node (ref "R12") (pin "2") (pinfunction "2_2") (pintype "passive"))
      (node (ref "R15") (pin "1") (pinfunction "1_1") (pintype "passive"))
    )
    (net (code "247") (name "Net-(Q2-C)") (class "Default")
      (node (ref "Q2") (pin "3") (pinfunction "C_3") (pintype "passive"))
      (node (ref "R11") (pin "2") (pinfunction "2_2") (pintype "passive"))
    )
    (net (code "248") (name "Net-(Q2-E)") (class "Default")
      (node (ref "Q2") (pin "2") (pinfunction "E_2") (pintype "passive"))
      (node (ref "R13") (pin "2") (pinfunction "2_2") (pintype "passive"))
      (node (ref "R16") (pin "1") (pinfunction "1_1") (pintype "passive"))
    )
    (net (code "249") (name "Net-(Q3-C)") (class "Default")
      (node (ref "Q3") (pin "3") (pinfunction "C_3") (pintype "passive"))
      (node (ref "R17") (pin "2") (pinfunction "2_2") (pintype "passive"))
    )
    (net (code "250") (name "Net-(Q3-E)") (class "Default")
      (node (ref "Q3") (pin "2") (pinfunction "E_2") (pintype "passive"))
      (node (ref "R19") (pin "2") (pinfunction "2_2") (pintype "passive"))
      (node (ref "R21") (pin "1") (pinfunction "1_1") (pintype "passive"))
    )
    (net (code "251") (name "Net-(Q4-C)") (class "Default")
      (node (ref "Q4") (pin "3") (pinfunction "C_3") (pintype "passive"))
      (node (ref "R18") (pin "2") (pinfunction "2_2") (pintype "passive"))
    )
    (net (code "252") (name "Net-(Q4-E)") (class "Default")
      (node (ref "Q4") (pin "2") (pinfunction "E_2") (pintype "passive"))
      (node (ref "R20") (pin "2") (pinfunction "2_2") (pintype "passive"))
      (node (ref "R22") (pin "1") (pinfunction "1_1") (pintype "passive"))
    )
    (net (code "253") (name "Net-(S2-COMMON)") (class "Default")
      (node (ref "P8") (pin "2") (pinfunction "2_2") (pintype "passive"))
      (node (ref "S2") (pin "1") (pinfunction "COMMON_1") (pintype "passive"))
    )
    (net (code "254") (name "Net-(U1I-TDI)") (class "Default")
      (node (ref "R33") (pin "2") (pinfunction "2_2") (pintype "passive"))
      (node (ref "U1") (pin "208") (pinfunction "TDI_208") (pintype "input"))
    )
    (net (code "255") (name "Net-(U2-OUT1)") (class "Default")
      (node (ref "P1") (pin "1") (pinfunction "1_1") (pintype "passive"))
      (node (ref "U2") (pin "18") (pinfunction "OUT1_18") (pintype "open_collector"))
    )
    (net (code "256") (name "Net-(U2-OUT2)") (class "Default")
      (node (ref "P1") (pin "2") (pinfunction "2_2") (pintype "passive"))
      (node (ref "U2") (pin "17") (pinfunction "OUT2_17") (pintype "open_collector"))
    )
    (net (code "257") (name "Net-(U2-OUT3)") (class "Default")
      (node (ref "P1") (pin "3") (pinfunction "3_3") (pintype "passive"))
      (node (ref "U2") (pin "16") (pinfunction "OUT3_16") (pintype "open_collector"))
    )
    (net (code "258") (name "Net-(U2-OUT4)") (class "Default")
      (node (ref "P1") (pin "4") (pinfunction "4_4") (pintype "passive"))
      (node (ref "U2") (pin "15") (pinfunction "OUT4_15") (pintype "open_collector"))
    )
    (net (code "259") (name "Net-(U2-OUT7)") (class "Default")
      (node (ref "LS1") (pin "2") (pinfunction "2_2") (pintype "passive"))
      (node (ref "U2") (pin "12") (pinfunction "OUT7_12") (pintype "open_collector"))
    )
    (net (code "260") (name "Net-(U2-OUT8)") (class "Default")
      (node (ref "P6") (pin "2") (pinfunction "2_2") (pintype "passive"))
      (node (ref "U2") (pin "11") (pinfunction "OUT8_11") (pintype "open_collector"))
    )
    (net (code "261") (name "Net-(U10-3V3OUT)") (class "Default")
      (node (ref "C52") (pin "2") (pinfunction "2_2") (pintype "passive"))
      (node (ref "U10") (pin "17") (pinfunction "3V3OUT_17") (pintype "passive"))
    )
    (net (code "262") (name "Net-(U10-USBDM)") (class "Default")
      (node (ref "U10") (pin "16") (pinfunction "USBDM_16") (pintype "passive"))
      (node (ref "USB1") (pin "2") (pinfunction "D-_2") (pintype "passive"))
    )
    (net (code "263") (name "Net-(U10-USBDP)") (class "Default")
      (node (ref "U10") (pin "15") (pinfunction "USBDP_15") (pintype "passive"))
      (node (ref "USB1") (pin "3") (pinfunction "D+_3") (pintype "passive"))
    )
    (net (code "264") (name "Net-(U11-CLK)") (class "Default")
      (node (ref "U1") (pin "104") (pinfunction "CCLK_104") (pintype "bidirectional"))
      (node (ref "U11") (pin "3") (pinfunction "CLK_3") (pintype "input"))
    )
    (net (code "265") (name "Net-(U11-OE{slash}~{RESET})") (class "Default")
      (node (ref "R26") (pin "1") (pinfunction "1_1") (pintype "passive"))
      (node (ref "U11") (pin "8") (pinfunction "OE/~{RESET}_8") (pintype "bidirectional"))
    )
    (net (code "266") (name "Net-(U11-TCK)") (class "Default")
      (node (ref "R34") (pin "1") (pinfunction "1_1") (pintype "passive"))
      (node (ref "U11") (pin "6") (pinfunction "TCK_6") (pintype "input"))
    )
    (net (code "267") (name "Net-(U11-TDO)") (class "Default")
      (node (ref "R33") (pin "1") (pinfunction "1_1") (pintype "passive"))
      (node (ref "U11") (pin "17") (pinfunction "TDO_17") (pintype "output"))
    )
    (net (code "268") (name "Net-(U11-TMS)") (class "Default")
      (node (ref "R35") (pin "1") (pinfunction "1_1") (pintype "passive"))
      (node (ref "U11") (pin "5") (pinfunction "TMS_5") (pintype "input"))
    )
    (net (code "269") (name "Net-(U11-~{CF})") (class "Default")
      (node (ref "R28") (pin "1") (pinfunction "1_1") (pintype "passive"))
      (node (ref "S5") (pin "1") (pinfunction "1_1") (pintype "passive"))
      (node (ref "U1") (pin "207") (pinfunction "PROG_B_207") (pintype "input"))
      (node (ref "U11") (pin "7") (pinfunction "~{CF}_7") (pintype "open_collector"))
    )
    (net (code "270") (name "Net-(U14-DM)") (class "Default")
      (node (ref "R43") (pin "2") (pinfunction "2_2") (pintype "passive"))
      (node (ref "U14") (pin "7") (pinfunction "DM_7") (pintype "input"))
    )
    (net (code "271") (name "Net-(U14-DP)") (class "Default")
      (node (ref "R46") (pin "2") (pinfunction "2_2") (pintype "passive"))
      (node (ref "U14") (pin "8") (pinfunction "DP_8") (pintype "input"))
    )
    (net (code "272") (name "Net-(U14-EECLK)") (class "Default")
      (node (ref "U14") (pin "62") (pinfunction "EECLK_62") (pintype "output"))
      (node (ref "U16") (pin "2") (pinfunction "CLK_2") (pintype "input"))
    )
    (net (code "273") (name "Net-(U14-EECS)") (class "Default")
      (node (ref "U14") (pin "63") (pinfunction "EECS_63") (pintype "bidirectional"))
      (node (ref "U16") (pin "1") (pinfunction "CS_1") (pintype "input"))
    )
    (net (code "274") (name "Net-(U14-EEDATA)") (class "Default")
      (node (ref "R60") (pin "2") (pinfunction "2_2") (pintype "passive"))
      (node (ref "U14") (pin "61") (pinfunction "EEDATA_61") (pintype "bidirectional"))
      (node (ref "U16") (pin "3") (pinfunction "DI_3") (pintype "input"))
    )
    (net (code "275") (name "Net-(U14-OSCI)") (class "Default")
      (node (ref "C75") (pin "2") (pinfunction "2_2") (pintype "passive"))
      (node (ref "U14") (pin "2") (pinfunction "OSCI_2") (pintype "input"))
      (node (ref "Y2") (pin "1") (pinfunction "OSC1_1") (pintype "passive"))
    )
    (net (code "276") (name "Net-(U14-OSCO)") (class "Default")
      (node (ref "C78") (pin "2") (pinfunction "2_2") (pintype "passive"))
      (node (ref "U14") (pin "3") (pinfunction "OSCO_3") (pintype "output"))
      (node (ref "Y2") (pin "2") (pinfunction "OSC2_2") (pintype "passive"))
    )
    (net (code "277") (name "Net-(U14-REF)") (class "Default")
      (node (ref "R51") (pin "2") (pinfunction "2_2") (pintype "passive"))
      (node (ref "U14") (pin "6") (pinfunction "REF_6") (pintype "input"))
    )
    (net (code "278") (name "Net-(U14-RESET#)") (class "Default")
      (node (ref "R48") (pin "2") (pinfunction "2_2") (pintype "passive"))
      (node (ref "U14") (pin "14") (pinfunction "RESET#_14") (pintype "input"))
    )
    (net (code "279") (name "Net-(U14-VPHY)") (class "Default")
      (node (ref "C63") (pin "2") (pinfunction "2_2") (pintype "passive"))
      (node (ref "C65") (pin "2") (pinfunction "2_2") (pintype "passive"))
      (node (ref "L5") (pin "2") (pinfunction "2_2") (pintype "passive"))
      (node (ref "U14") (pin "4") (pinfunction "VPHY_4") (pintype "power_in"))
    )
    (net (code "280") (name "Net-(U14-VPLL)") (class "Default")
      (node (ref "C62") (pin "2") (pinfunction "2_2") (pintype "passive"))
      (node (ref "C64") (pin "2") (pinfunction "2_2") (pintype "passive"))
      (node (ref "L4") (pin "2") (pinfunction "2_2") (pintype "passive"))
      (node (ref "U14") (pin "9") (pinfunction "VPLL_9") (pintype "power_in"))
    )
    (net (code "281") (name "Net-(U16-DO)") (class "Default")
      (node (ref "R59") (pin "2") (pinfunction "2_2") (pintype "passive"))
      (node (ref "R60") (pin "1") (pinfunction "1_1") (pintype "passive"))
      (node (ref "U16") (pin "4") (pinfunction "DO_4") (pintype "tri_state"))
    )
    (net (code "282") (name "Net-(U17-C1+)") (class "Default")
      (node (ref "C71") (pin "1") (pinfunction "1_1") (pintype "passive"))
      (node (ref "U17") (pin "1") (pinfunction "C1+_1") (pintype "passive"))
    )
    (net (code "283") (name "Net-(U17-C1-)") (class "Default")
      (node (ref "C71") (pin "2") (pinfunction "2_2") (pintype "passive"))
      (node (ref "U17") (pin "3") (pinfunction "C1-_3") (pintype "passive"))
    )
    (net (code "284") (name "Net-(U17-C2+)") (class "Default")
      (node (ref "C73") (pin "1") (pinfunction "1_1") (pintype "passive"))
      (node (ref "U17") (pin "4") (pinfunction "C2+_4") (pintype "passive"))
    )
    (net (code "285") (name "Net-(U17-C2-)") (class "Default")
      (node (ref "C73") (pin "2") (pinfunction "2_2") (pintype "passive"))
      (node (ref "U17") (pin "5") (pinfunction "C2-_5") (pintype "passive"))
    )
    (net (code "286") (name "Net-(U17-R1IN)") (class "Default")
      (node (ref "J2") (pin "3") (pinfunction "3_3") (pintype "passive"))
      (node (ref "U17") (pin "13") (pinfunction "R1IN_13") (pintype "input"))
    )
    (net (code "287") (name "Net-(U17-T1OUT)") (class "Default")
      (node (ref "J2") (pin "2") (pinfunction "2_2") (pintype "passive"))
      (node (ref "U17") (pin "14") (pinfunction "T1OUT_14") (pintype "output"))
    )
    (net (code "288") (name "Net-(U17-V+)") (class "Default")
      (node (ref "C72") (pin "2") (pinfunction "2_2") (pintype "passive"))
      (node (ref "U17") (pin "2") (pinfunction "V+_2") (pintype "power_in"))
    )
    (net (code "289") (name "Net-(U17-V-)") (class "Default")
      (node (ref "C77") (pin "2") (pinfunction "2_2") (pintype "passive"))
      (node (ref "U17") (pin "6") (pinfunction "V-_6") (pintype "power_in"))
    )
    (net (code "290") (name "Net-(USB2-D+)") (class "Default")
      (node (ref "R46") (pin "1") (pinfunction "1_1") (pintype "passive"))
      (node (ref "USB2") (pin "3") (pinfunction "D+_3") (pintype "passive"))
    )
    (net (code "291") (name "Net-(USB2-D-)") (class "Default")
      (node (ref "R43") (pin "1") (pinfunction "1_1") (pintype "passive"))
      (node (ref "USB2") (pin "2") (pinfunction "D-_2") (pintype "passive"))
    )
    (net (code "292") (name "Net-(USB2-VCC)") (class "Default")
      (node (ref "L6") (pin "1") (pinfunction "1_1") (pintype "passive"))
      (node (ref "USB2") (pin "1") (pinfunction "VCC_1") (pintype "passive"))
    )
    (net (code "293") (name "unconnected-(J1-MH1-Pad16)") (class "Default")
      (node (ref "J1") (pin "16") (pinfunction "MH1_16") (pintype "passive+no_connect"))
    )
    (net (code "294") (name "unconnected-(J1-MH2-Pad17)") (class "Default")
      (node (ref "J1") (pin "17") (pinfunction "MH2_17") (pintype "passive+no_connect"))
    )
    (net (code "295") (name "unconnected-(J1-Pad4)") (class "Default")
      (node (ref "J1") (pin "4") (pinfunction "4_4") (pintype "passive+no_connect"))
    )
    (net (code "296") (name "unconnected-(J1-Pad9)") (class "Default")
      (node (ref "J1") (pin "9") (pinfunction "9_9") (pintype "passive+no_connect"))
    )
    (net (code "297") (name "unconnected-(J1-Pad12)") (class "Default")
      (node (ref "J1") (pin "12") (pinfunction "12_12") (pintype "passive+no_connect"))
    )
    (net (code "298") (name "unconnected-(J1-Pad14)") (class "Default")
      (node (ref "J1") (pin "14") (pinfunction "14_14") (pintype "passive+no_connect"))
    )
    (net (code "299") (name "unconnected-(J2-MH1-Pad10)") (class "Default")
      (node (ref "J2") (pin "10") (pinfunction "MH1_10") (pintype "passive+no_connect"))
    )
    (net (code "300") (name "unconnected-(J2-MH2-Pad11)") (class "Default")
      (node (ref "J2") (pin "11") (pinfunction "MH2_11") (pintype "passive+no_connect"))
    )
    (net (code "301") (name "unconnected-(J2-Pad1)") (class "Default")
      (node (ref "J2") (pin "1") (pinfunction "1_1") (pintype "passive+no_connect"))
    )
    (net (code "302") (name "unconnected-(J2-Pad4)") (class "Default")
      (node (ref "J2") (pin "4") (pinfunction "4_4") (pintype "passive+no_connect"))
    )
    (net (code "303") (name "unconnected-(J2-Pad5)") (class "Default")
      (node (ref "J2") (pin "5") (pinfunction "5_5") (pintype "passive+no_connect"))
    )
    (net (code "304") (name "unconnected-(J2-Pad6)") (class "Default")
      (node (ref "J2") (pin "6") (pinfunction "6_6") (pintype "passive+no_connect"))
    )
    (net (code "305") (name "unconnected-(J2-Pad7)") (class "Default")
      (node (ref "J2") (pin "7") (pinfunction "7_7") (pintype "passive+no_connect"))
    )
    (net (code "306") (name "unconnected-(J2-Pad8)") (class "Default")
      (node (ref "J2") (pin "8") (pinfunction "8_8") (pintype "passive+no_connect"))
    )
    (net (code "307") (name "unconnected-(J2-Pad9)") (class "Default")
      (node (ref "J2") (pin "9") (pinfunction "9_9") (pintype "passive+no_connect"))
    )
    (net (code "308") (name "unconnected-(LCD1-D0-Pad7)") (class "Default")
      (node (ref "LCD1") (pin "7") (pinfunction "D0_7") (pintype "passive+no_connect"))
    )
    (net (code "309") (name "unconnected-(LCD1-D1-Pad8)") (class "Default")
      (node (ref "LCD1") (pin "8") (pinfunction "D1_8") (pintype "passive+no_connect"))
    )
    (net (code "310") (name "unconnected-(LCD1-D2-Pad9)") (class "Default")
      (node (ref "LCD1") (pin "9") (pinfunction "D2_9") (pintype "passive+no_connect"))
    )
    (net (code "311") (name "unconnected-(LCD1-D3-Pad10)") (class "Default")
      (node (ref "LCD1") (pin "10") (pinfunction "D3_10") (pintype "passive+no_connect"))
    )
    (net (code "312") (name "unconnected-(P12-Pad6)") (class "Default")
      (node (ref "P12") (pin "6") (pinfunction "6_6") (pintype "passive+no_connect"))
    )
    (net (code "313") (name "unconnected-(P12-Pad7)") (class "Default")
      (node (ref "P12") (pin "7") (pinfunction "7_7") (pintype "passive+no_connect"))
    )
    (net (code "314") (name "unconnected-(P12-Pad8)") (class "Default")
      (node (ref "P12") (pin "8") (pinfunction "8_8") (pintype "passive+no_connect"))
    )
    (net (code "315") (name "unconnected-(U1B-IO_L01P_1{slash}VRN_1-Pad161)") (class "Default")
      (node (ref "U1") (pin "161") (pinfunction "IO_L01P_1/VRN_1_161") (pintype "bidirectional+no_connect"))
    )
    (net (code "316") (name "unconnected-(U10-CBUS2-Pad13)") (class "Default")
      (node (ref "U10") (pin "13") (pinfunction "CBUS2_13") (pintype "passive+no_connect"))
    )
    (net (code "317") (name "unconnected-(U10-CBUS3-Pad14)") (class "Default")
      (node (ref "U10") (pin "14") (pinfunction "CBUS3_14") (pintype "passive+no_connect"))
    )
    (net (code "318") (name "unconnected-(U10-CBUS4-Pad12)") (class "Default")
      (node (ref "U10") (pin "12") (pinfunction "CBUS4_12") (pintype "passive+no_connect"))
    )
    (net (code "319") (name "unconnected-(U10-CTS#-Pad11)") (class "Default")
      (node (ref "U10") (pin "11") (pinfunction "CTS#_11") (pintype "passive+no_connect"))
    )
    (net (code "320") (name "unconnected-(U10-DCD#-Pad10)") (class "Default")
      (node (ref "U10") (pin "10") (pinfunction "DCD#_10") (pintype "passive+no_connect"))
    )
    (net (code "321") (name "unconnected-(U10-DSR#-Pad9)") (class "Default")
      (node (ref "U10") (pin "9") (pinfunction "DSR#_9") (pintype "passive+no_connect"))
    )
    (net (code "322") (name "unconnected-(U10-DTR#-Pad2)") (class "Default")
      (node (ref "U10") (pin "2") (pinfunction "DTR#_2") (pintype "passive+no_connect"))
    )
    (net (code "323") (name "unconnected-(U10-NC-Pad8)") (class "Default")
      (node (ref "U10") (pin "8") (pinfunction "NC_8") (pintype "passive+no_connect"))
    )
    (net (code "324") (name "unconnected-(U10-NC-Pad24)") (class "Default")
      (node (ref "U10") (pin "24") (pinfunction "NC_24") (pintype "passive+no_connect"))
    )
    (net (code "325") (name "unconnected-(U10-OCSI-Pad27)") (class "Default")
      (node (ref "U10") (pin "27") (pinfunction "OCSI_27") (pintype "passive+no_connect"))
    )
    (net (code "326") (name "unconnected-(U10-OCSO-Pad28)") (class "Default")
      (node (ref "U10") (pin "28") (pinfunction "OCSO_28") (pintype "passive+no_connect"))
    )
    (net (code "327") (name "unconnected-(U10-RESET#-Pad19)") (class "Default")
      (node (ref "U10") (pin "19") (pinfunction "RESET#_19") (pintype "passive+no_connect"))
    )
    (net (code "328") (name "unconnected-(U10-RI#-Pad6)") (class "Default")
      (node (ref "U10") (pin "6") (pinfunction "RI#_6") (pintype "passive+no_connect"))
    )
    (net (code "329") (name "unconnected-(U10-RTS#-Pad3)") (class "Default")
      (node (ref "U10") (pin "3") (pinfunction "RTS#_3") (pintype "passive+no_connect"))
    )
    (net (code "330") (name "unconnected-(U11-DNC-Pad2)") (class "Default")
      (node (ref "U11") (pin "2") (pinfunction "DNC_2") (pintype "passive+no_connect"))
    )
    (net (code "331") (name "unconnected-(U11-DNC-Pad9)") (class "Default")
      (node (ref "U11") (pin "9") (pinfunction "DNC_9") (pintype "passive+no_connect"))
    )
    (net (code "332") (name "unconnected-(U11-DNC-Pad12)") (class "Default")
      (node (ref "U11") (pin "12") (pinfunction "DNC_12") (pintype "passive+no_connect"))
    )
    (net (code "333") (name "unconnected-(U11-DNC-Pad14)") (class "Default")
      (node (ref "U11") (pin "14") (pinfunction "DNC_14") (pintype "passive+no_connect"))
    )
    (net (code "334") (name "unconnected-(U11-DNC-Pad15)") (class "Default")
      (node (ref "U11") (pin "15") (pinfunction "DNC_15") (pintype "passive+no_connect"))
    )
    (net (code "335") (name "unconnected-(U11-DNC-Pad16)") (class "Default")
      (node (ref "U11") (pin "16") (pinfunction "DNC_16") (pintype "passive+no_connect"))
    )
    (net (code "336") (name "unconnected-(U11-~{CEO}-Pad13)") (class "Default")
      (node (ref "U11") (pin "13") (pinfunction "~{CEO}_13") (pintype "output+no_connect"))
    )
    (net (code "337") (name "unconnected-(U13-NC-Pad28)") (class "Default")
      (node (ref "U13") (pin "28") (pinfunction "NC_28") (pintype "passive+no_connect"))
    )
    (net (code "338") (name "unconnected-(U14-ACBUS0-Pad26)") (class "Default")
      (node (ref "U14") (pin "26") (pinfunction "ACBUS0_26") (pintype "bidirectional+no_connect"))
    )
    (net (code "339") (name "unconnected-(U14-ACBUS1-Pad27)") (class "Default")
      (node (ref "U14") (pin "27") (pinfunction "ACBUS1_27") (pintype "bidirectional+no_connect"))
    )
    (net (code "340") (name "unconnected-(U14-ACBUS2-Pad28)") (class "Default")
      (node (ref "U14") (pin "28") (pinfunction "ACBUS2_28") (pintype "bidirectional+no_connect"))
    )
    (net (code "341") (name "unconnected-(U14-ACBUS3-Pad29)") (class "Default")
      (node (ref "U14") (pin "29") (pinfunction "ACBUS3_29") (pintype "bidirectional+no_connect"))
    )
    (net (code "342") (name "unconnected-(U14-ACBUS4-Pad30)") (class "Default")
      (node (ref "U14") (pin "30") (pinfunction "ACBUS4_30") (pintype "bidirectional+no_connect"))
    )
    (net (code "343") (name "unconnected-(U14-ACBUS5-Pad32)") (class "Default")
      (node (ref "U14") (pin "32") (pinfunction "ACBUS5_32") (pintype "bidirectional+no_connect"))
    )
    (net (code "344") (name "unconnected-(U14-ACBUS6-Pad33)") (class "Default")
      (node (ref "U14") (pin "33") (pinfunction "ACBUS6_33") (pintype "bidirectional+no_connect"))
    )
    (net (code "345") (name "unconnected-(U14-ACBUS7-Pad34)") (class "Default")
      (node (ref "U14") (pin "34") (pinfunction "ACBUS7_34") (pintype "bidirectional+no_connect"))
    )
    (net (code "346") (name "unconnected-(U14-ADBUS4-Pad21)") (class "Default")
      (node (ref "U14") (pin "21") (pinfunction "ADBUS4_21") (pintype "bidirectional+no_connect"))
    )
    (net (code "347") (name "unconnected-(U14-ADBUS5-Pad22)") (class "Default")
      (node (ref "U14") (pin "22") (pinfunction "ADBUS5_22") (pintype "bidirectional+no_connect"))
    )
    (net (code "348") (name "unconnected-(U14-ADBUS6-Pad23)") (class "Default")
      (node (ref "U14") (pin "23") (pinfunction "ADBUS6_23") (pintype "bidirectional+no_connect"))
    )
    (net (code "349") (name "unconnected-(U14-ADBUS7-Pad24)") (class "Default")
      (node (ref "U14") (pin "24") (pinfunction "ADBUS7_24") (pintype "bidirectional+no_connect"))
    )
    (net (code "350") (name "unconnected-(U14-BCBUS0-Pad48)") (class "Default")
      (node (ref "U14") (pin "48") (pinfunction "BCBUS0_48") (pintype "bidirectional+no_connect"))
    )
    (net (code "351") (name "unconnected-(U14-BCBUS1-Pad52)") (class "Default")
      (node (ref "U14") (pin "52") (pinfunction "BCBUS1_52") (pintype "bidirectional+no_connect"))
    )
    (net (code "352") (name "unconnected-(U14-BCBUS2-Pad53)") (class "Default")
      (node (ref "U14") (pin "53") (pinfunction "BCBUS2_53") (pintype "bidirectional+no_connect"))
    )
    (net (code "353") (name "unconnected-(U14-BCBUS3-Pad54)") (class "Default")
      (node (ref "U14") (pin "54") (pinfunction "BCBUS3_54") (pintype "bidirectional+no_connect"))
    )
    (net (code "354") (name "unconnected-(U14-BCBUS4-Pad55)") (class "Default")
      (node (ref "U14") (pin "55") (pinfunction "BCBUS4_55") (pintype "bidirectional+no_connect"))
    )
    (net (code "355") (name "unconnected-(U14-BCBUS5-Pad57)") (class "Default")
      (node (ref "U14") (pin "57") (pinfunction "BCBUS5_57") (pintype "bidirectional+no_connect"))
    )
    (net (code "356") (name "unconnected-(U14-BCBUS6-Pad58)") (class "Default")
      (node (ref "U14") (pin "58") (pinfunction "BCBUS6_58") (pintype "bidirectional+no_connect"))
    )
    (net (code "357") (name "unconnected-(U14-BCBUS7-Pad59)") (class "Default")
      (node (ref "U14") (pin "59") (pinfunction "BCBUS7_59") (pintype "bidirectional+no_connect"))
    )
    (net (code "358") (name "unconnected-(U14-BDBUS2-Pad40)") (class "Default")
      (node (ref "U14") (pin "40") (pinfunction "BDBUS2_40") (pintype "bidirectional+no_connect"))
    )
    (net (code "359") (name "unconnected-(U14-BDBUS3-Pad41)") (class "Default")
      (node (ref "U14") (pin "41") (pinfunction "BDBUS3_41") (pintype "bidirectional+no_connect"))
    )
    (net (code "360") (name "unconnected-(U14-BDBUS4-Pad43)") (class "Default")
      (node (ref "U14") (pin "43") (pinfunction "BDBUS4_43") (pintype "bidirectional+no_connect"))
    )
    (net (code "361") (name "unconnected-(U14-BDBUS5-Pad44)") (class "Default")
      (node (ref "U14") (pin "44") (pinfunction "BDBUS5_44") (pintype "bidirectional+no_connect"))
    )
    (net (code "362") (name "unconnected-(U14-BDBUS6-Pad45)") (class "Default")
      (node (ref "U14") (pin "45") (pinfunction "BDBUS6_45") (pintype "bidirectional+no_connect"))
    )
    (net (code "363") (name "unconnected-(U14-BDBUS7-Pad46)") (class "Default")
      (node (ref "U14") (pin "46") (pinfunction "BDBUS7_46") (pintype "bidirectional+no_connect"))
    )
    (net (code "364") (name "unconnected-(U14-PWREN#-Pad60)") (class "Default")
      (node (ref "U14") (pin "60") (pinfunction "PWREN#_60") (pintype "output+no_connect"))
    )
    (net (code "365") (name "unconnected-(U14-SUSPEND#-Pad36)") (class "Default")
      (node (ref "U14") (pin "36") (pinfunction "SUSPEND#_36") (pintype "output+no_connect"))
    )
    (net (code "366") (name "unconnected-(U16-NC-Pad6)") (class "Default")
      (node (ref "U16") (pin "6") (pinfunction "NC_6") (pintype "passive+no_connect"))
    )
    (net (code "367") (name "unconnected-(U16-NC-Pad7)") (class "Default")
      (node (ref "U16") (pin "7") (pinfunction "NC_7") (pintype "passive+no_connect"))
    )
    (net (code "368") (name "unconnected-(U17-R2IN-Pad8)") (class "Default")
      (node (ref "U17") (pin "8") (pinfunction "R2IN_8") (pintype "input+no_connect"))
    )
    (net (code "369") (name "unconnected-(U17-R2OUT-Pad9)") (class "Default")
      (node (ref "U17") (pin "9") (pinfunction "R2OUT_9") (pintype "output+no_connect"))
    )
    (net (code "370") (name "unconnected-(U17-T2IN-Pad10)") (class "Default")
      (node (ref "U17") (pin "10") (pinfunction "T2IN_10") (pintype "input+no_connect"))
    )
    (net (code "371") (name "unconnected-(U17-T2OUT-Pad7)") (class "Default")
      (node (ref "U17") (pin "7") (pinfunction "T2OUT_7") (pintype "output+no_connect"))
    )
    (net (code "372") (name "unconnected-(USB1-NC-Pad4)") (class "Default")
      (node (ref "USB1") (pin "4") (pinfunction "NC_4") (pintype "passive+no_connect"))
    )
    (net (code "373") (name "unconnected-(USB2-NC-Pad4)") (class "Default")
      (node (ref "USB2") (pin "4") (pinfunction "NC_4") (pintype "passive+no_connect"))
    )
  )
)
